# Module_BaseBoard__2_0.net
KiCad netlist of a schematic drawn in EAGLE
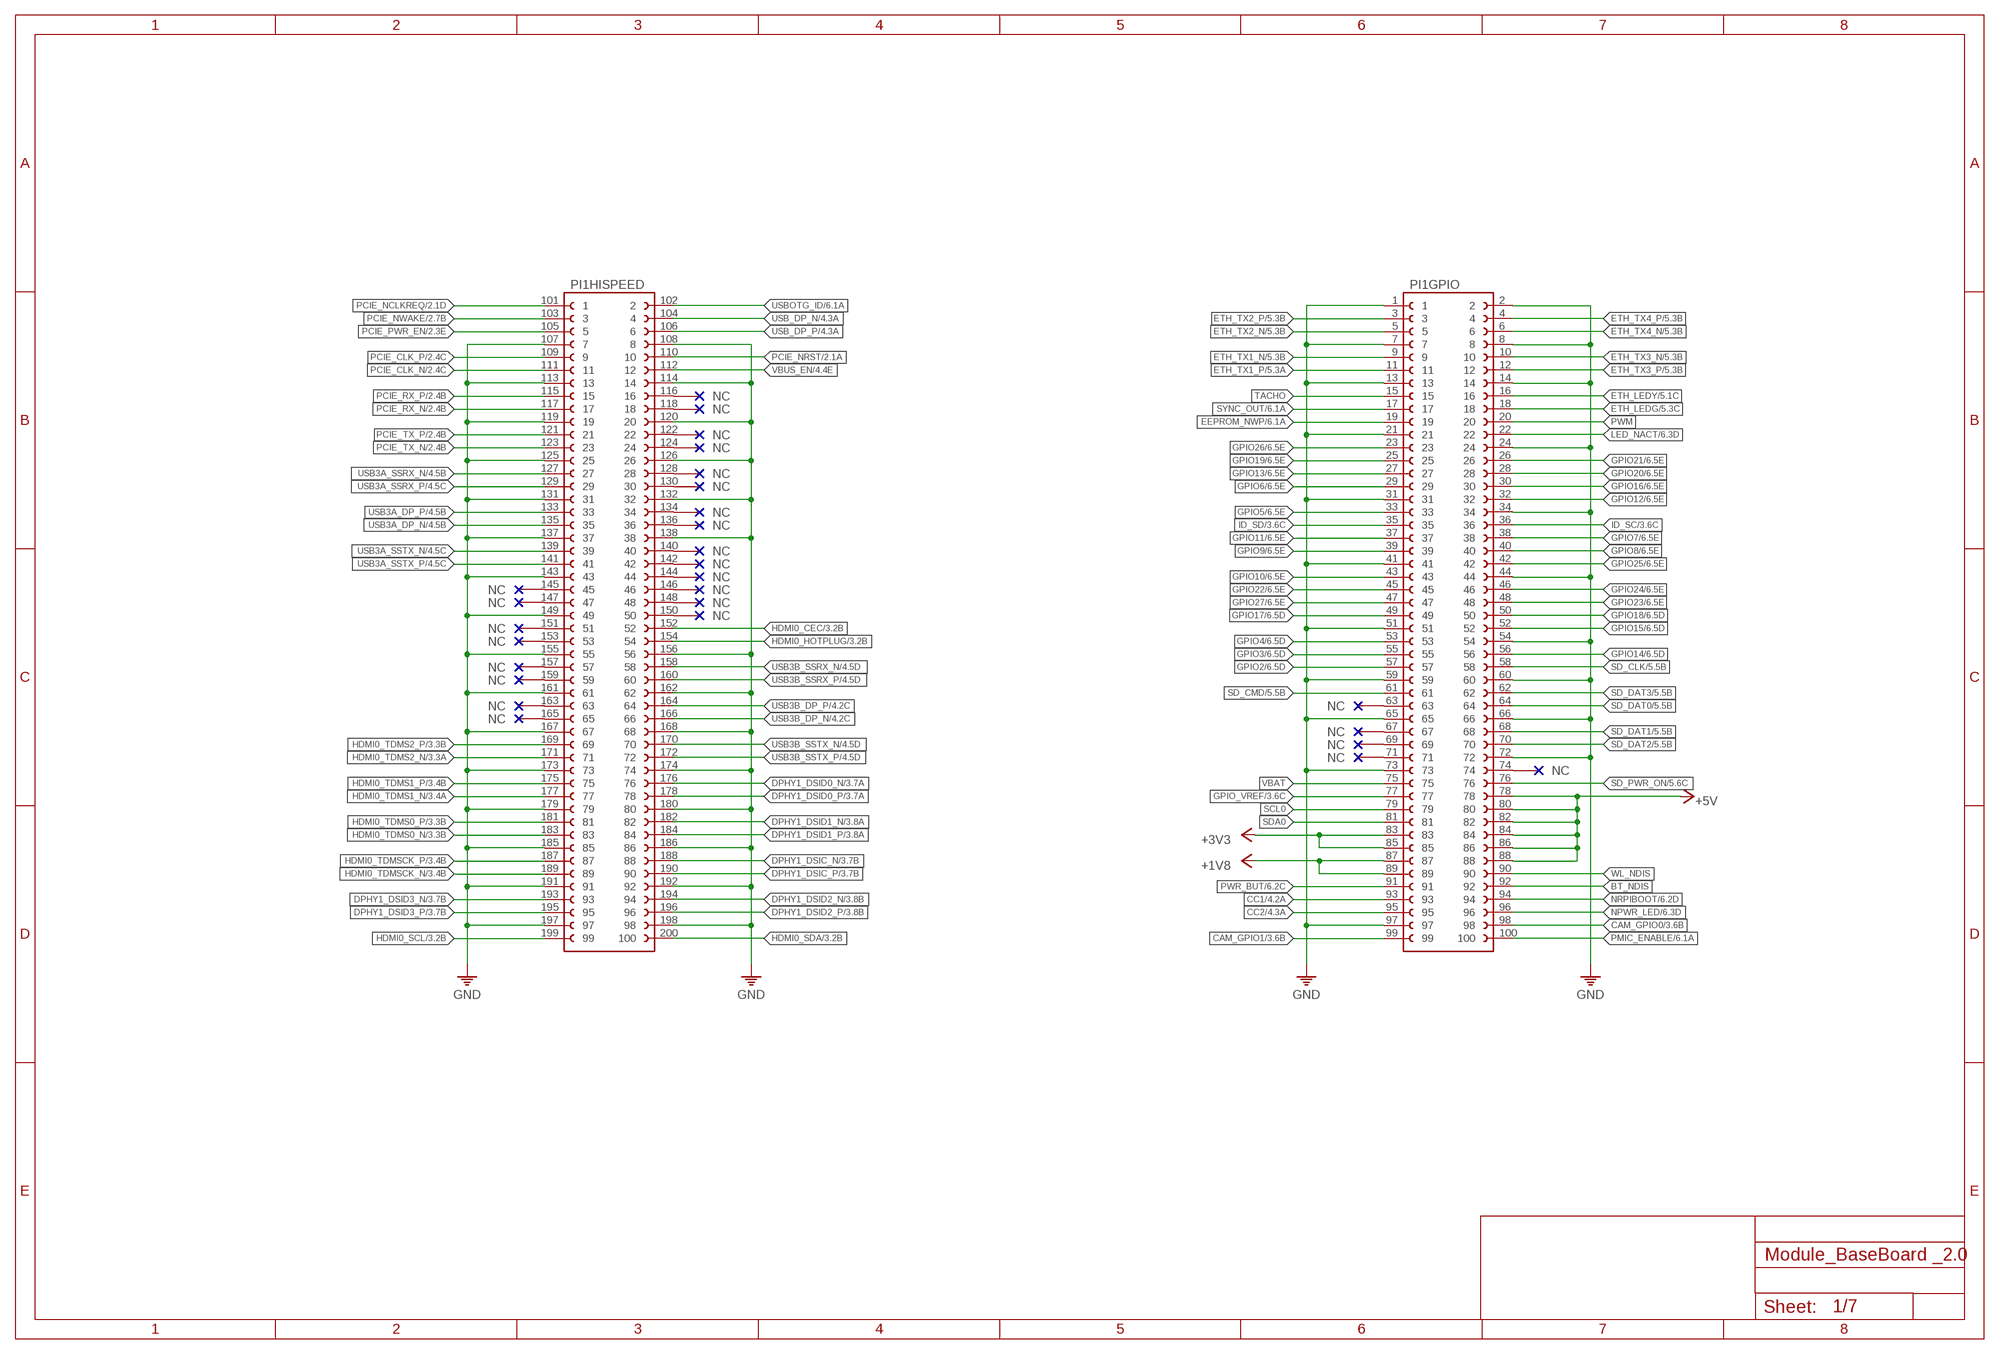
[diagram p0: schematic, sheet 1]
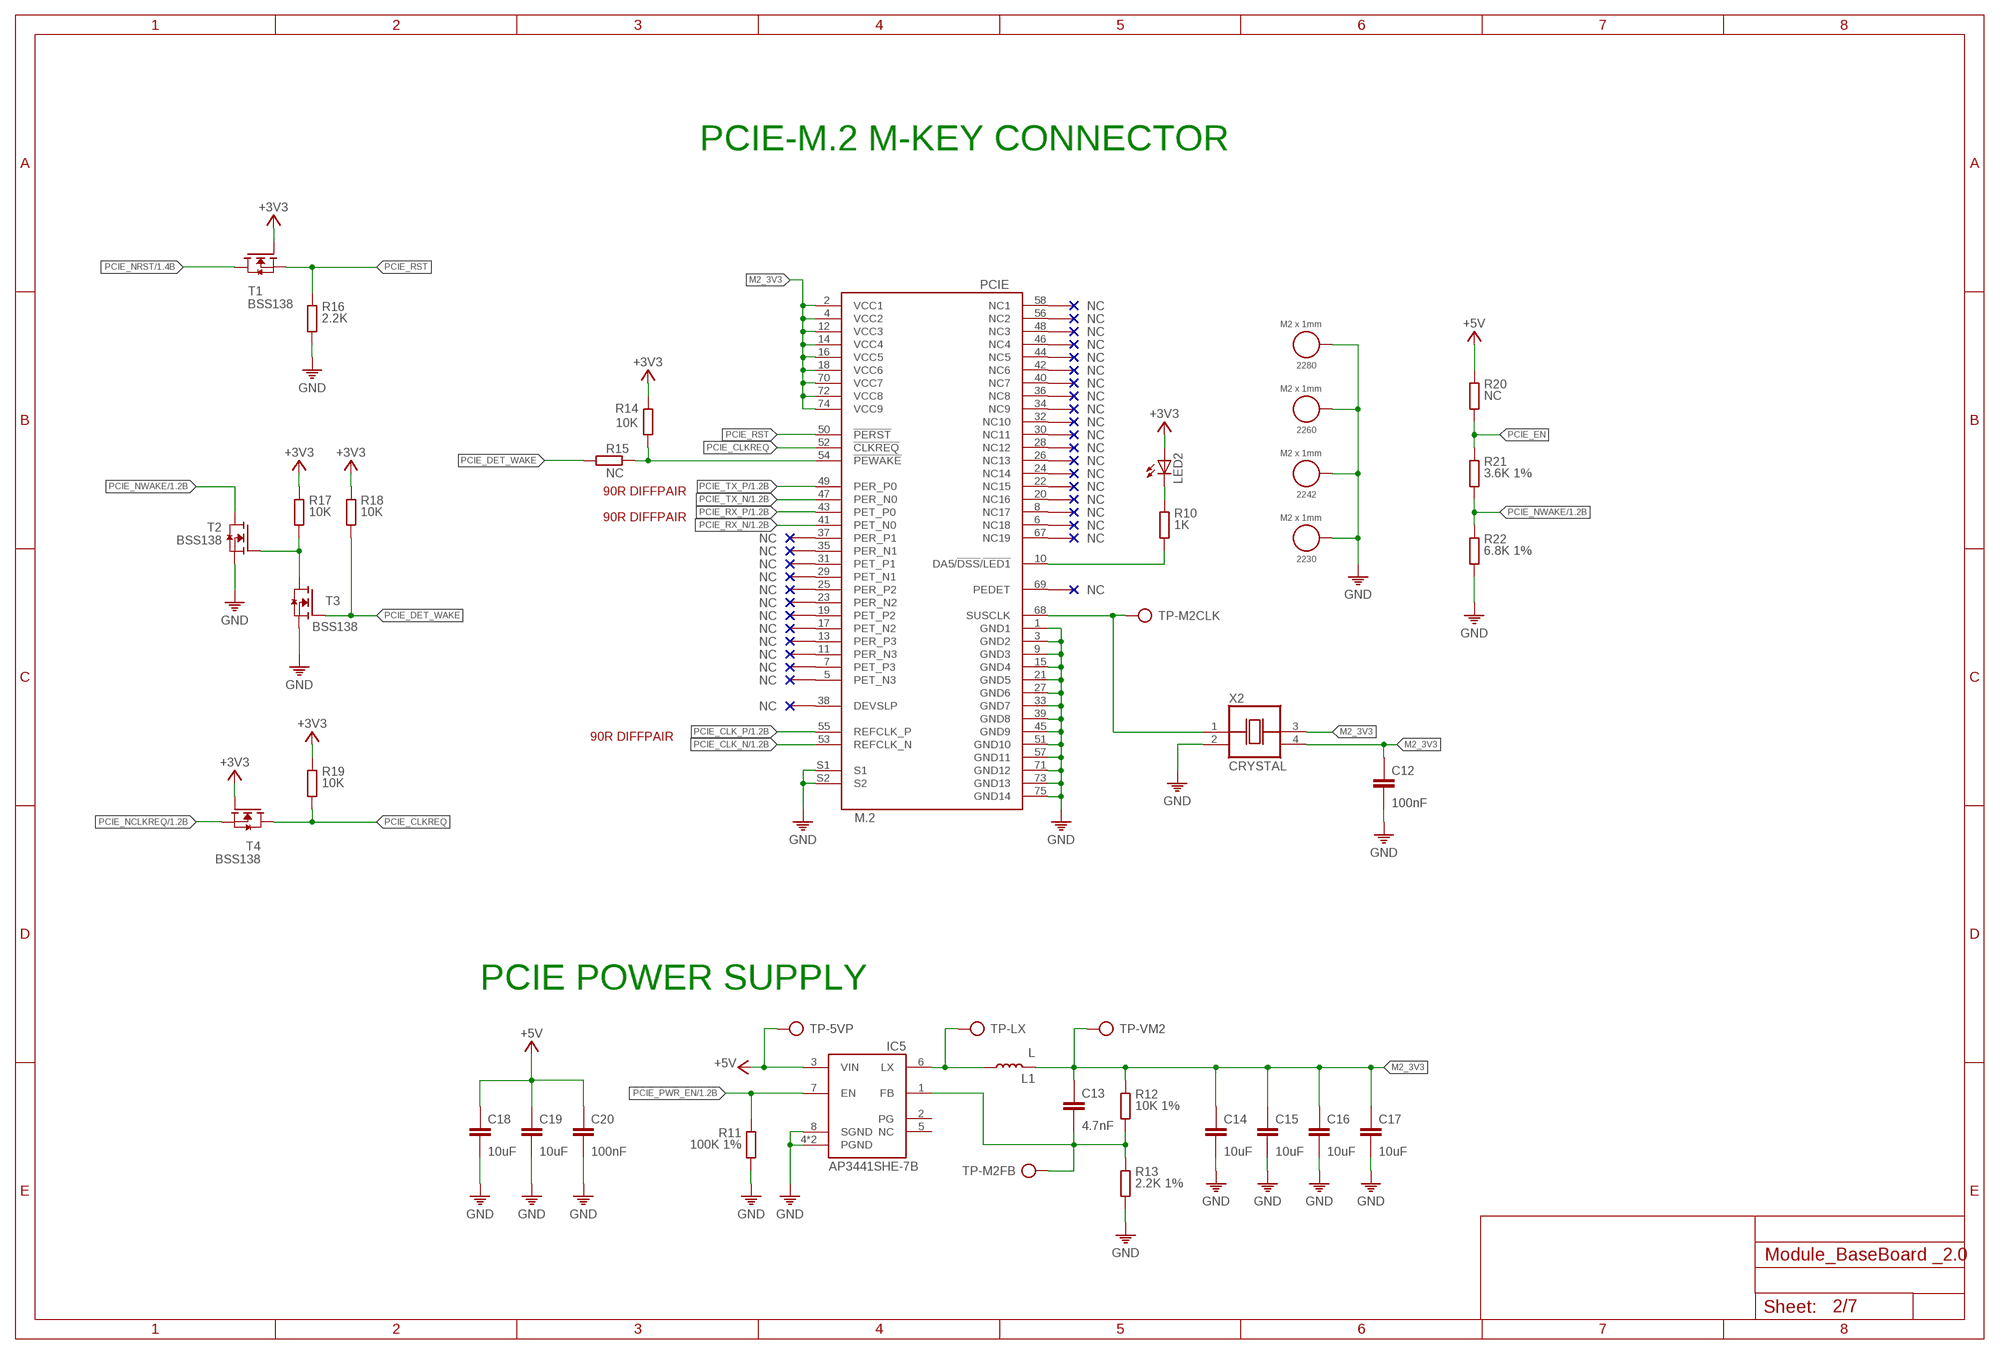
[diagram p1: schematic, sheet 2]
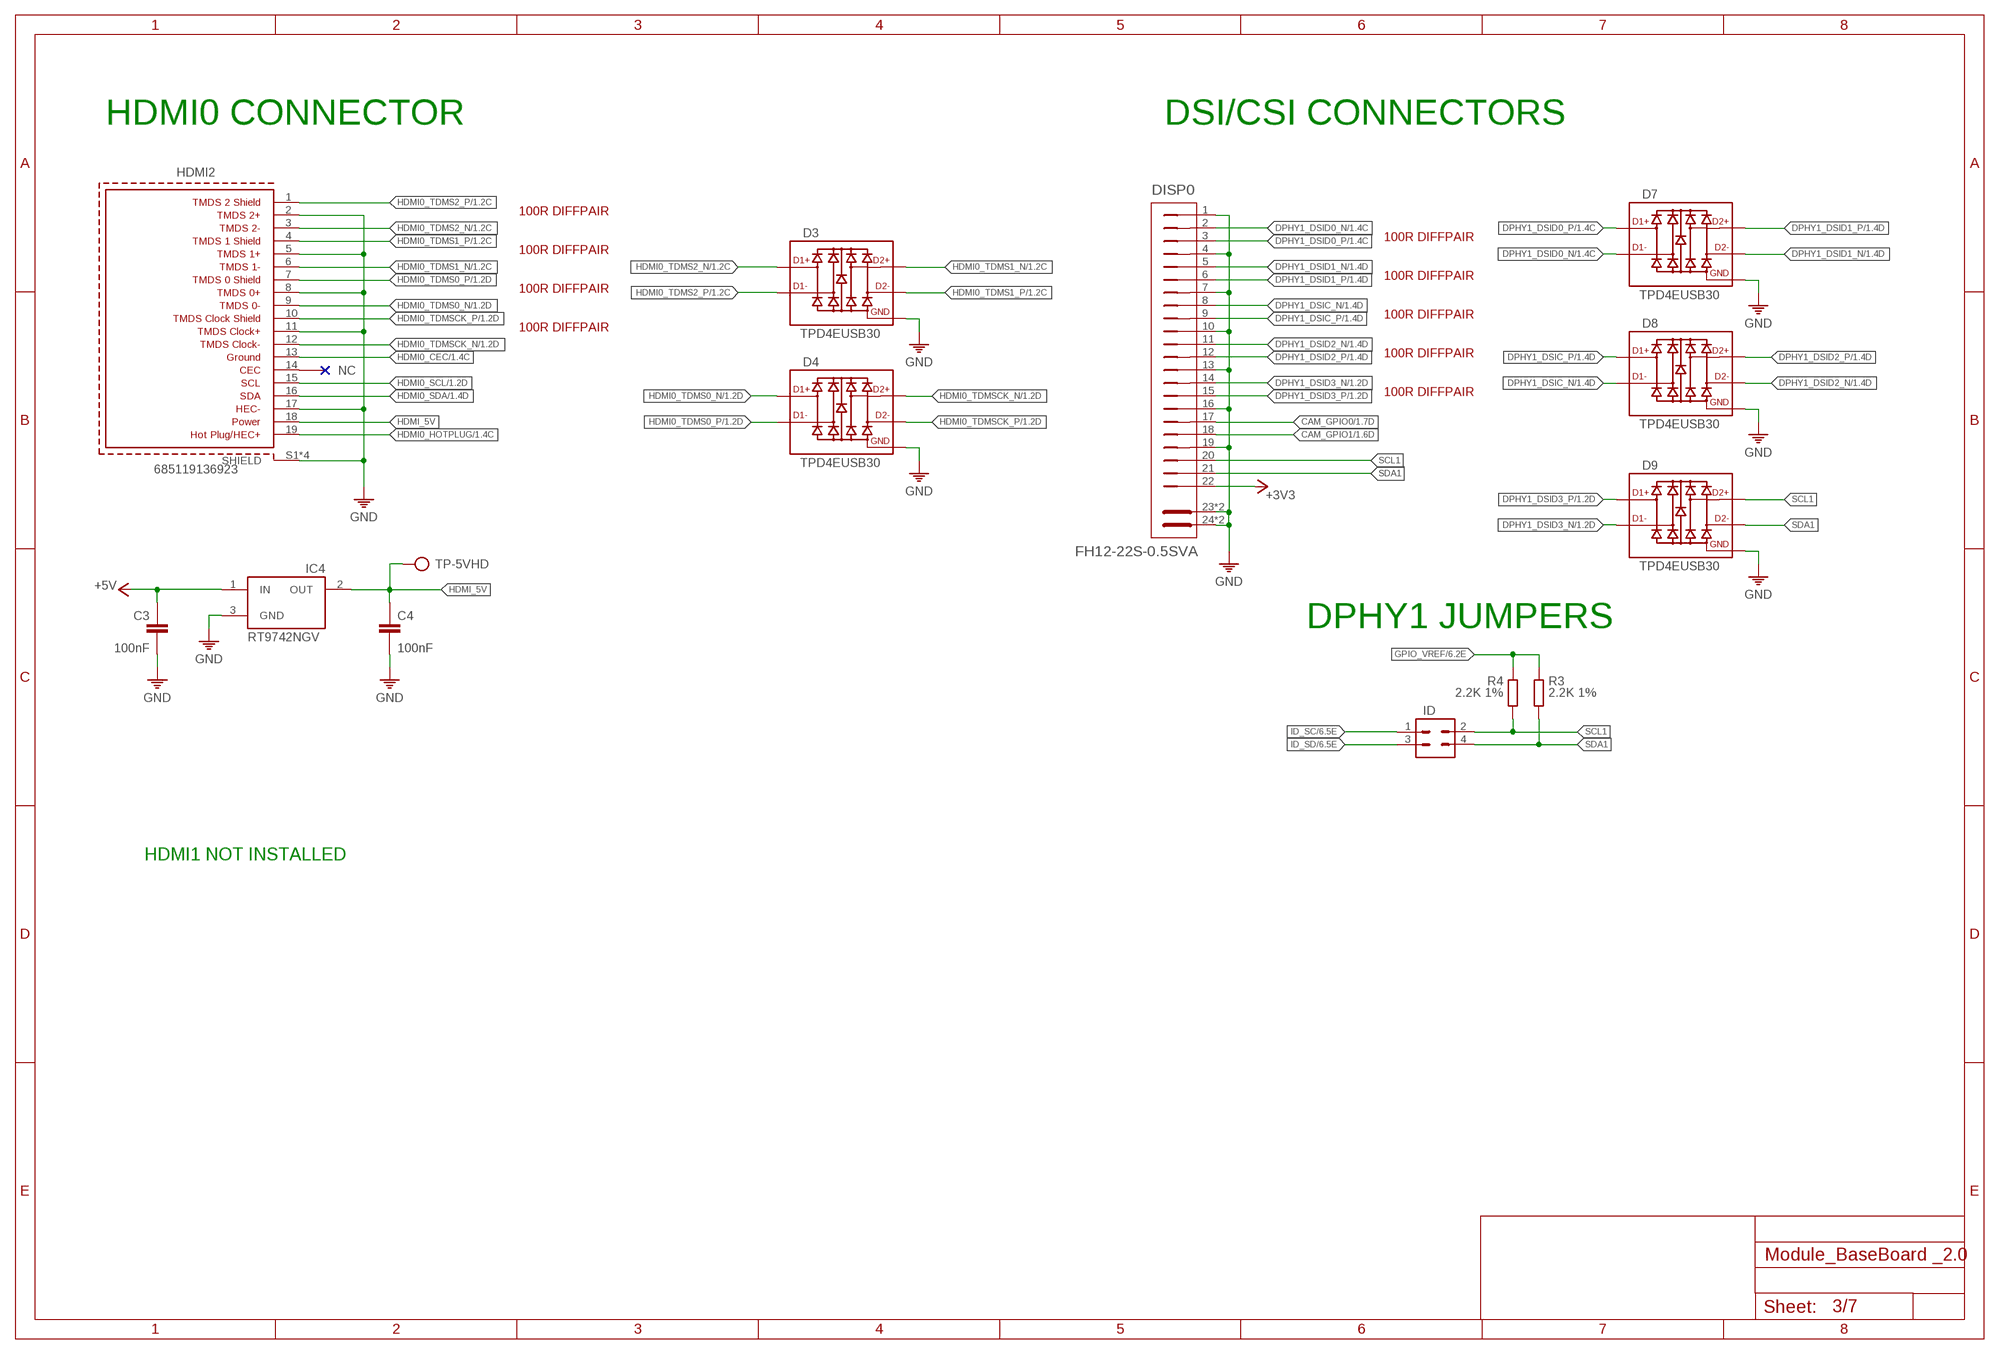
[diagram p2: schematic, sheet 3]
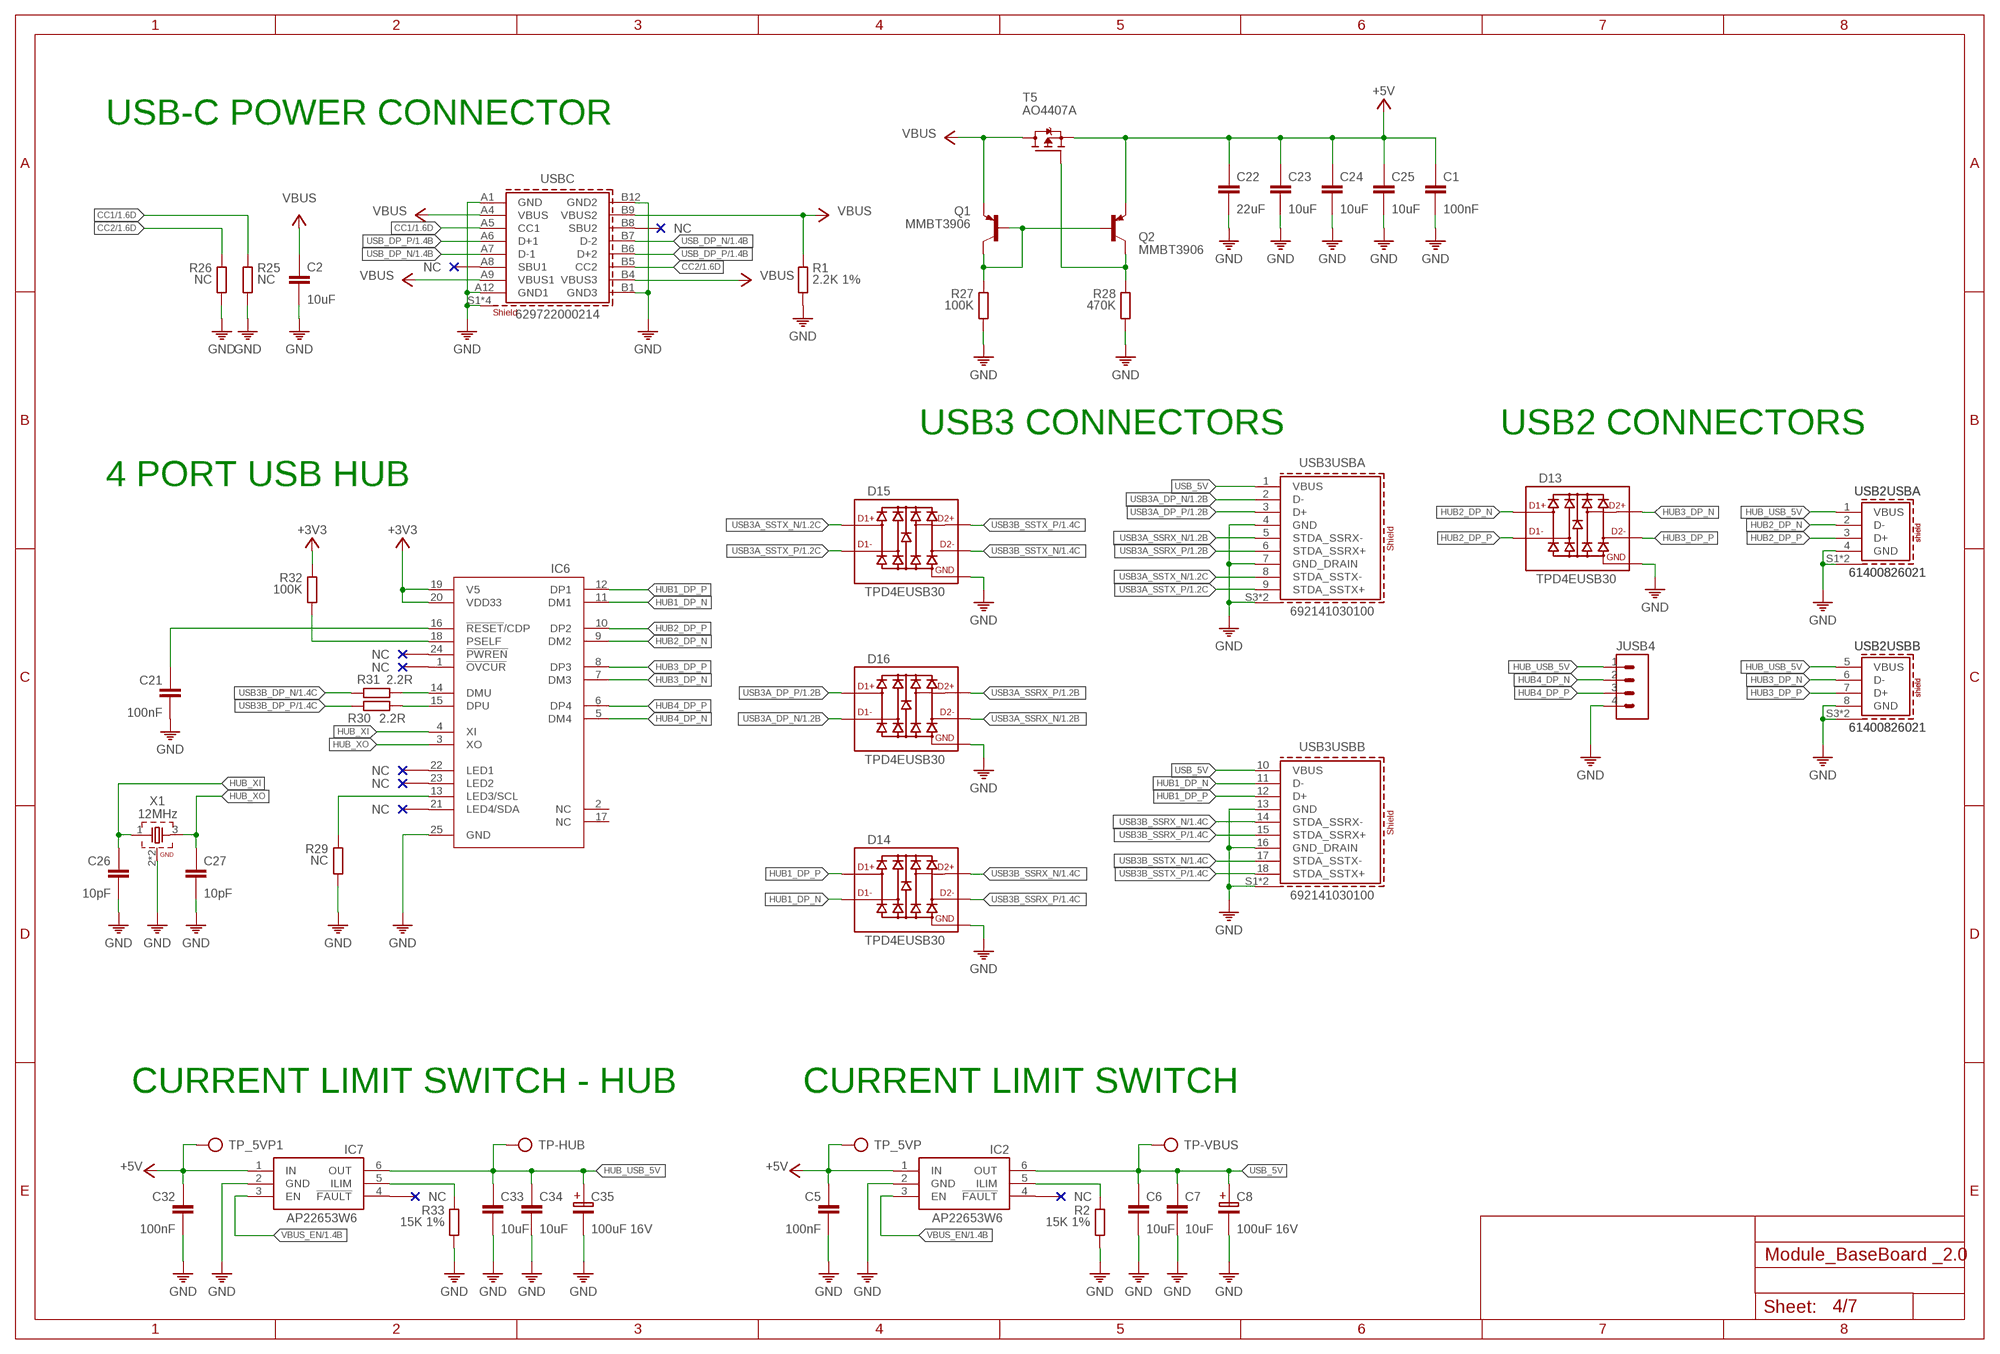
[diagram p3: schematic, sheet 4]
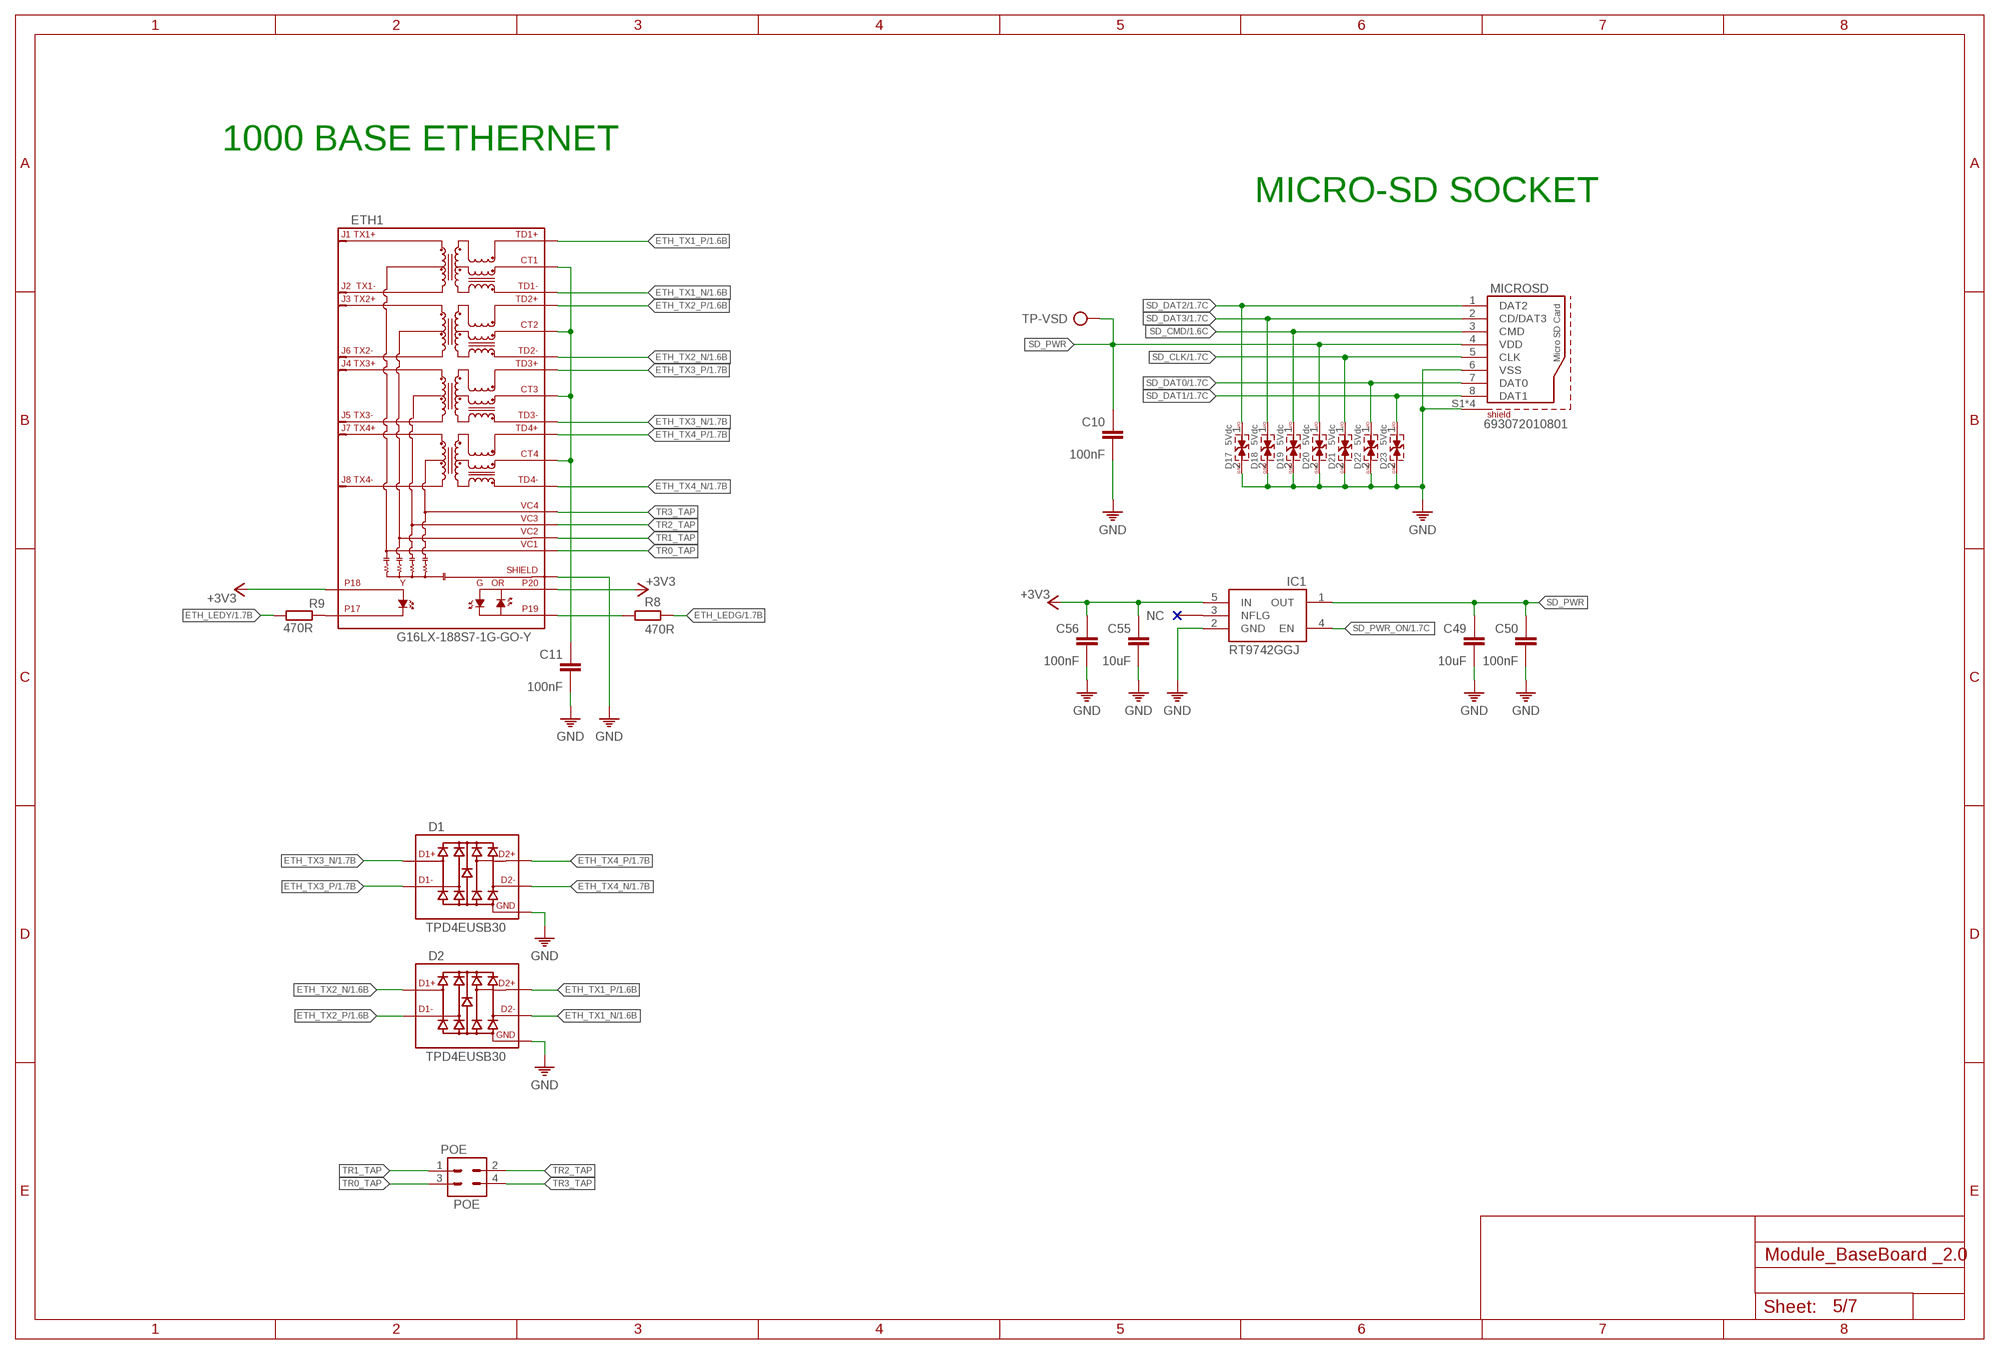
[diagram p4: schematic, sheet 5]
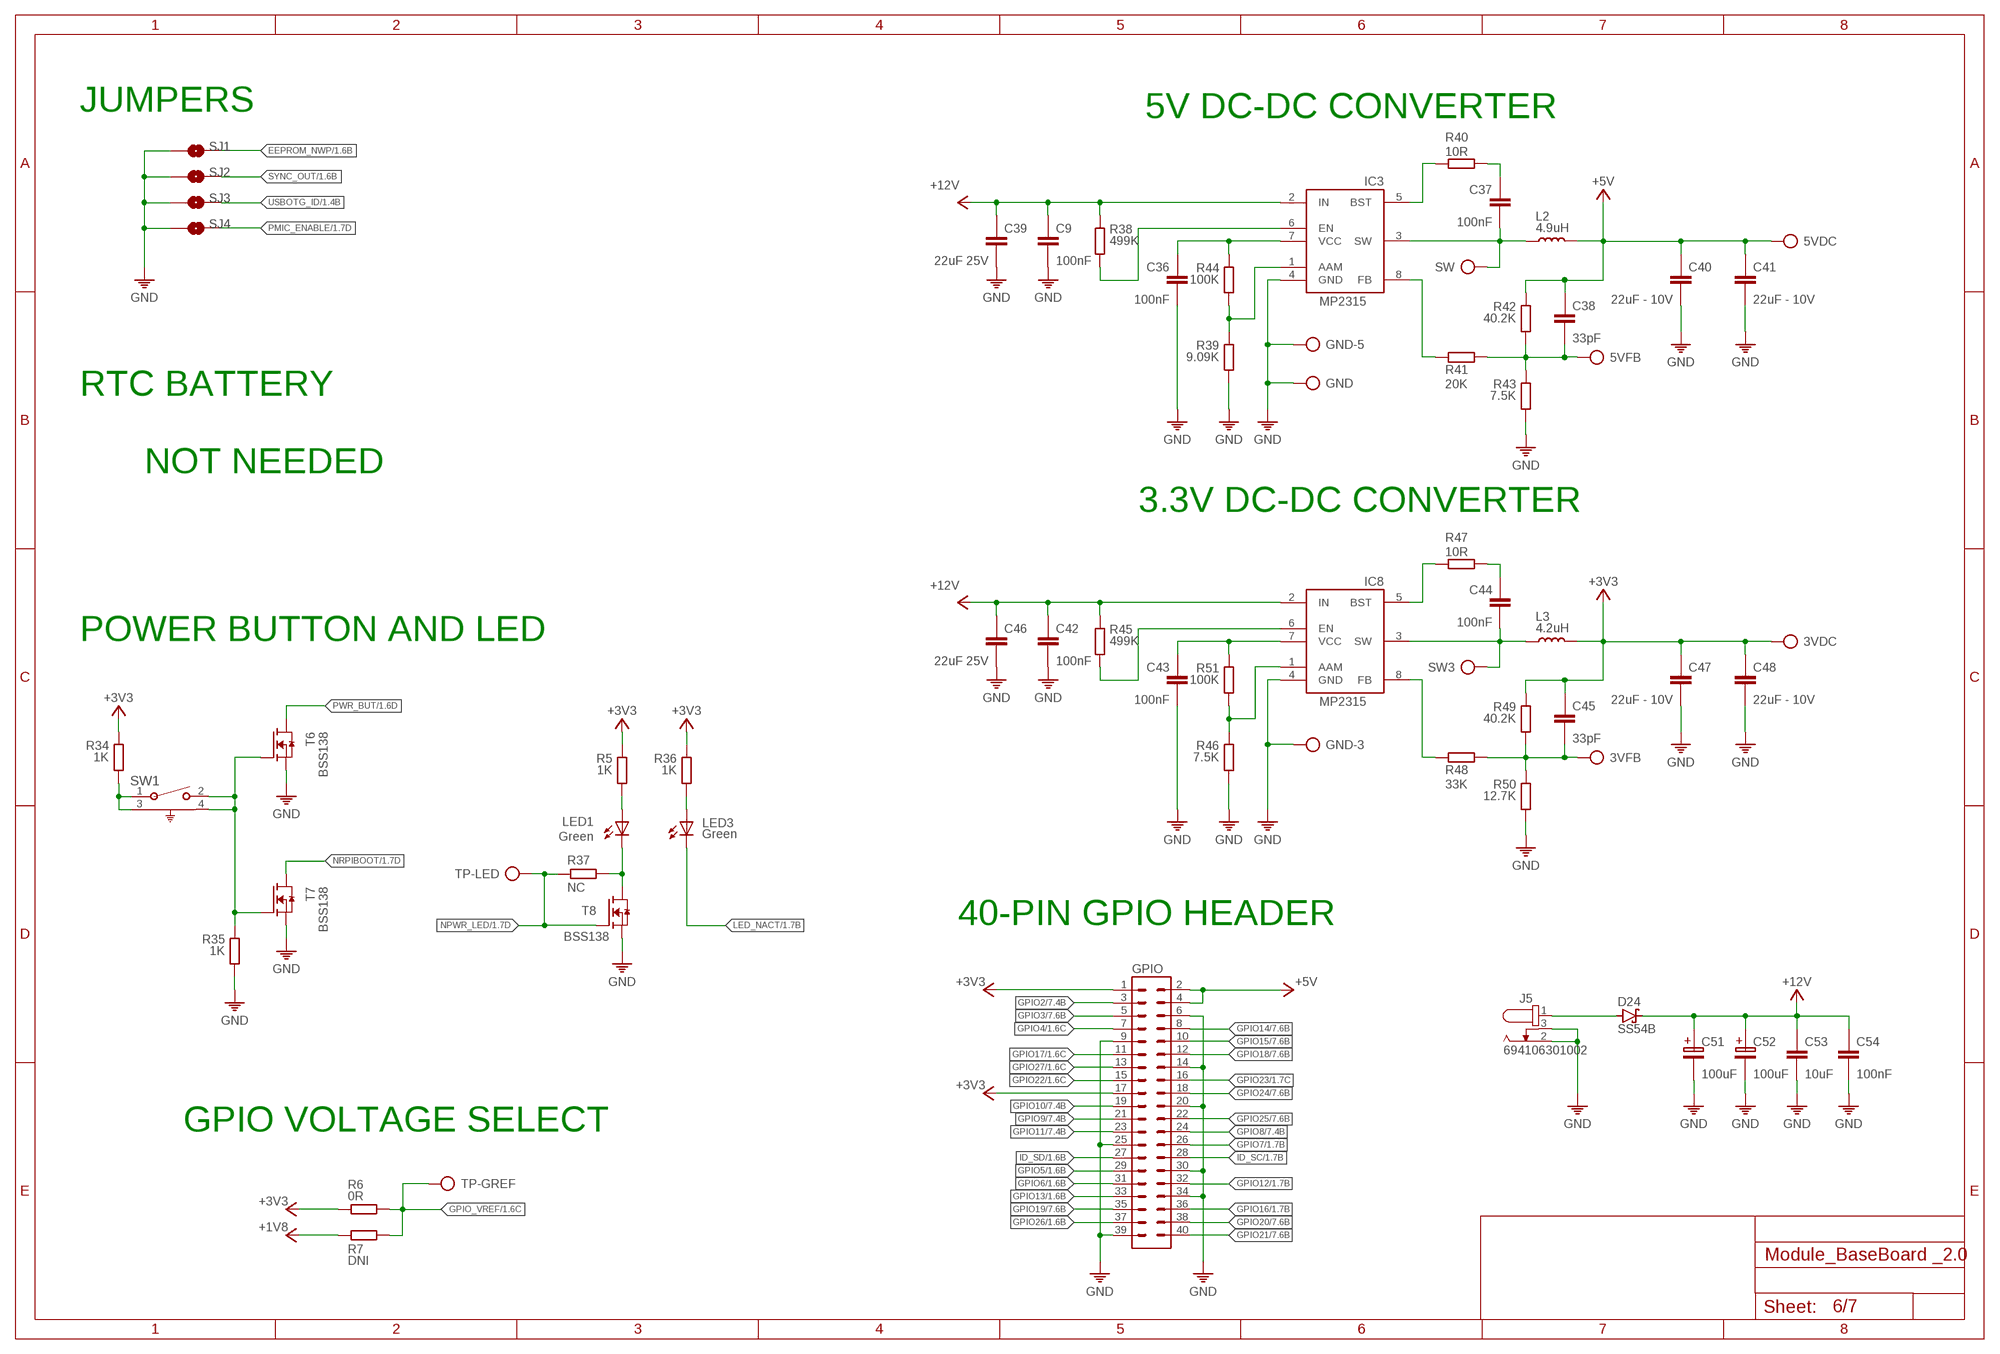
[diagram p5: schematic, sheet 6]
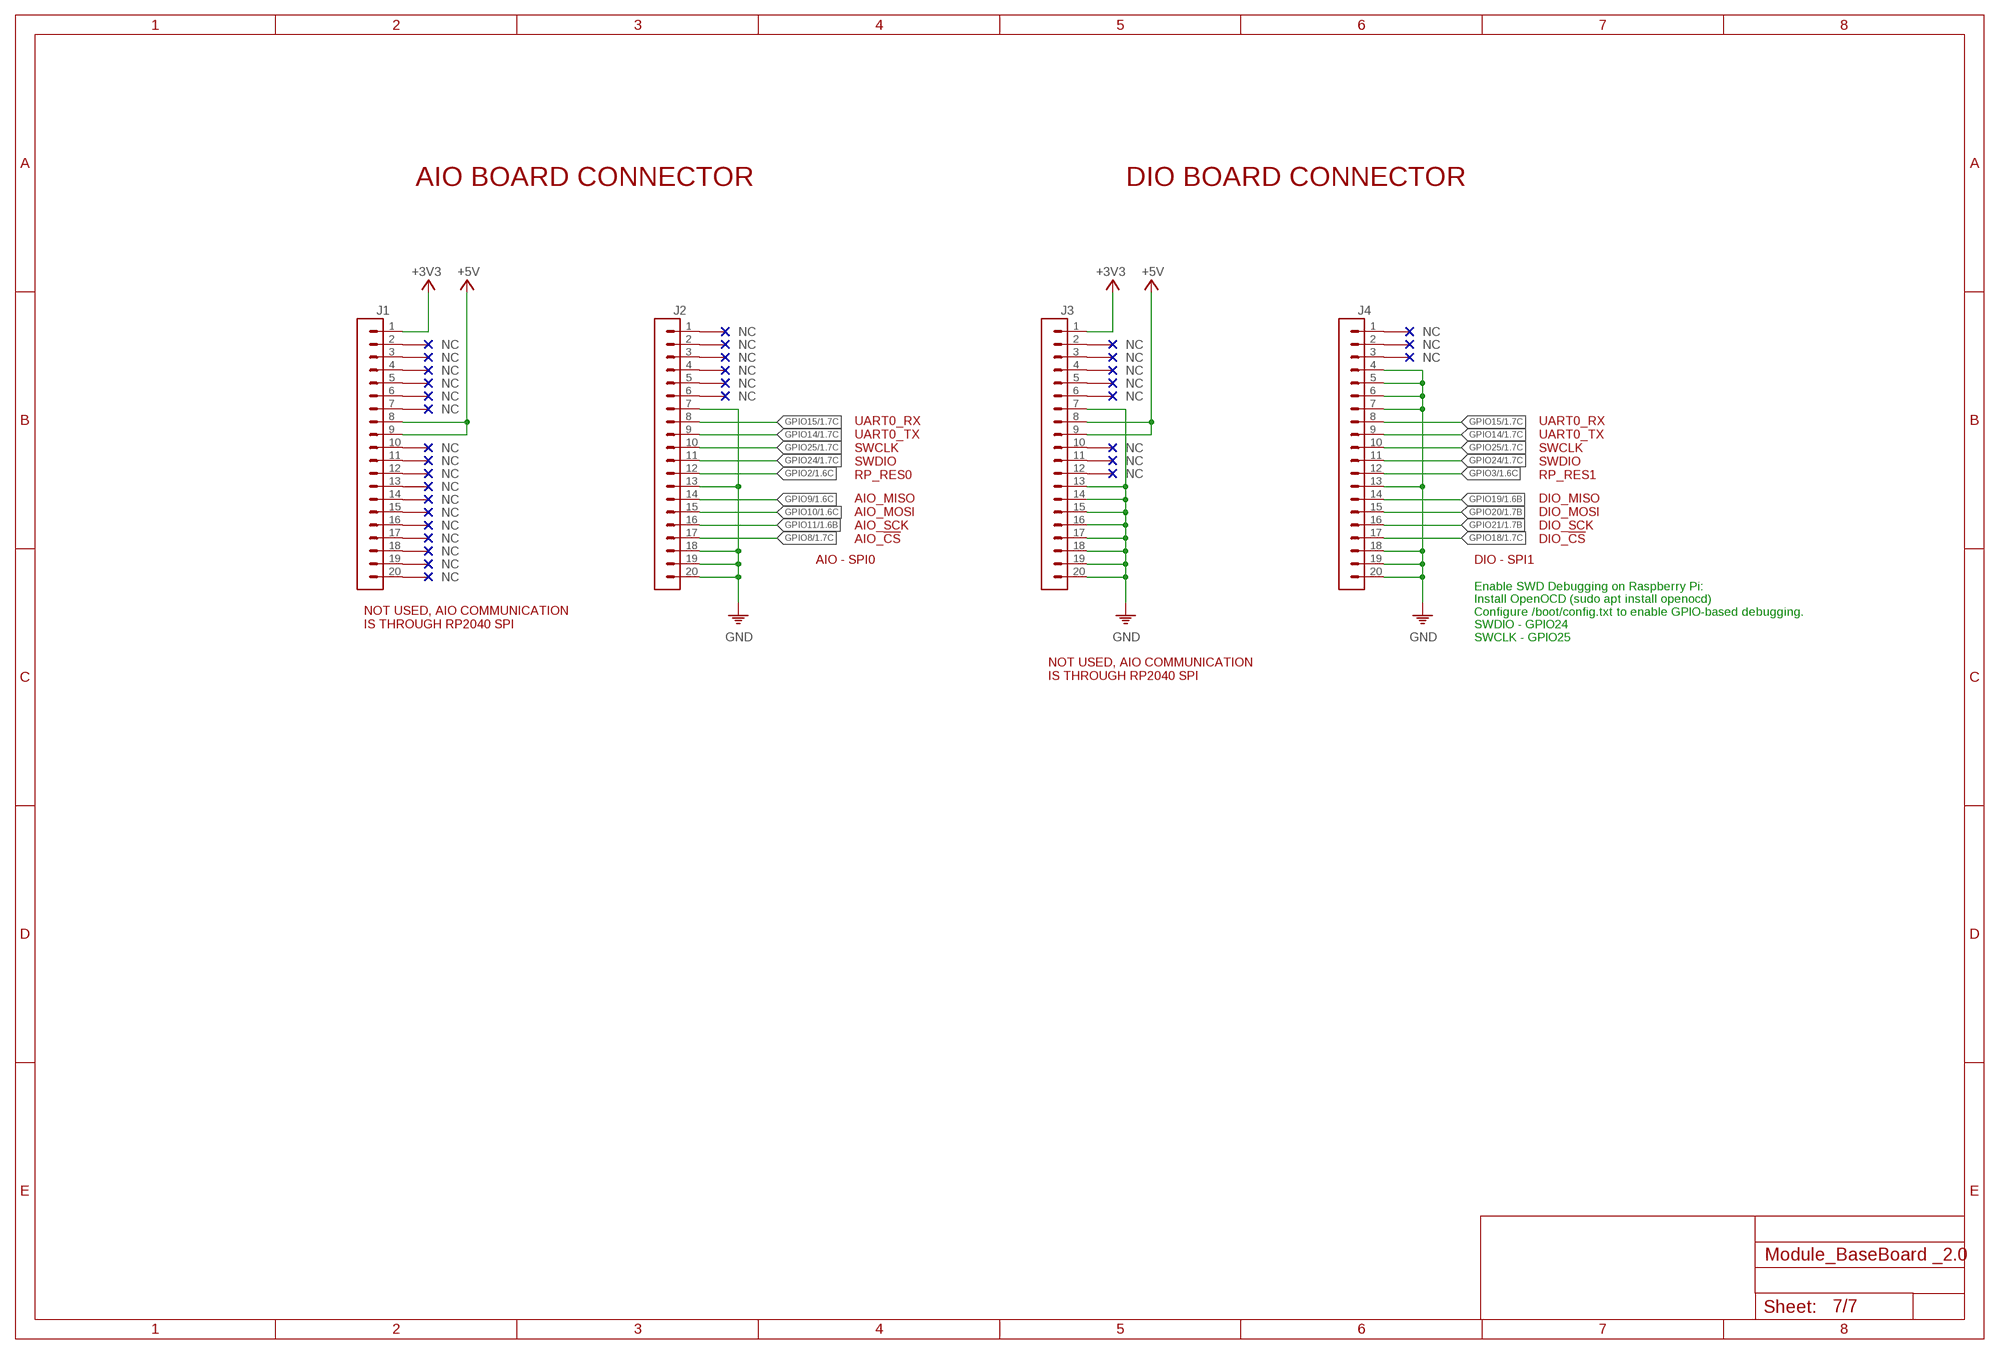
[diagram p6: schematic, sheet 7]

(export (version "E")
  (design (tool "Eeschema 10.0.6"))
  (components
    (comp (ref "C10")
      (value "100nF")
      (footprint "eagle-import:C0402")
      (libsource (lib "eagle-import") (part "C-0402"))
    )
    (comp (ref "C11")
      (value "100nF")
      (footprint "eagle-import:C1206")
      (libsource (lib "eagle-import") (part "C-1206"))
    )
    (comp (ref "C49")
      (value "10uF")
      (footprint "eagle-import:C0805")
      (libsource (lib "eagle-import") (part "C-0805"))
    )
    (comp (ref "C50")
      (value "100nF")
      (footprint "eagle-import:C0402")
      (libsource (lib "eagle-import") (part "C-0402"))
    )
    (comp (ref "C55")
      (value "10uF")
      (footprint "eagle-import:C0805")
      (libsource (lib "eagle-import") (part "C-0805"))
    )
    (comp (ref "C56")
      (value "100nF")
      (footprint "eagle-import:C0402")
      (libsource (lib "eagle-import") (part "C-0402"))
    )
    (comp (ref "D1")
      (value "TPD4EUSB30")
      (footprint "eagle-import:USON")
      (libsource (lib "eagle-import") (part "TPD4EUSB30"))
    )
    (comp (ref "D2")
      (value "TPD4EUSB30")
      (footprint "eagle-import:USON")
      (libsource (lib "eagle-import") (part "TPD4EUSB30"))
    )
    (comp (ref "D17")
      (value "5Vdc")
      (footprint "eagle-import:WE-TVS_DFN1610-2L")
      (libsource (lib "eagle-import") (part "WE-TVS_DFN1610-2L_824032815"))
    )
    (comp (ref "D18")
      (value "5Vdc")
      (footprint "eagle-import:WE-TVS_DFN1610-2L")
      (libsource (lib "eagle-import") (part "WE-TVS_DFN1610-2L_824032815"))
    )
    (comp (ref "D19")
      (value "5Vdc")
      (footprint "eagle-import:WE-TVS_DFN1610-2L")
      (libsource (lib "eagle-import") (part "WE-TVS_DFN1610-2L_824032815"))
    )
    (comp (ref "D20")
      (value "5Vdc")
      (footprint "eagle-import:WE-TVS_DFN1610-2L")
      (libsource (lib "eagle-import") (part "WE-TVS_DFN1610-2L_824032815"))
    )
    (comp (ref "D21")
      (value "5Vdc")
      (footprint "eagle-import:WE-TVS_DFN1610-2L")
      (libsource (lib "eagle-import") (part "WE-TVS_DFN1610-2L_824032815"))
    )
    (comp (ref "D22")
      (value "5Vdc")
      (footprint "eagle-import:WE-TVS_DFN1610-2L")
      (libsource (lib "eagle-import") (part "WE-TVS_DFN1610-2L_824032815"))
    )
    (comp (ref "D23")
      (value "5Vdc")
      (footprint "eagle-import:WE-TVS_DFN1610-2L")
      (libsource (lib "eagle-import") (part "WE-TVS_DFN1610-2L_824032815"))
    )
    (comp (ref "ETH1")
      (value "G16LX-188S7-1G-GO-Y")
      (footprint "eagle-import:RJ45-CAT6-POE")
      (libsource (lib "eagle-import") (part "RJ45-CAT6-POE"))
    )
    (comp (ref "IC1")
      (value "RT9742GGJ")
      (footprint "eagle-import:SOT23-5")
      (libsource (lib "eagle-import") (part "RT9742GGJ5"))
    )
    (comp (ref "MICROSD")
      (value "693072010801")
      (footprint "eagle-import:693072010801")
      (libsource (lib "eagle-import") (part "693072010801"))
    )
    (comp (ref "POE")
      (value "POE")
      (footprint "eagle-import:2X2")
      (libsource (lib "eagle-import") (part "CON-2X2"))
    )
    (comp (ref "R8")
      (value "470R")
      (footprint "eagle-import:0402")
      (libsource (lib "eagle-import") (part "R0402"))
    )
    (comp (ref "R9")
      (value "470R")
      (footprint "eagle-import:0402")
      (libsource (lib "eagle-import") (part "R0402"))
    )
    (comp (ref "TP-VSD")
      (value "TP")
      (footprint "eagle-import:TP")
      (libsource (lib "eagle-import") (part "TP"))
    )
    (comp (ref "C1")
      (value "100nF")
      (footprint "eagle-import:C0805")
      (libsource (lib "eagle-import") (part "C-0805"))
    )
    (comp (ref "C2")
      (value "10uF")
      (footprint "eagle-import:C0805")
      (libsource (lib "eagle-import") (part "C-0805"))
    )
    (comp (ref "C5")
      (value "100nF")
      (footprint "eagle-import:C0402")
      (libsource (lib "eagle-import") (part "C-0402"))
    )
    (comp (ref "C6")
      (value "10uF")
      (footprint "eagle-import:C0805")
      (libsource (lib "eagle-import") (part "C-0805"))
    )
    (comp (ref "C7")
      (value "10uF")
      (footprint "eagle-import:C0805")
      (libsource (lib "eagle-import") (part "C-0805"))
    )
    (comp (ref "C8")
      (value "100uF 16V")
      (footprint "eagle-import:100UF-16V")
      (libsource (lib "eagle-import") (part "CPOL"))
    )
    (comp (ref "C21")
      (value "100nF")
      (footprint "eagle-import:C0402")
      (libsource (lib "eagle-import") (part "C-0402"))
    )
    (comp (ref "C22")
      (value "22uF")
      (footprint "eagle-import:C0805")
      (libsource (lib "eagle-import") (part "C-0805"))
    )
    (comp (ref "C23")
      (value "10uF")
      (footprint "eagle-import:C0805")
      (libsource (lib "eagle-import") (part "C-0805"))
    )
    (comp (ref "C24")
      (value "10uF")
      (footprint "eagle-import:C0805")
      (libsource (lib "eagle-import") (part "C-0805"))
    )
    (comp (ref "C25")
      (value "10uF")
      (footprint "eagle-import:C0805")
      (libsource (lib "eagle-import") (part "C-0805"))
    )
    (comp (ref "C26")
      (value "10pF")
      (footprint "eagle-import:C0402")
      (libsource (lib "eagle-import") (part "C-0402"))
    )
    (comp (ref "C27")
      (value "10pF")
      (footprint "eagle-import:C0402")
      (libsource (lib "eagle-import") (part "C-0402"))
    )
    (comp (ref "C32")
      (value "100nF")
      (footprint "eagle-import:C0402")
      (libsource (lib "eagle-import") (part "C-0402"))
    )
    (comp (ref "C33")
      (value "10uF")
      (footprint "eagle-import:C0805")
      (libsource (lib "eagle-import") (part "C-0805"))
    )
    (comp (ref "C34")
      (value "10uF")
      (footprint "eagle-import:C0805")
      (libsource (lib "eagle-import") (part "C-0805"))
    )
    (comp (ref "C35")
      (value "100uF 16V")
      (footprint "eagle-import:100UF-16V")
      (libsource (lib "eagle-import") (part "CPOL"))
    )
    (comp (ref "D13")
      (value "TPD4EUSB30")
      (footprint "eagle-import:USON")
      (libsource (lib "eagle-import") (part "TPD4EUSB30"))
    )
    (comp (ref "D14")
      (value "TPD4EUSB30")
      (footprint "eagle-import:USON")
      (libsource (lib "eagle-import") (part "TPD4EUSB30"))
    )
    (comp (ref "D15")
      (value "TPD4EUSB30")
      (footprint "eagle-import:USON")
      (libsource (lib "eagle-import") (part "TPD4EUSB30"))
    )
    (comp (ref "D16")
      (value "TPD4EUSB30")
      (footprint "eagle-import:USON")
      (libsource (lib "eagle-import") (part "TPD4EUSB30"))
    )
    (comp (ref "IC2")
      (value "AP22653W6")
      (footprint "eagle-import:SOT23-6")
      (libsource (lib "eagle-import") (part "AP22653W6"))
    )
    (comp (ref "IC6")
      (value "CH334")
      (footprint "eagle-import:QFN24")
      (libsource (lib "eagle-import") (part "CH334"))
    )
    (comp (ref "IC7")
      (value "AP22653W6")
      (footprint "eagle-import:SOT23-6")
      (libsource (lib "eagle-import") (part "AP22653W6"))
    )
    (comp (ref "JUSB4")
      (value "CON-1X4")
      (footprint "eagle-import:1X4")
      (libsource (lib "eagle-import") (part "CON-1X4"))
    )
    (comp (ref "Q1")
      (value "MMBT3906")
      (footprint "eagle-import:SOT23")
      (fields
        (field (name "DIGIKEY_PART_NUMBER") "MMBT3906FSCT-ND")
        (field (name "MANUFACTURER") "ON Semiconductor")
        (field (name "CREATED_BY") "PCBLayout.com")
      )
      (libsource (lib "eagle-import") (part "MMBT3906"))
    )
    (comp (ref "Q2")
      (value "MMBT3906")
      (footprint "eagle-import:SOT23")
      (fields
        (field (name "DIGIKEY_PART_NUMBER") "MMBT3906FSCT-ND")
        (field (name "MANUFACTURER") "ON Semiconductor")
        (field (name "CREATED_BY") "PCBLayout.com")
      )
      (libsource (lib "eagle-import") (part "MMBT3906"))
    )
    (comp (ref "R1")
      (value "2.2K 1%")
      (footprint "eagle-import:0402")
      (libsource (lib "eagle-import") (part "R0402"))
    )
    (comp (ref "R2")
      (value "15K 1%")
      (footprint "eagle-import:0402")
      (libsource (lib "eagle-import") (part "R0402"))
    )
    (comp (ref "R25")
      (value "NC")
      (footprint "eagle-import:0402")
      (libsource (lib "eagle-import") (part "R0402"))
    )
    (comp (ref "R26")
      (value "NC")
      (footprint "eagle-import:0402")
      (libsource (lib "eagle-import") (part "R0402"))
    )
    (comp (ref "R27")
      (value "100K")
      (footprint "eagle-import:0402")
      (libsource (lib "eagle-import") (part "R0402"))
    )
    (comp (ref "R28")
      (value "470K")
      (footprint "eagle-import:0402")
      (libsource (lib "eagle-import") (part "R0402"))
    )
    (comp (ref "R29")
      (value "NC")
      (footprint "eagle-import:0402")
      (libsource (lib "eagle-import") (part "R0402"))
    )
    (comp (ref "R30")
      (value "2.2R")
      (footprint "eagle-import:0402")
      (libsource (lib "eagle-import") (part "R0402"))
    )
    (comp (ref "R31")
      (value "2.2R")
      (footprint "eagle-import:0402")
      (libsource (lib "eagle-import") (part "R0402"))
    )
    (comp (ref "R32")
      (value "100K")
      (footprint "eagle-import:0402")
      (libsource (lib "eagle-import") (part "R0402"))
    )
    (comp (ref "R33")
      (value "15K 1%")
      (footprint "eagle-import:0402")
      (libsource (lib "eagle-import") (part "R0402"))
    )
    (comp (ref "T5")
      (value "AO4407A")
      (footprint "eagle-import:SO8")
      (libsource (lib "eagle-import") (part "AO4407A"))
    )
    (comp (ref "TP-HUB")
      (value "TP")
      (footprint "eagle-import:TP")
      (libsource (lib "eagle-import") (part "TP"))
    )
    (comp (ref "TP-VBUS")
      (value "TP")
      (footprint "eagle-import:TP")
      (libsource (lib "eagle-import") (part "TP"))
    )
    (comp (ref "TP_5VP")
      (value "TP")
      (footprint "eagle-import:TP")
      (libsource (lib "eagle-import") (part "TP"))
    )
    (comp (ref "TP_5VP1")
      (value "TP")
      (footprint "eagle-import:TP")
      (libsource (lib "eagle-import") (part "TP"))
    )
    (comp (ref "USB2")
      (value "61400826021")
      (footprint "eagle-import:61400826021")
      (libsource (lib "eagle-import") (part "61400826021"))
    )
    (comp (ref "USB3")
      (value "692141030100")
      (footprint "eagle-import:692141030100")
      (libsource (lib "eagle-import") (part "692141030100"))
    )
    (comp (ref "USBC")
      (value "629722000214")
      (footprint "eagle-import:629722000214")
      (libsource (lib "eagle-import") (part "629722000214"))
    )
    (comp (ref "X1")
      (value "12MHz")
      (footprint "eagle-import:WE-XTAL_CFPX-180")
      (fields (field (name "TOLERANCE") "±50ppm"))
      (libsource (lib "eagle-import") (part "WE-XTAL_CFPX-180_830035266"))
    )
    (comp (ref "J1")
      (value "CON-1X20")
      (footprint "eagle-import:1X20")
      (libsource (lib "eagle-import") (part "CON-1X20"))
    )
    (comp (ref "J2")
      (value "CON-1X20")
      (footprint "eagle-import:1X20")
      (libsource (lib "eagle-import") (part "CON-1X20"))
    )
    (comp (ref "J3")
      (value "CON-1X20")
      (footprint "eagle-import:1X20")
      (libsource (lib "eagle-import") (part "CON-1X20"))
    )
    (comp (ref "J4")
      (value "CON-1X20")
      (footprint "eagle-import:1X20")
      (libsource (lib "eagle-import") (part "CON-1X20"))
    )
    (comp (ref "3VDC")
      (value "TP")
      (footprint "eagle-import:TP")
      (libsource (lib "eagle-import") (part "TP"))
    )
    (comp (ref "3VFB")
      (value "TP")
      (footprint "eagle-import:TP")
      (libsource (lib "eagle-import") (part "TP"))
    )
    (comp (ref "5VDC")
      (value "TP")
      (footprint "eagle-import:TP")
      (libsource (lib "eagle-import") (part "TP"))
    )
    (comp (ref "5VFB")
      (value "TP")
      (footprint "eagle-import:TP")
      (libsource (lib "eagle-import") (part "TP"))
    )
    (comp (ref "C9")
      (value "100nF")
      (footprint "eagle-import:0402")
      (libsource (lib "eagle-import") (part "C0402"))
    )
    (comp (ref "C36")
      (value "100nF")
      (footprint "eagle-import:0402")
      (libsource (lib "eagle-import") (part "C0402"))
    )
    (comp (ref "C37")
      (value "100nF")
      (footprint "eagle-import:0402")
      (libsource (lib "eagle-import") (part "C0402"))
    )
    (comp (ref "C38")
      (value "33pF")
      (footprint "eagle-import:0402")
      (libsource (lib "eagle-import") (part "C0402"))
    )
    (comp (ref "C39")
      (value "22uF 25V")
      (footprint "eagle-import:C1206")
      (libsource (lib "eagle-import") (part "C-1206"))
    )
    (comp (ref "C40")
      (value "22uF - 10V")
      (footprint "eagle-import:C1206")
      (libsource (lib "eagle-import") (part "C-1206"))
    )
    (comp (ref "C41")
      (value "22uF - 10V")
      (footprint "eagle-import:C1206")
      (libsource (lib "eagle-import") (part "C-1206"))
    )
    (comp (ref "C42")
      (value "100nF")
      (footprint "eagle-import:0402")
      (libsource (lib "eagle-import") (part "C0402"))
    )
    (comp (ref "C43")
      (value "100nF")
      (footprint "eagle-import:0402")
      (libsource (lib "eagle-import") (part "C0402"))
    )
    (comp (ref "C44")
      (value "100nF")
      (footprint "eagle-import:0402")
      (libsource (lib "eagle-import") (part "C0402"))
    )
    (comp (ref "C45")
      (value "33pF")
      (footprint "eagle-import:0402")
      (libsource (lib "eagle-import") (part "C0402"))
    )
    (comp (ref "C46")
      (value "22uF 25V")
      (footprint "eagle-import:C1206")
      (libsource (lib "eagle-import") (part "C-1206"))
    )
    (comp (ref "C47")
      (value "22uF - 10V")
      (footprint "eagle-import:C1206")
      (libsource (lib "eagle-import") (part "C-1206"))
    )
    (comp (ref "C48")
      (value "22uF - 10V")
      (footprint "eagle-import:C1206")
      (libsource (lib "eagle-import") (part "C-1206"))
    )
    (comp (ref "C51")
      (value "100uF")
      (footprint "eagle-import:100UF-16V")
      (libsource (lib "eagle-import") (part "CPOL"))
    )
    (comp (ref "C52")
      (value "100uF")
      (footprint "eagle-import:100UF-16V")
      (libsource (lib "eagle-import") (part "CPOL"))
    )
    (comp (ref "C53")
      (value "10uF")
      (footprint "eagle-import:C1206")
      (libsource (lib "eagle-import") (part "C-1206"))
    )
    (comp (ref "C54")
      (value "100nF")
      (footprint "eagle-import:C1206")
      (libsource (lib "eagle-import") (part "C-1206"))
    )
    (comp (ref "D24")
      (value "SS54B")
      (footprint "eagle-import:SMB")
      (fields (field (name "MANUFACTURER") "JCET") (field (name "CREATED_BY") "PCBLayout.com"))
      (libsource (lib "eagle-import") (part "SS54B"))
    )
    (comp (ref "GND") (value "TP") (footprint "eagle-import:TP") (libsource (lib "eagle-import") (part "TP")))
    (comp (ref "GND-3")
      (value "TP")
      (footprint "eagle-import:TP")
      (libsource (lib "eagle-import") (part "TP"))
    )
    (comp (ref "GND-5")
      (value "TP")
      (footprint "eagle-import:TP")
      (libsource (lib "eagle-import") (part "TP"))
    )
    (comp (ref "GPIO")
      (value "CON-2X20")
      (footprint "eagle-import:2X20")
      (libsource (lib "eagle-import") (part "CON-2X20"))
    )
    (comp (ref "IC3")
      (value "MP2315GJ-Z")
      (footprint "eagle-import:SOT65P280X110-8N")
      (libsource (lib "eagle-import") (part "MP2315TSOT23-8"))
    )
    (comp (ref "IC8")
      (value "MP2315S")
      (footprint "eagle-import:SOT65P280X110-8N")
      (libsource (lib "eagle-import") (part "MP2315TSOT23-8"))
    )
    (comp (ref "J5")
      (value "694106301002")
      (footprint "eagle-import:694106301002")
      (libsource (lib "eagle-import") (part "694106301002"))
    )
    (comp (ref "L2")
      (value "4.9uH")
      (footprint "eagle-import:SRR5228A")
      (libsource (lib "eagle-import") (part "L"))
    )
    (comp (ref "L3")
      (value "4.2uH")
      (footprint "eagle-import:SRR5228A")
      (libsource (lib "eagle-import") (part "L"))
    )
    (comp (ref "LED1")
      (value "Green")
      (footprint "eagle-import:CHIPLED_0805")
      (libsource (lib "eagle-import") (part "LEDCHIPLED_0805"))
    )
    (comp (ref "LED3")
      (value "Green")
      (footprint "eagle-import:CHIPLED_0805")
      (libsource (lib "eagle-import") (part "LEDCHIPLED_0805"))
    )
    (comp (ref "R5")
      (value "1K")
      (footprint "eagle-import:0402")
      (libsource (lib "eagle-import") (part "R0402"))
    )
    (comp (ref "R6")
      (value "0R")
      (footprint "eagle-import:0402")
      (libsource (lib "eagle-import") (part "R0402"))
    )
    (comp (ref "R7")
      (value "DNI")
      (footprint "eagle-import:0402")
      (libsource (lib "eagle-import") (part "R0402"))
    )
    (comp (ref "R34")
      (value "1K")
      (footprint "eagle-import:0402")
      (libsource (lib "eagle-import") (part "R0402"))
    )
    (comp (ref "R35")
      (value "1K")
      (footprint "eagle-import:0402")
      (libsource (lib "eagle-import") (part "R0402"))
    )
    (comp (ref "R36")
      (value "1K")
      (footprint "eagle-import:0402")
      (libsource (lib "eagle-import") (part "R0402"))
    )
    (comp (ref "R37")
      (value "NC")
      (footprint "eagle-import:0402")
      (libsource (lib "eagle-import") (part "R0402"))
    )
    (comp (ref "R38")
      (value "499K")
      (footprint "eagle-import:0402")
      (libsource (lib "eagle-import") (part "R0402"))
    )
    (comp (ref "R39")
      (value "9.09K")
      (footprint "eagle-import:0402")
      (libsource (lib "eagle-import") (part "R0402"))
    )
    (comp (ref "R40")
      (value "10R")
      (footprint "eagle-import:0402")
      (libsource (lib "eagle-import") (part "R0402"))
    )
    (comp (ref "R41")
      (value "20K")
      (footprint "eagle-import:0402")
      (libsource (lib "eagle-import") (part "R0402"))
    )
    (comp (ref "R42")
      (value "40.2K")
      (footprint "eagle-import:0402")
      (libsource (lib "eagle-import") (part "R0402"))
    )
    (comp (ref "R43")
      (value "7.5K")
      (footprint "eagle-import:0402")
      (libsource (lib "eagle-import") (part "R0402"))
    )
    (comp (ref "R44")
      (value "100K")
      (footprint "eagle-import:0402")
      (libsource (lib "eagle-import") (part "R0402"))
    )
    (comp (ref "R45")
      (value "499K")
      (footprint "eagle-import:0402")
      (libsource (lib "eagle-import") (part "R0402"))
    )
    (comp (ref "R46")
      (value "7.5K")
      (footprint "eagle-import:0402")
      (libsource (lib "eagle-import") (part "R0402"))
    )
    (comp (ref "R47")
      (value "10R")
      (footprint "eagle-import:0402")
      (libsource (lib "eagle-import") (part "R0402"))
    )
    (comp (ref "R48")
      (value "33K")
      (footprint "eagle-import:0402")
      (libsource (lib "eagle-import") (part "R0402"))
    )
    (comp (ref "R49")
      (value "40.2K")
      (footprint "eagle-import:0402")
      (libsource (lib "eagle-import") (part "R0402"))
    )
    (comp (ref "R50")
      (value "12.7K")
      (footprint "eagle-import:0402")
      (libsource (lib "eagle-import") (part "R0402"))
    )
    (comp (ref "R51")
      (value "100K")
      (footprint "eagle-import:0402")
      (libsource (lib "eagle-import") (part "R0402"))
    )
    (comp (ref "SJ1")
      (value "SOLDERJUMPERNO")
      (footprint "eagle-import:SJ_2S-NO")
      (libsource (lib "eagle-import") (part "SOLDERJUMPERNO"))
    )
    (comp (ref "SJ2")
      (value "SOLDERJUMPERNO")
      (footprint "eagle-import:SJ_2S-NO")
      (libsource (lib "eagle-import") (part "SOLDERJUMPERNO"))
    )
    (comp (ref "SJ3")
      (value "SOLDERJUMPERNO")
      (footprint "eagle-import:SJ_2S-NO")
      (libsource (lib "eagle-import") (part "SOLDERJUMPERNO"))
    )
    (comp (ref "SJ4")
      (value "SOLDERJUMPERNO")
      (footprint "eagle-import:SJ_2S-NO")
      (libsource (lib "eagle-import") (part "SOLDERJUMPERNO"))
    )
    (comp (ref "SW") (value "TP") (footprint "eagle-import:TP") (libsource (lib "eagle-import") (part "TP")))
    (comp (ref "SW1")
      (value "1825027-8")
      (footprint "eagle-import:SW2_1825027-C_TEC")
      (fields (field (name "COPYRIGHT") "Copyright (C) 2025 Ultra Librarian. All rights reserved."))
      (libsource (lib "eagle-import") (part "1825027-8"))
    )
    (comp (ref "SW3") (value "TP") (footprint "eagle-import:TP") (libsource (lib "eagle-import") (part "TP")))
    (comp (ref "T6")
      (value "BSS138")
      (footprint "eagle-import:SOT23")
      (libsource (lib "eagle-import") (part "BSS138"))
    )
    (comp (ref "T7")
      (value "BSS138")
      (footprint "eagle-import:SOT23")
      (libsource (lib "eagle-import") (part "BSS138"))
    )
    (comp (ref "T8")
      (value "BSS138")
      (footprint "eagle-import:SOT23")
      (libsource (lib "eagle-import") (part "BSS138"))
    )
    (comp (ref "TP-GREF")
      (value "TP")
      (footprint "eagle-import:TP")
      (libsource (lib "eagle-import") (part "TP"))
    )
    (comp (ref "TP-LED")
      (value "TP")
      (footprint "eagle-import:TP")
      (libsource (lib "eagle-import") (part "TP"))
    )
    (comp (ref "PI1")
      (value "RASPBERRY_CM5")
      (footprint "eagle-import:CM5")
      (libsource (lib "eagle-import") (part "RASPBERRY_CM5"))
    )
    (comp (ref "C3")
      (value "100nF")
      (footprint "eagle-import:C0402")
      (libsource (lib "eagle-import") (part "C-0402"))
    )
    (comp (ref "C4")
      (value "100nF")
      (footprint "eagle-import:C0402")
      (libsource (lib "eagle-import") (part "C-0402"))
    )
    (comp (ref "D3")
      (value "TPD4EUSB30")
      (footprint "eagle-import:USON")
      (libsource (lib "eagle-import") (part "TPD4EUSB30"))
    )
    (comp (ref "D4")
      (value "TPD4EUSB30")
      (footprint "eagle-import:USON")
      (libsource (lib "eagle-import") (part "TPD4EUSB30"))
    )
    (comp (ref "D7")
      (value "TPD4EUSB30")
      (footprint "eagle-import:USON")
      (libsource (lib "eagle-import") (part "TPD4EUSB30"))
    )
    (comp (ref "D8")
      (value "TPD4EUSB30")
      (footprint "eagle-import:USON")
      (libsource (lib "eagle-import") (part "TPD4EUSB30"))
    )
    (comp (ref "D9")
      (value "TPD4EUSB30")
      (footprint "eagle-import:USON")
      (libsource (lib "eagle-import") (part "TPD4EUSB30"))
    )
    (comp (ref "DISP0")
      (value "FH12-22S-0.5SVA")
      (footprint "eagle-import:FH12-22S-0.5SH")
      (libsource (lib "eagle-import") (part "FH12-22S-0.5SVA"))
    )
    (comp (ref "HDMI2")
      (value "685119136923")
      (footprint "eagle-import:685119136923")
      (libsource (lib "eagle-import") (part "685119136923"))
    )
    (comp (ref "IC4")
      (value "RT9742NGV")
      (footprint "eagle-import:SOT23")
      (libsource (lib "eagle-import") (part "RT9742NGV"))
    )
    (comp (ref "ID")
      (value "CON-2X2")
      (footprint "eagle-import:2X2")
      (libsource (lib "eagle-import") (part "CON-2X2"))
    )
    (comp (ref "R3")
      (value "2.2K 1%")
      (footprint "eagle-import:0402")
      (libsource (lib "eagle-import") (part "R0402"))
    )
    (comp (ref "R4")
      (value "2.2K 1%")
      (footprint "eagle-import:0402")
      (libsource (lib "eagle-import") (part "R0402"))
    )
    (comp (ref "TP-5VHD")
      (value "TP")
      (footprint "eagle-import:TP")
      (libsource (lib "eagle-import") (part "TP"))
    )
    (comp (ref "2230")
      (value "M2 x 1mm")
      (footprint "eagle-import:WA-SMSI_9774010243")
      (libsource (lib "eagle-import") (part "WA-SMSI_9774XXX243_9774010243"))
    )
    (comp (ref "2242")
      (value "M2 x 1mm")
      (footprint "eagle-import:WA-SMSI_9774010243")
      (libsource (lib "eagle-import") (part "WA-SMSI_9774XXX243_9774010243"))
    )
    (comp (ref "2260")
      (value "M2 x 1mm")
      (footprint "eagle-import:WA-SMSI_9774010243")
      (libsource (lib "eagle-import") (part "WA-SMSI_9774XXX243_9774010243"))
    )
    (comp (ref "2280")
      (value "M2 x 1mm")
      (footprint "eagle-import:WA-SMSI_9774010243")
      (libsource (lib "eagle-import") (part "WA-SMSI_9774XXX243_9774010243"))
    )
    (comp (ref "C12")
      (value "100nF")
      (footprint "eagle-import:C0402")
      (libsource (lib "eagle-import") (part "C-0402"))
    )
    (comp (ref "C13")
      (value "4.7nF")
      (footprint "eagle-import:C0402")
      (libsource (lib "eagle-import") (part "C-0402"))
    )
    (comp (ref "C14")
      (value "10uF")
      (footprint "eagle-import:C0805")
      (libsource (lib "eagle-import") (part "C-0805"))
    )
    (comp (ref "C15")
      (value "10uF")
      (footprint "eagle-import:C0805")
      (libsource (lib "eagle-import") (part "C-0805"))
    )
    (comp (ref "C16")
      (value "10uF")
      (footprint "eagle-import:C0805")
      (libsource (lib "eagle-import") (part "C-0805"))
    )
    (comp (ref "C17")
      (value "10uF")
      (footprint "eagle-import:C0805")
      (libsource (lib "eagle-import") (part "C-0805"))
    )
    (comp (ref "C18")
      (value "10uF")
      (footprint "eagle-import:C0805")
      (libsource (lib "eagle-import") (part "C-0805"))
    )
    (comp (ref "C19")
      (value "10uF")
      (footprint "eagle-import:C0805")
      (libsource (lib "eagle-import") (part "C-0805"))
    )
    (comp (ref "C20")
      (value "100nF")
      (footprint "eagle-import:C0402")
      (libsource (lib "eagle-import") (part "C-0402"))
    )
    (comp (ref "IC5")
      (value "AP3441SHE-7B")
      (footprint "eagle-import:SON50P201X201X56-9T90X170N")
      (libsource (lib "eagle-import") (part "AP3441SHE-7B"))
    )
    (comp (ref "L1")
      (value "L")
      (footprint "eagle-import:SRR5228A")
      (libsource (lib "eagle-import") (part "L"))
    )
    (comp (ref "LED2")
      (value "LEDCHIPLED_0805")
      (footprint "eagle-import:CHIPLED_0805")
      (libsource (lib "eagle-import") (part "LEDCHIPLED_0805"))
    )
    (comp (ref "PCIE")
      (value "M.2")
      (footprint "eagle-import:PCIE_M.2")
      (libsource (lib "eagle-import") (part "M.2"))
    )
    (comp (ref "R10")
      (value "1K")
      (footprint "eagle-import:0402")
      (libsource (lib "eagle-import") (part "R0402"))
    )
    (comp (ref "R11")
      (value "100K 1%")
      (footprint "eagle-import:0402")
      (libsource (lib "eagle-import") (part "R0402"))
    )
    (comp (ref "R12")
      (value "10K 1%")
      (footprint "eagle-import:0402")
      (libsource (lib "eagle-import") (part "R0402"))
    )
    (comp (ref "R13")
      (value "2.2K 1%")
      (footprint "eagle-import:0402")
      (libsource (lib "eagle-import") (part "R0402"))
    )
    (comp (ref "R14")
      (value "10K")
      (footprint "eagle-import:0402")
      (libsource (lib "eagle-import") (part "R0402"))
    )
    (comp (ref "R15")
      (value "NC")
      (footprint "eagle-import:0402")
      (libsource (lib "eagle-import") (part "R0402"))
    )
    (comp (ref "R16")
      (value "2.2K")
      (footprint "eagle-import:0402")
      (libsource (lib "eagle-import") (part "R0402"))
    )
    (comp (ref "R17")
      (value "10K")
      (footprint "eagle-import:0402")
      (libsource (lib "eagle-import") (part "R0402"))
    )
    (comp (ref "R18")
      (value "10K")
      (footprint "eagle-import:0402")
      (libsource (lib "eagle-import") (part "R0402"))
    )
    (comp (ref "R19")
      (value "10K")
      (footprint "eagle-import:0402")
      (libsource (lib "eagle-import") (part "R0402"))
    )
    (comp (ref "R20")
      (value "NC")
      (footprint "eagle-import:0402")
      (libsource (lib "eagle-import") (part "R0402"))
    )
    (comp (ref "R21")
      (value "3.6K 1%")
      (footprint "eagle-import:0402")
      (libsource (lib "eagle-import") (part "R0402"))
    )
    (comp (ref "R22")
      (value "6.8K 1%")
      (footprint "eagle-import:0402")
      (libsource (lib "eagle-import") (part "R0402"))
    )
    (comp (ref "T1")
      (value "BSS138")
      (footprint "eagle-import:SOT23")
      (libsource (lib "eagle-import") (part "BSS138"))
    )
    (comp (ref "T2")
      (value "BSS138")
      (footprint "eagle-import:SOT23")
      (libsource (lib "eagle-import") (part "BSS138"))
    )
    (comp (ref "T3")
      (value "BSS138")
      (footprint "eagle-import:SOT23")
      (libsource (lib "eagle-import") (part "BSS138"))
    )
    (comp (ref "T4")
      (value "BSS138")
      (footprint "eagle-import:SOT23")
      (libsource (lib "eagle-import") (part "BSS138"))
    )
    (comp (ref "TP-5VP")
      (value "TP")
      (footprint "eagle-import:TP")
      (libsource (lib "eagle-import") (part "TP"))
    )
    (comp (ref "TP-LX")
      (value "TP")
      (footprint "eagle-import:TP")
      (libsource (lib "eagle-import") (part "TP"))
    )
    (comp (ref "TP-M2CLK")
      (value "TP")
      (footprint "eagle-import:TP")
      (libsource (lib "eagle-import") (part "TP"))
    )
    (comp (ref "TP-M2FB")
      (value "TP")
      (footprint "eagle-import:TP")
      (libsource (lib "eagle-import") (part "TP"))
    )
    (comp (ref "TP-VM2")
      (value "TP")
      (footprint "eagle-import:TP")
      (libsource (lib "eagle-import") (part "TP"))
    )
    (comp (ref "X2")
      (value "CRYSTAL")
      (footprint "eagle-import:OSCCC500X320X130")
      (libsource (lib "eagle-import") (part "CRYSTAL"))
    )
  )
  (nets
    (net (code "1") (name "+1V8") (class "Default")
      (node (ref "PI1") (pin "87") (pinfunction "87_87") (pintype "passive"))
      (node (ref "PI1") (pin "89") (pinfunction "89_89") (pintype "passive"))
      (node (ref "R7") (pin "1") (pinfunction "1_1") (pintype "passive"))
    )
    (net (code "2") (name "+3V3") (class "Default")
      (node (ref "3VDC") (pin "TP") (pinfunction "P$1_TP") (pintype "bidirectional"))
      (node (ref "C45") (pin "1") (pinfunction "1_1") (pintype "passive"))
      (node (ref "C47") (pin "1") (pinfunction "1_1") (pintype "passive"))
      (node (ref "C48") (pin "1") (pinfunction "1_1") (pintype "passive"))
      (node (ref "C55") (pin "1") (pinfunction "1_1") (pintype "passive"))
      (node (ref "C56") (pin "1") (pinfunction "1_1") (pintype "passive"))
      (node (ref "DISP0") (pin "22") (pinfunction "22_22") (pintype "passive"))
      (node (ref "ETH1") (pin "18") (pinfunction "P18_18") (pintype "bidirectional"))
      (node (ref "ETH1") (pin "20") (pinfunction "P20_20") (pintype "bidirectional"))
      (node (ref "GPIO") (pin "1") (pinfunction "1_1") (pintype "bidirectional"))
      (node (ref "GPIO") (pin "17") (pinfunction "17_17") (pintype "bidirectional"))
      (node (ref "IC1") (pin "5") (pinfunction "IN_5") (pintype "power_in"))
      (node (ref "IC6") (pin "19") (pinfunction "V5_19") (pintype "power_in"))
      (node (ref "IC6") (pin "20") (pinfunction "VDD33_20") (pintype "power_in"))
      (node (ref "J1") (pin "1") (pinfunction "1_1") (pintype "bidirectional"))
      (node (ref "J3") (pin "1") (pinfunction "1_1") (pintype "bidirectional"))
      (node (ref "L3") (pin "2") (pinfunction "2_2") (pintype "passive"))
      (node (ref "LED2") (pin "A") (pinfunction "A_A") (pintype "passive"))
      (node (ref "PI1") (pin "83") (pinfunction "83_83") (pintype "passive"))
      (node (ref "PI1") (pin "85") (pinfunction "85_85") (pintype "passive"))
      (node (ref "R14") (pin "1") (pinfunction "1_1") (pintype "passive"))
      (node (ref "R17") (pin "1") (pinfunction "1_1") (pintype "passive"))
      (node (ref "R18") (pin "1") (pinfunction "1_1") (pintype "passive"))
      (node (ref "R19") (pin "1") (pinfunction "1_1") (pintype "passive"))
      (node (ref "R32") (pin "1") (pinfunction "1_1") (pintype "passive"))
      (node (ref "R34") (pin "1") (pinfunction "1_1") (pintype "passive"))
      (node (ref "R36") (pin "1") (pinfunction "1_1") (pintype "passive"))
      (node (ref "R49") (pin "1") (pinfunction "1_1") (pintype "passive"))
      (node (ref "R5") (pin "1") (pinfunction "1_1") (pintype "passive"))
      (node (ref "R6") (pin "1") (pinfunction "1_1") (pintype "passive"))
      (node (ref "T1") (pin "1") (pinfunction "G_1") (pintype "passive"))
      (node (ref "T4") (pin "1") (pinfunction "G_1") (pintype "passive"))
    )
    (net (code "3") (name "+5V") (class "Default")
      (node (ref "5VDC") (pin "TP") (pinfunction "P$1_TP") (pintype "bidirectional"))
      (node (ref "C1") (pin "1") (pinfunction "1_1") (pintype "passive"))
      (node (ref "C18") (pin "1") (pinfunction "1_1") (pintype "passive"))
      (node (ref "C19") (pin "1") (pinfunction "1_1") (pintype "passive"))
      (node (ref "C20") (pin "1") (pinfunction "1_1") (pintype "passive"))
      (node (ref "C22") (pin "1") (pinfunction "1_1") (pintype "passive"))
      (node (ref "C23") (pin "1") (pinfunction "1_1") (pintype "passive"))
      (node (ref "C24") (pin "1") (pinfunction "1_1") (pintype "passive"))
      (node (ref "C25") (pin "1") (pinfunction "1_1") (pintype "passive"))
      (node (ref "C3") (pin "1") (pinfunction "1_1") (pintype "passive"))
      (node (ref "C32") (pin "1") (pinfunction "1_1") (pintype "passive"))
      (node (ref "C38") (pin "1") (pinfunction "1_1") (pintype "passive"))
      (node (ref "C40") (pin "1") (pinfunction "1_1") (pintype "passive"))
      (node (ref "C41") (pin "1") (pinfunction "1_1") (pintype "passive"))
      (node (ref "C5") (pin "1") (pinfunction "1_1") (pintype "passive"))
      (node (ref "GPIO") (pin "2") (pinfunction "2_2") (pintype "bidirectional"))
      (node (ref "GPIO") (pin "4") (pinfunction "4_4") (pintype "bidirectional"))
      (node (ref "IC2") (pin "1") (pinfunction "IN_1") (pintype "bidirectional"))
      (node (ref "IC4") (pin "1") (pinfunction "IN_1") (pintype "power_in"))
      (node (ref "IC5") (pin "3") (pinfunction "VIN_3") (pintype "power_in"))
      (node (ref "IC7") (pin "1") (pinfunction "IN_1") (pintype "bidirectional"))
      (node (ref "J1") (pin "8") (pinfunction "8_8") (pintype "bidirectional"))
      (node (ref "J1") (pin "9") (pinfunction "9_9") (pintype "bidirectional"))
      (node (ref "J3") (pin "8") (pinfunction "8_8") (pintype "bidirectional"))
      (node (ref "J3") (pin "9") (pinfunction "9_9") (pintype "bidirectional"))
      (node (ref "L2") (pin "2") (pinfunction "2_2") (pintype "passive"))
      (node (ref "PI1") (pin "78") (pinfunction "78_78") (pintype "passive"))
      (node (ref "PI1") (pin "80") (pinfunction "80_80") (pintype "passive"))
      (node (ref "PI1") (pin "82") (pinfunction "82_82") (pintype "passive"))
      (node (ref "PI1") (pin "84") (pinfunction "84_84") (pintype "passive"))
      (node (ref "PI1") (pin "86") (pinfunction "86_86") (pintype "passive"))
      (node (ref "PI1") (pin "88") (pinfunction "88_88") (pintype "passive"))
      (node (ref "Q2") (pin "2") (pinfunction "E_2") (pintype "passive"))
      (node (ref "R20") (pin "1") (pinfunction "1_1") (pintype "passive"))
      (node (ref "R42") (pin "1") (pinfunction "1_1") (pintype "passive"))
      (node (ref "T5") (pin "1") (pinfunction "S_1") (pintype "passive"))
      (node (ref "T5") (pin "2") (pinfunction "S_2") (pintype "passive"))
      (node (ref "T5") (pin "3") (pinfunction "S_3") (pintype "passive"))
      (node (ref "TP-5VP") (pin "TP") (pinfunction "P$1_TP") (pintype "bidirectional"))
      (node (ref "TP_5VP") (pin "TP") (pinfunction "P$1_TP") (pintype "bidirectional"))
      (node (ref "TP_5VP1") (pin "TP") (pinfunction "P$1_TP") (pintype "bidirectional"))
    )
    (net (code "4") (name "+12V") (class "Default")
      (node (ref "C39") (pin "1") (pinfunction "1_1") (pintype "passive"))
      (node (ref "C42") (pin "1") (pinfunction "1_1") (pintype "passive"))
      (node (ref "C46") (pin "1") (pinfunction "1_1") (pintype "passive"))
      (node (ref "C51") (pin "1") (pinfunction "1_1") (pintype "passive"))
      (node (ref "C52") (pin "1") (pinfunction "1_1") (pintype "passive"))
      (node (ref "C53") (pin "1") (pinfunction "1_1") (pintype "passive"))
      (node (ref "C54") (pin "1") (pinfunction "1_1") (pintype "passive"))
      (node (ref "C9") (pin "1") (pinfunction "1_1") (pintype "passive"))
      (node (ref "D24") (pin "C") (pinfunction "C_C") (pintype "passive"))
      (node (ref "IC3") (pin "2") (pinfunction "IN_2") (pintype "bidirectional"))
      (node (ref "IC8") (pin "2") (pinfunction "IN_2") (pintype "bidirectional"))
      (node (ref "R38") (pin "1") (pinfunction "1_1") (pintype "passive"))
      (node (ref "R45") (pin "1") (pinfunction "1_1") (pintype "passive"))
    )
    (net (code "5") (name "BT_NDIS") (class "Default")
      (node (ref "PI1") (pin "92") (pinfunction "92_92") (pintype "passive"))
    )
    (net (code "6") (name "CAM_GPIO0") (class "Default")
      (node (ref "DISP0") (pin "17") (pinfunction "17_17") (pintype "passive"))
      (node (ref "PI1") (pin "98") (pinfunction "98_98") (pintype "passive"))
    )
    (net (code "7") (name "CAM_GPIO1") (class "Default")
      (node (ref "DISP0") (pin "18") (pinfunction "18_18") (pintype "passive"))
      (node (ref "PI1") (pin "99") (pinfunction "99_99") (pintype "passive"))
    )
    (net (code "8") (name "CC1") (class "Default")
      (node (ref "PI1") (pin "93") (pinfunction "93_93") (pintype "passive"))
      (node (ref "R25") (pin "1") (pinfunction "1_1") (pintype "passive"))
      (node (ref "USBC") (pin "A5") (pinfunction "CC1_A5") (pintype "passive"))
    )
    (net (code "9") (name "CC2") (class "Default")
      (node (ref "PI1") (pin "95") (pinfunction "95_95") (pintype "passive"))
      (node (ref "R26") (pin "1") (pinfunction "1_1") (pintype "passive"))
      (node (ref "USBC") (pin "B5") (pinfunction "CC2_B5") (pintype "passive"))
    )
    (net (code "10") (name "DPHY1_DSIC_N") (class "Default")
      (node (ref "D8") (pin "5") (pinfunction "D2-_5") (pintype "bidirectional"))
      (node (ref "D8") (pin "6") (pinfunction "D2-_6") (pintype "bidirectional"))
      (node (ref "DISP0") (pin "8") (pinfunction "8_8") (pintype "passive"))
      (node (ref "PI1") (pin "188") (pinfunction "88_188") (pintype "passive"))
    )
    (net (code "11") (name "DPHY1_DSIC_P") (class "Default")
      (node (ref "D8") (pin "4") (pinfunction "D2+_4") (pintype "bidirectional"))
      (node (ref "D8") (pin "7") (pinfunction "D2+_7") (pintype "bidirectional"))
      (node (ref "DISP0") (pin "9") (pinfunction "9_9") (pintype "passive"))
      (node (ref "PI1") (pin "190") (pinfunction "90_190") (pintype "passive"))
    )
    (net (code "12") (name "DPHY1_DSID0_N") (class "Default")
      (node (ref "D7") (pin "5") (pinfunction "D2-_5") (pintype "bidirectional"))
      (node (ref "D7") (pin "6") (pinfunction "D2-_6") (pintype "bidirectional"))
      (node (ref "DISP0") (pin "2") (pinfunction "2_2") (pintype "passive"))
      (node (ref "PI1") (pin "176") (pinfunction "76_176") (pintype "passive"))
    )
    (net (code "13") (name "DPHY1_DSID0_P") (class "Default")
      (node (ref "D7") (pin "4") (pinfunction "D2+_4") (pintype "bidirectional"))
      (node (ref "D7") (pin "7") (pinfunction "D2+_7") (pintype "bidirectional"))
      (node (ref "DISP0") (pin "3") (pinfunction "3_3") (pintype "passive"))
      (node (ref "PI1") (pin "178") (pinfunction "78_178") (pintype "passive"))
    )
    (net (code "14") (name "DPHY1_DSID1_N") (class "Default")
      (node (ref "D7") (pin "2") (pinfunction "D1-_2") (pintype "bidirectional"))
      (node (ref "D7") (pin "9") (pinfunction "D1-_9") (pintype "bidirectional"))
      (node (ref "DISP0") (pin "5") (pinfunction "5_5") (pintype "passive"))
      (node (ref "PI1") (pin "182") (pinfunction "82_182") (pintype "passive"))
    )
    (net (code "15") (name "DPHY1_DSID1_P") (class "Default")
      (node (ref "D7") (pin "1") (pinfunction "D1+_1") (pintype "bidirectional"))
      (node (ref "D7") (pin "10") (pinfunction "D1+_10") (pintype "bidirectional"))
      (node (ref "DISP0") (pin "6") (pinfunction "6_6") (pintype "passive"))
      (node (ref "PI1") (pin "184") (pinfunction "84_184") (pintype "passive"))
    )
    (net (code "16") (name "DPHY1_DSID2_N") (class "Default")
      (node (ref "D8") (pin "2") (pinfunction "D1-_2") (pintype "bidirectional"))
      (node (ref "D8") (pin "9") (pinfunction "D1-_9") (pintype "bidirectional"))
      (node (ref "DISP0") (pin "11") (pinfunction "11_11") (pintype "passive"))
      (node (ref "PI1") (pin "194") (pinfunction "94_194") (pintype "passive"))
    )
    (net (code "17") (name "DPHY1_DSID2_P") (class "Default")
      (node (ref "D8") (pin "1") (pinfunction "D1+_1") (pintype "bidirectional"))
      (node (ref "D8") (pin "10") (pinfunction "D1+_10") (pintype "bidirectional"))
      (node (ref "DISP0") (pin "12") (pinfunction "12_12") (pintype "passive"))
      (node (ref "PI1") (pin "196") (pinfunction "96_196") (pintype "passive"))
    )
    (net (code "18") (name "DPHY1_DSID3_N") (class "Default")
      (node (ref "D9") (pin "5") (pinfunction "D2-_5") (pintype "bidirectional"))
      (node (ref "D9") (pin "6") (pinfunction "D2-_6") (pintype "bidirectional"))
      (node (ref "DISP0") (pin "14") (pinfunction "14_14") (pintype "passive"))
      (node (ref "PI1") (pin "193") (pinfunction "93_193") (pintype "passive"))
    )
    (net (code "19") (name "DPHY1_DSID3_P") (class "Default")
      (node (ref "D9") (pin "4") (pinfunction "D2+_4") (pintype "bidirectional"))
      (node (ref "D9") (pin "7") (pinfunction "D2+_7") (pintype "bidirectional"))
      (node (ref "DISP0") (pin "15") (pinfunction "15_15") (pintype "passive"))
      (node (ref "PI1") (pin "195") (pinfunction "95_195") (pintype "passive"))
    )
    (net (code "20") (name "EEPROM_NWP") (class "Default")
      (node (ref "PI1") (pin "19") (pinfunction "19_19") (pintype "passive"))
      (node (ref "SJ1") (pin "2") (pinfunction "2_2") (pintype "passive"))
    )
    (net (code "21") (name "ETH_LEDG") (class "Default")
      (node (ref "PI1") (pin "18") (pinfunction "18_18") (pintype "passive"))
      (node (ref "R8") (pin "1") (pinfunction "1_1") (pintype "passive"))
    )
    (net (code "22") (name "ETH_LEDY") (class "Default")
      (node (ref "PI1") (pin "16") (pinfunction "16_16") (pintype "passive"))
      (node (ref "R9") (pin "2") (pinfunction "2_2") (pintype "passive"))
    )
    (net (code "23") (name "ETH_TX1_N") (class "Default")
      (node (ref "D2") (pin "2") (pinfunction "D1-_2") (pintype "bidirectional"))
      (node (ref "D2") (pin "9") (pinfunction "D1-_9") (pintype "bidirectional"))
      (node (ref "ETH1") (pin "TD1-") (pinfunction "TD1-_TD1-") (pintype "bidirectional"))
      (node (ref "PI1") (pin "9") (pinfunction "9_9") (pintype "passive"))
    )
    (net (code "24") (name "ETH_TX1_P") (class "Default")
      (node (ref "D2") (pin "1") (pinfunction "D1+_1") (pintype "bidirectional"))
      (node (ref "D2") (pin "10") (pinfunction "D1+_10") (pintype "bidirectional"))
      (node (ref "ETH1") (pin "TD1+") (pinfunction "TD1+_TD1+") (pintype "bidirectional"))
      (node (ref "PI1") (pin "11") (pinfunction "11_11") (pintype "passive"))
    )
    (net (code "25") (name "ETH_TX2_N") (class "Default")
      (node (ref "D2") (pin "4") (pinfunction "D2+_4") (pintype "bidirectional"))
      (node (ref "D2") (pin "7") (pinfunction "D2+_7") (pintype "bidirectional"))
      (node (ref "ETH1") (pin "TD2-") (pinfunction "TD2-_TD2-") (pintype "bidirectional"))
      (node (ref "PI1") (pin "5") (pinfunction "5_5") (pintype "passive"))
    )
    (net (code "26") (name "ETH_TX2_P") (class "Default")
      (node (ref "D2") (pin "5") (pinfunction "D2-_5") (pintype "bidirectional"))
      (node (ref "D2") (pin "6") (pinfunction "D2-_6") (pintype "bidirectional"))
      (node (ref "ETH1") (pin "TD2+") (pinfunction "TD2+_TD2+") (pintype "bidirectional"))
      (node (ref "PI1") (pin "3") (pinfunction "3_3") (pintype "passive"))
    )
    (net (code "27") (name "ETH_TX3_N") (class "Default")
      (node (ref "D1") (pin "4") (pinfunction "D2+_4") (pintype "bidirectional"))
      (node (ref "D1") (pin "7") (pinfunction "D2+_7") (pintype "bidirectional"))
      (node (ref "ETH1") (pin "TD3-") (pinfunction "TD3-_TD3-") (pintype "bidirectional"))
      (node (ref "PI1") (pin "10") (pinfunction "10_10") (pintype "passive"))
    )
    (net (code "28") (name "ETH_TX3_P") (class "Default")
      (node (ref "D1") (pin "5") (pinfunction "D2-_5") (pintype "bidirectional"))
      (node (ref "D1") (pin "6") (pinfunction "D2-_6") (pintype "bidirectional"))
      (node (ref "ETH1") (pin "TD3+") (pinfunction "TD3+_TD3+") (pintype "bidirectional"))
      (node (ref "PI1") (pin "12") (pinfunction "12_12") (pintype "passive"))
    )
    (net (code "29") (name "ETH_TX4_N") (class "Default")
      (node (ref "D1") (pin "2") (pinfunction "D1-_2") (pintype "bidirectional"))
      (node (ref "D1") (pin "9") (pinfunction "D1-_9") (pintype "bidirectional"))
      (node (ref "ETH1") (pin "TD4-") (pinfunction "TD4-_TD4-") (pintype "bidirectional"))
      (node (ref "PI1") (pin "6") (pinfunction "6_6") (pintype "passive"))
    )
    (net (code "30") (name "ETH_TX4_P") (class "Default")
      (node (ref "D1") (pin "1") (pinfunction "D1+_1") (pintype "bidirectional"))
      (node (ref "D1") (pin "10") (pinfunction "D1+_10") (pintype "bidirectional"))
      (node (ref "ETH1") (pin "TD4+") (pinfunction "TD4+_TD4+") (pintype "bidirectional"))
      (node (ref "PI1") (pin "4") (pinfunction "4_4") (pintype "passive"))
    )
    (net (code "31") (name "GND") (class "Default")
      (node (ref "2230") (pin "1") (pinfunction "1_1") (pintype "passive"))
      (node (ref "2242") (pin "1") (pinfunction "1_1") (pintype "passive"))
      (node (ref "2260") (pin "1") (pinfunction "1_1") (pintype "passive"))
      (node (ref "2280") (pin "1") (pinfunction "1_1") (pintype "passive"))
      (node (ref "C1") (pin "2") (pinfunction "2_2") (pintype "passive"))
      (node (ref "C10") (pin "2") (pinfunction "2_2") (pintype "passive"))
      (node (ref "C11") (pin "2") (pinfunction "2_2") (pintype "passive"))
      (node (ref "C12") (pin "2") (pinfunction "2_2") (pintype "passive"))
      (node (ref "C14") (pin "2") (pinfunction "2_2") (pintype "passive"))
      (node (ref "C15") (pin "2") (pinfunction "2_2") (pintype "passive"))
      (node (ref "C16") (pin "2") (pinfunction "2_2") (pintype "passive"))
      (node (ref "C17") (pin "2") (pinfunction "2_2") (pintype "passive"))
      (node (ref "C18") (pin "2") (pinfunction "2_2") (pintype "passive"))
      (node (ref "C19") (pin "2") (pinfunction "2_2") (pintype "passive"))
      (node (ref "C2") (pin "2") (pinfunction "2_2") (pintype "passive"))
      (node (ref "C20") (pin "2") (pinfunction "2_2") (pintype "passive"))
      (node (ref "C21") (pin "2") (pinfunction "2_2") (pintype "passive"))
      (node (ref "C22") (pin "2") (pinfunction "2_2") (pintype "passive"))
      (node (ref "C23") (pin "2") (pinfunction "2_2") (pintype "passive"))
      (node (ref "C24") (pin "2") (pinfunction "2_2") (pintype "passive"))
      (node (ref "C25") (pin "2") (pinfunction "2_2") (pintype "passive"))
      (node (ref "C26") (pin "2") (pinfunction "2_2") (pintype "passive"))
      (node (ref "C27") (pin "2") (pinfunction "2_2") (pintype "passive"))
      (node (ref "C3") (pin "2") (pinfunction "2_2") (pintype "passive"))
      (node (ref "C32") (pin "2") (pinfunction "2_2") (pintype "passive"))
      (node (ref "C33") (pin "2") (pinfunction "2_2") (pintype "passive"))
      (node (ref "C34") (pin "2") (pinfunction "2_2") (pintype "passive"))
      (node (ref "C35") (pin "2") (pinfunction "2_2") (pintype "passive"))
      (node (ref "C36") (pin "2") (pinfunction "2_2") (pintype "passive"))
      (node (ref "C39") (pin "2") (pinfunction "2_2") (pintype "passive"))
      (node (ref "C4") (pin "2") (pinfunction "2_2") (pintype "passive"))
      (node (ref "C40") (pin "2") (pinfunction "2_2") (pintype "passive"))
      (node (ref "C41") (pin "2") (pinfunction "2_2") (pintype "passive"))
      (node (ref "C42") (pin "2") (pinfunction "2_2") (pintype "passive"))
      (node (ref "C43") (pin "2") (pinfunction "2_2") (pintype "passive"))
      (node (ref "C46") (pin "2") (pinfunction "2_2") (pintype "passive"))
      (node (ref "C47") (pin "2") (pinfunction "2_2") (pintype "passive"))
      (node (ref "C48") (pin "2") (pinfunction "2_2") (pintype "passive"))
      (node (ref "C49") (pin "2") (pinfunction "2_2") (pintype "passive"))
      (node (ref "C5") (pin "2") (pinfunction "2_2") (pintype "passive"))
      (node (ref "C50") (pin "2") (pinfunction "2_2") (pintype "passive"))
      (node (ref "C51") (pin "2") (pinfunction "2_2") (pintype "passive"))
      (node (ref "C52") (pin "2") (pinfunction "2_2") (pintype "passive"))
      (node (ref "C53") (pin "2") (pinfunction "2_2") (pintype "passive"))
      (node (ref "C54") (pin "2") (pinfunction "2_2") (pintype "passive"))
      (node (ref "C55") (pin "2") (pinfunction "2_2") (pintype "passive"))
      (node (ref "C56") (pin "2") (pinfunction "2_2") (pintype "passive"))
      (node (ref "C6") (pin "2") (pinfunction "2_2") (pintype "passive"))
      (node (ref "C7") (pin "2") (pinfunction "2_2") (pintype "passive"))
      (node (ref "C8") (pin "2") (pinfunction "2_2") (pintype "passive"))
      (node (ref "C9") (pin "2") (pinfunction "2_2") (pintype "passive"))
      (node (ref "D1") (pin "3") (pinfunction "GND_3") (pintype "bidirectional"))
      (node (ref "D1") (pin "8") (pinfunction "GND_8") (pintype "bidirectional"))
      (node (ref "D13") (pin "3") (pinfunction "GND_3") (pintype "bidirectional"))
      (node (ref "D13") (pin "8") (pinfunction "GND_8") (pintype "bidirectional"))
      (node (ref "D14") (pin "3") (pinfunction "GND_3") (pintype "bidirectional"))
      (node (ref "D14") (pin "8") (pinfunction "GND_8") (pintype "bidirectional"))
      (node (ref "D15") (pin "3") (pinfunction "GND_3") (pintype "bidirectional"))
      (node (ref "D15") (pin "8") (pinfunction "GND_8") (pintype "bidirectional"))
      (node (ref "D16") (pin "3") (pinfunction "GND_3") (pintype "bidirectional"))
      (node (ref "D16") (pin "8") (pinfunction "GND_8") (pintype "bidirectional"))
      (node (ref "D17") (pin "2") (pinfunction "GND_2") (pintype "passive"))
      (node (ref "D18") (pin "2") (pinfunction "GND_2") (pintype "passive"))
      (node (ref "D19") (pin "2") (pinfunction "GND_2") (pintype "passive"))
      (node (ref "D2") (pin "3") (pinfunction "GND_3") (pintype "bidirectional"))
      (node (ref "D2") (pin "8") (pinfunction "GND_8") (pintype "bidirectional"))
      (node (ref "D20") (pin "2") (pinfunction "GND_2") (pintype "passive"))
      (node (ref "D21") (pin "2") (pinfunction "GND_2") (pintype "passive"))
      (node (ref "D22") (pin "2") (pinfunction "GND_2") (pintype "passive"))
      (node (ref "D23") (pin "2") (pinfunction "GND_2") (pintype "passive"))
      (node (ref "D3") (pin "3") (pinfunction "GND_3") (pintype "bidirectional"))
      (node (ref "D3") (pin "8") (pinfunction "GND_8") (pintype "bidirectional"))
      (node (ref "D4") (pin "3") (pinfunction "GND_3") (pintype "bidirectional"))
      (node (ref "D4") (pin "8") (pinfunction "GND_8") (pintype "bidirectional"))
      (node (ref "D7") (pin "3") (pinfunction "GND_3") (pintype "bidirectional"))
      (node (ref "D7") (pin "8") (pinfunction "GND_8") (pintype "bidirectional"))
      (node (ref "D8") (pin "3") (pinfunction "GND_3") (pintype "bidirectional"))
      (node (ref "D8") (pin "8") (pinfunction "GND_8") (pintype "bidirectional"))
      (node (ref "D9") (pin "3") (pinfunction "GND_3") (pintype "bidirectional"))
      (node (ref "D9") (pin "8") (pinfunction "GND_8") (pintype "bidirectional"))
      (node (ref "DISP0") (pin "1") (pinfunction "1_1") (pintype "passive"))
      (node (ref "DISP0") (pin "10") (pinfunction "10_10") (pintype "passive"))
      (node (ref "DISP0") (pin "13") (pinfunction "13_13") (pintype "passive"))
      (node (ref "DISP0") (pin "16") (pinfunction "16_16") (pintype "passive"))
      (node (ref "DISP0") (pin "19") (pinfunction "19_19") (pintype "passive"))
      (node (ref "DISP0") (pin "23") (pinfunction "MH1_23") (pintype "passive"))
      (node (ref "DISP0") (pin "24") (pinfunction "MH2_24") (pintype "passive"))
      (node (ref "DISP0") (pin "25") (pinfunction "MH1_25") (pintype "passive"))
      (node (ref "DISP0") (pin "26") (pinfunction "MH2_26") (pintype "passive"))
      (node (ref "DISP0") (pin "4") (pinfunction "4_4") (pintype "passive"))
      (node (ref "DISP0") (pin "7") (pinfunction "7_7") (pintype "passive"))
      (node (ref "ETH1") (pin "MH3") (pinfunction "SHIELD_MH3") (pintype "bidirectional"))
      (node (ref "ETH1") (pin "MH4") (pinfunction "SHIELD_MH4") (pintype "bidirectional"))
      (node (ref "GND") (pin "TP") (pinfunction "P$1_TP") (pintype "bidirectional"))
      (node (ref "GND-3") (pin "TP") (pinfunction "P$1_TP") (pintype "bidirectional"))
      (node (ref "GND-5") (pin "TP") (pinfunction "P$1_TP") (pintype "bidirectional"))
      (node (ref "GPIO") (pin "14") (pinfunction "14_14") (pintype "bidirectional"))
      (node (ref "GPIO") (pin "20") (pinfunction "20_20") (pintype "bidirectional"))
      (node (ref "GPIO") (pin "25") (pinfunction "25_25") (pintype "bidirectional"))
      (node (ref "GPIO") (pin "30") (pinfunction "30_30") (pintype "bidirectional"))
      (node (ref "GPIO") (pin "34") (pinfunction "34_34") (pintype "bidirectional"))
      (node (ref "GPIO") (pin "39") (pinfunction "39_39") (pintype "bidirectional"))
      (node (ref "GPIO") (pin "6") (pinfunction "6_6") (pintype "bidirectional"))
      (node (ref "GPIO") (pin "9") (pinfunction "9_9") (pintype "bidirectional"))
      (node (ref "HDMI2") (pin "11") (pinfunction "TMDSCLOCK+_11") (pintype "passive"))
      (node (ref "HDMI2") (pin "17") (pinfunction "UTILITY/HEAC+_17") (pintype "passive"))
      (node (ref "HDMI2") (pin "2") (pinfunction "TMDS2+_2") (pintype "passive"))
      (node (ref "HDMI2") (pin "5") (pinfunction "TMDSDATA1+_5") (pintype "passive"))
      (node (ref "HDMI2") (pin "8") (pinfunction "TMDS0+_8") (pintype "passive"))
      (node (ref "HDMI2") (pin "S1") (pinfunction "SHIELD_S1") (pintype "passive"))
      (node (ref "HDMI2") (pin "S2") (pinfunction "SHIELD_S2") (pintype "passive"))
      (node (ref "HDMI2") (pin "S3") (pinfunction "SHIELD_S3") (pintype "passive"))
      (node (ref "HDMI2") (pin "S4") (pinfunction "SHIELD_S4") (pintype "passive"))
      (node (ref "IC1") (pin "2") (pinfunction "GND_2") (pintype "power_in"))
      (node (ref "IC2") (pin "2") (pinfunction "GND_2") (pintype "bidirectional"))
      (node (ref "IC3") (pin "4") (pinfunction "GND_4") (pintype "bidirectional"))
      (node (ref "IC4") (pin "3") (pinfunction "GND_3") (pintype "power_in"))
      (node (ref "IC5") (pin "4") (pinfunction "PGND_4") (pintype "power_in"))
      (node (ref "IC5") (pin "8") (pinfunction "SGND_8") (pintype "power_in"))
      (node (ref "IC5") (pin "9") (pinfunction "PGND_9") (pintype "power_in"))
      (node (ref "IC6") (pin "25") (pinfunction "GND_25") (pintype "power_in"))
      (node (ref "IC7") (pin "2") (pinfunction "GND_2") (pintype "bidirectional"))
      (node (ref "IC8") (pin "4") (pinfunction "GND_4") (pintype "bidirectional"))
      (node (ref "J2") (pin "13") (pinfunction "13_13") (pintype "bidirectional"))
      (node (ref "J2") (pin "18") (pinfunction "18_18") (pintype "bidirectional"))
      (node (ref "J2") (pin "19") (pinfunction "19_19") (pintype "bidirectional"))
      (node (ref "J2") (pin "20") (pinfunction "20_20") (pintype "bidirectional"))
      (node (ref "J2") (pin "7") (pinfunction "7_7") (pintype "bidirectional"))
      (node (ref "J3") (pin "13") (pinfunction "13_13") (pintype "bidirectional"))
      (node (ref "J3") (pin "14") (pinfunction "14_14") (pintype "bidirectional"))
      (node (ref "J3") (pin "15") (pinfunction "15_15") (pintype "bidirectional"))
      (node (ref "J3") (pin "16") (pinfunction "16_16") (pintype "bidirectional"))
      (node (ref "J3") (pin "17") (pinfunction "17_17") (pintype "bidirectional"))
      (node (ref "J3") (pin "18") (pinfunction "18_18") (pintype "bidirectional"))
      (node (ref "J3") (pin "19") (pinfunction "19_19") (pintype "bidirectional"))
      (node (ref "J3") (pin "20") (pinfunction "20_20") (pintype "bidirectional"))
      (node (ref "J3") (pin "7") (pinfunction "7_7") (pintype "bidirectional"))
      (node (ref "J4") (pin "13") (pinfunction "13_13") (pintype "bidirectional"))
      (node (ref "J4") (pin "18") (pinfunction "18_18") (pintype "bidirectional"))
      (node (ref "J4") (pin "19") (pinfunction "19_19") (pintype "bidirectional"))
      (node (ref "J4") (pin "20") (pinfunction "20_20") (pintype "bidirectional"))
      (node (ref "J4") (pin "4") (pinfunction "4_4") (pintype "bidirectional"))
      (node (ref "J4") (pin "5") (pinfunction "5_5") (pintype "bidirectional"))
      (node (ref "J4") (pin "6") (pinfunction "6_6") (pintype "bidirectional"))
      (node (ref "J4") (pin "7") (pinfunction "7_7") (pintype "bidirectional"))
      (node (ref "J5") (pin "2") (pinfunction "2_2") (pintype "passive"))
      (node (ref "J5") (pin "3") (pinfunction "3_3") (pintype "passive"))
      (node (ref "JUSB4") (pin "4") (pinfunction "P$4_4") (pintype "bidirectional"))
      (node (ref "MICROSD") (pin "6") (pinfunction "VSS_6") (pintype "bidirectional"))
      (node (ref "MICROSD") (pin "S1") (pinfunction "SHIELD_S1") (pintype "bidirectional"))
      (node (ref "MICROSD") (pin "S2") (pinfunction "SHIELD_S2") (pintype "bidirectional"))
      (node (ref "MICROSD") (pin "S3") (pinfunction "SHIELD_S3") (pintype "bidirectional"))
      (node (ref "MICROSD") (pin "S4") (pinfunction "SHIELD_S4") (pintype "bidirectional"))
      (node (ref "PCIE") (pin "1") (pinfunction "GND1_1") (pintype "bidirectional"))
      (node (ref "PCIE") (pin "15") (pinfunction "GND4_15") (pintype "bidirectional"))
      (node (ref "PCIE") (pin "21") (pinfunction "GND5_21") (pintype "bidirectional"))
      (node (ref "PCIE") (pin "27") (pinfunction "GND6_27") (pintype "bidirectional"))
      (node (ref "PCIE") (pin "3") (pinfunction "GND2_3") (pintype "bidirectional"))
      (node (ref "PCIE") (pin "33") (pinfunction "GND7_33") (pintype "bidirectional"))
      (node (ref "PCIE") (pin "39") (pinfunction "GND8_39") (pintype "bidirectional"))
      (node (ref "PCIE") (pin "45") (pinfunction "GND9_45") (pintype "bidirectional"))
      (node (ref "PCIE") (pin "51") (pinfunction "GND10_51") (pintype "bidirectional"))
      (node (ref "PCIE") (pin "57") (pinfunction "GND11_57") (pintype "bidirectional"))
      (node (ref "PCIE") (pin "71") (pinfunction "GND12_71") (pintype "bidirectional"))
      (node (ref "PCIE") (pin "73") (pinfunction "GND13_73") (pintype "bidirectional"))
      (node (ref "PCIE") (pin "75") (pinfunction "GND14_75") (pintype "bidirectional"))
      (node (ref "PCIE") (pin "9") (pinfunction "GND3_9") (pintype "bidirectional"))
      (node (ref "PCIE") (pin "S1") (pinfunction "S1_S1") (pintype "bidirectional"))
      (node (ref "PCIE") (pin "S2") (pinfunction "S2_S2") (pintype "bidirectional"))
      (node (ref "PI1") (pin "1") (pinfunction "1_1") (pintype "passive"))
      (node (ref "PI1") (pin "107") (pinfunction "7_107") (pintype "passive"))
      (node (ref "PI1") (pin "108") (pinfunction "8_108") (pintype "passive"))
      (node (ref "PI1") (pin "113") (pinfunction "13_113") (pintype "passive"))
      (node (ref "PI1") (pin "114") (pinfunction "14_114") (pintype "passive"))
      (node (ref "PI1") (pin "119") (pinfunction "19_119") (pintype "passive"))
      (node (ref "PI1") (pin "120") (pinfunction "20_120") (pintype "passive"))
      (node (ref "PI1") (pin "125") (pinfunction "25_125") (pintype "passive"))
      (node (ref "PI1") (pin "126") (pinfunction "26_126") (pintype "passive"))
      (node (ref "PI1") (pin "13") (pinfunction "13_13") (pintype "passive"))
      (node (ref "PI1") (pin "131") (pinfunction "31_131") (pintype "passive"))
      (node (ref "PI1") (pin "132") (pinfunction "32_132") (pintype "passive"))
      (node (ref "PI1") (pin "137") (pinfunction "37_137") (pintype "passive"))
      (node (ref "PI1") (pin "138") (pinfunction "38_138") (pintype "passive"))
      (node (ref "PI1") (pin "14") (pinfunction "14_14") (pintype "passive"))
      (node (ref "PI1") (pin "143") (pinfunction "43_143") (pintype "passive"))
      (node (ref "PI1") (pin "149") (pinfunction "49_149") (pintype "passive"))
      (node (ref "PI1") (pin "155") (pinfunction "55_155") (pintype "passive"))
      (node (ref "PI1") (pin "156") (pinfunction "56_156") (pintype "passive"))
      (node (ref "PI1") (pin "161") (pinfunction "61_161") (pintype "passive"))
      (node (ref "PI1") (pin "162") (pinfunction "62_162") (pintype "passive"))
      (node (ref "PI1") (pin "167") (pinfunction "67_167") (pintype "passive"))
      (node (ref "PI1") (pin "168") (pinfunction "68_168") (pintype "passive"))
      (node (ref "PI1") (pin "173") (pinfunction "73_173") (pintype "passive"))
      (node (ref "PI1") (pin "174") (pinfunction "74_174") (pintype "passive"))
      (node (ref "PI1") (pin "179") (pinfunction "79_179") (pintype "passive"))
      (node (ref "PI1") (pin "180") (pinfunction "80_180") (pintype "passive"))
      (node (ref "PI1") (pin "185") (pinfunction "85_185") (pintype "passive"))
      (node (ref "PI1") (pin "186") (pinfunction "86_186") (pintype "passive"))
      (node (ref "PI1") (pin "191") (pinfunction "91_191") (pintype "passive"))
      (node (ref "PI1") (pin "192") (pinfunction "92_192") (pintype "passive"))
      (node (ref "PI1") (pin "197") (pinfunction "97_197") (pintype "passive"))
      (node (ref "PI1") (pin "198") (pinfunction "98_198") (pintype "passive"))
      (node (ref "PI1") (pin "2") (pinfunction "2_2") (pintype "passive"))
      (node (ref "PI1") (pin "21") (pinfunction "21_21") (pintype "passive"))
      (node (ref "PI1") (pin "24") (pinfunction "24_24") (pintype "passive"))
      (node (ref "PI1") (pin "31") (pinfunction "31_31") (pintype "passive"))
      (node (ref "PI1") (pin "34") (pinfunction "34_34") (pintype "passive"))
      (node (ref "PI1") (pin "41") (pinfunction "41_41") (pintype "passive"))
      (node (ref "PI1") (pin "44") (pinfunction "44_44") (pintype "passive"))
      (node (ref "PI1") (pin "51") (pinfunction "51_51") (pintype "passive"))
      (node (ref "PI1") (pin "54") (pinfunction "54_54") (pintype "passive"))
      (node (ref "PI1") (pin "59") (pinfunction "59_59") (pintype "passive"))
      (node (ref "PI1") (pin "60") (pinfunction "60_60") (pintype "passive"))
      (node (ref "PI1") (pin "65") (pinfunction "65_65") (pintype "passive"))
      (node (ref "PI1") (pin "66") (pinfunction "66_66") (pintype "passive"))
      (node (ref "PI1") (pin "7") (pinfunction "7_7") (pintype "passive"))
      (node (ref "PI1") (pin "72") (pinfunction "72_72") (pintype "passive"))
      (node (ref "PI1") (pin "73") (pinfunction "73_73") (pintype "passive"))
      (node (ref "PI1") (pin "8") (pinfunction "8_8") (pintype "passive"))
      (node (ref "PI1") (pin "97") (pinfunction "97_97") (pintype "passive"))
      (node (ref "R1") (pin "2") (pinfunction "2_2") (pintype "passive"))
      (node (ref "R11") (pin "2") (pinfunction "2_2") (pintype "passive"))
      (node (ref "R13") (pin "2") (pinfunction "2_2") (pintype "passive"))
      (node (ref "R16") (pin "2") (pinfunction "2_2") (pintype "passive"))
      (node (ref "R2") (pin "2") (pinfunction "2_2") (pintype "passive"))
      (node (ref "R22") (pin "2") (pinfunction "2_2") (pintype "passive"))
      (node (ref "R25") (pin "2") (pinfunction "2_2") (pintype "passive"))
      (node (ref "R26") (pin "2") (pinfunction "2_2") (pintype "passive"))
      (node (ref "R27") (pin "2") (pinfunction "2_2") (pintype "passive"))
      (node (ref "R28") (pin "2") (pinfunction "2_2") (pintype "passive"))
      (node (ref "R29") (pin "2") (pinfunction "2_2") (pintype "passive"))
      (node (ref "R33") (pin "2") (pinfunction "2_2") (pintype "passive"))
      (node (ref "R35") (pin "2") (pinfunction "2_2") (pintype "passive"))
      (node (ref "R39") (pin "2") (pinfunction "2_2") (pintype "passive"))
      (node (ref "R43") (pin "2") (pinfunction "2_2") (pintype "passive"))
      (node (ref "R46") (pin "2") (pinfunction "2_2") (pintype "passive"))
      (node (ref "R50") (pin "2") (pinfunction "2_2") (pintype "passive"))
      (node (ref "SJ1") (pin "1") (pinfunction "1_1") (pintype "passive"))
      (node (ref "SJ2") (pin "1") (pinfunction "1_1") (pintype "passive"))
      (node (ref "SJ3") (pin "1") (pinfunction "1_1") (pintype "passive"))
      (node (ref "SJ4") (pin "1") (pinfunction "1_1") (pintype "passive"))
      (node (ref "T2") (pin "2") (pinfunction "S_2") (pintype "passive"))
      (node (ref "T3") (pin "2") (pinfunction "S_2") (pintype "passive"))
      (node (ref "T6") (pin "2") (pinfunction "S_2") (pintype "passive"))
      (node (ref "T7") (pin "2") (pinfunction "S_2") (pintype "passive"))
      (node (ref "T8") (pin "2") (pinfunction "S_2") (pintype "passive"))
      (node (ref "USB2") (pin "4") (pinfunction "GND_4") (pintype "passive"))
      (node (ref "USB2") (pin "8") (pinfunction "GND_8") (pintype "passive"))
      (node (ref "USB2") (pin "S1") (pinfunction "SHIELD_S1") (pintype "passive"))
      (node (ref "USB2") (pin "S2") (pinfunction "SHIELD_S2") (pintype "passive"))
      (node (ref "USB2") (pin "S3") (pinfunction "SHIELD_S3") (pintype "passive"))
      (node (ref "USB2") (pin "S4") (pinfunction "SHIELD_S4") (pintype "passive"))
      (node (ref "USB3") (pin "13") (pinfunction "GND_13") (pintype "passive"))
      (node (ref "USB3") (pin "16") (pinfunction "GND_DRAIN_16") (pintype "passive"))
      (node (ref "USB3") (pin "4") (pinfunction "GND_4") (pintype "passive"))
      (node (ref "USB3") (pin "7") (pinfunction "GND_DRAIN_7") (pintype "passive"))
      (node (ref "USB3") (pin "S1") (pinfunction "SHIELD_S1") (pintype "passive"))
      (node (ref "USB3") (pin "S2") (pinfunction "SHIELD_S2") (pintype "passive"))
      (node (ref "USB3") (pin "S3") (pinfunction "SHIELD_S3") (pintype "passive"))
      (node (ref "USB3") (pin "S4") (pinfunction "SHIELD_S4") (pintype "passive"))
      (node (ref "USBC") (pin "A1") (pinfunction "GND_A1") (pintype "passive"))
      (node (ref "USBC") (pin "A12") (pinfunction "GND1_A12") (pintype "passive"))
      (node (ref "USBC") (pin "B1") (pinfunction "GND3_B1") (pintype "passive"))
      (node (ref "USBC") (pin "B12") (pinfunction "GND2_B12") (pintype "passive"))
      (node (ref "USBC") (pin "S1") (pinfunction "SHIELD_S1") (pintype "passive"))
      (node (ref "USBC") (pin "S2") (pinfunction "SHIELD_S2") (pintype "passive"))
      (node (ref "USBC") (pin "S3") (pinfunction "SHIELD_S3") (pintype "passive"))
      (node (ref "USBC") (pin "S4") (pinfunction "SHIELD_S4") (pintype "passive"))
      (node (ref "X1") (pin "2") (pinfunction "GND_2") (pintype "passive"))
      (node (ref "X1") (pin "4") (pinfunction "GND_4") (pintype "passive"))
      (node (ref "X2") (pin "2") (pinfunction "VSS_2") (pintype "power_in"))
    )
    (net (code "32") (name "GPIO2") (class "Default")
      (node (ref "GPIO") (pin "3") (pinfunction "3_3") (pintype "bidirectional"))
      (node (ref "J2") (pin "12") (pinfunction "12_12") (pintype "bidirectional"))
      (node (ref "PI1") (pin "57") (pinfunction "57_57") (pintype "passive"))
    )
    (net (code "33") (name "GPIO3") (class "Default")
      (node (ref "GPIO") (pin "5") (pinfunction "5_5") (pintype "bidirectional"))
      (node (ref "J4") (pin "12") (pinfunction "12_12") (pintype "bidirectional"))
      (node (ref "PI1") (pin "55") (pinfunction "55_55") (pintype "passive"))
    )
    (net (code "34") (name "GPIO4") (class "Default")
      (node (ref "GPIO") (pin "7") (pinfunction "7_7") (pintype "bidirectional"))
      (node (ref "PI1") (pin "53") (pinfunction "53_53") (pintype "passive"))
    )
    (net (code "35") (name "GPIO5") (class "Default")
      (node (ref "GPIO") (pin "29") (pinfunction "29_29") (pintype "bidirectional"))
      (node (ref "PI1") (pin "33") (pinfunction "33_33") (pintype "passive"))
    )
    (net (code "36") (name "GPIO6") (class "Default")
      (node (ref "GPIO") (pin "31") (pinfunction "31_31") (pintype "bidirectional"))
      (node (ref "PI1") (pin "29") (pinfunction "29_29") (pintype "passive"))
    )
    (net (code "37") (name "GPIO7") (class "Default")
      (node (ref "GPIO") (pin "26") (pinfunction "26_26") (pintype "bidirectional"))
      (node (ref "PI1") (pin "38") (pinfunction "38_38") (pintype "passive"))
    )
    (net (code "38") (name "GPIO8") (class "Default")
      (node (ref "GPIO") (pin "24") (pinfunction "24_24") (pintype "bidirectional"))
      (node (ref "J2") (pin "17") (pinfunction "17_17") (pintype "bidirectional"))
      (node (ref "PI1") (pin "40") (pinfunction "40_40") (pintype "passive"))
    )
    (net (code "39") (name "GPIO9") (class "Default")
      (node (ref "GPIO") (pin "21") (pinfunction "21_21") (pintype "bidirectional"))
      (node (ref "J2") (pin "14") (pinfunction "14_14") (pintype "bidirectional"))
      (node (ref "PI1") (pin "39") (pinfunction "39_39") (pintype "passive"))
    )
    (net (code "40") (name "GPIO10") (class "Default")
      (node (ref "GPIO") (pin "19") (pinfunction "19_19") (pintype "bidirectional"))
      (node (ref "J2") (pin "15") (pinfunction "15_15") (pintype "bidirectional"))
      (node (ref "PI1") (pin "43") (pinfunction "43_43") (pintype "passive"))
    )
    (net (code "41") (name "GPIO11") (class "Default")
      (node (ref "GPIO") (pin "23") (pinfunction "23_23") (pintype "bidirectional"))
      (node (ref "J2") (pin "16") (pinfunction "16_16") (pintype "bidirectional"))
      (node (ref "PI1") (pin "37") (pinfunction "37_37") (pintype "passive"))
    )
    (net (code "42") (name "GPIO12") (class "Default")
      (node (ref "GPIO") (pin "32") (pinfunction "32_32") (pintype "bidirectional"))
      (node (ref "PI1") (pin "32") (pinfunction "32_32") (pintype "passive"))
    )
    (net (code "43") (name "GPIO13") (class "Default")
      (node (ref "GPIO") (pin "33") (pinfunction "33_33") (pintype "bidirectional"))
      (node (ref "PI1") (pin "27") (pinfunction "27_27") (pintype "passive"))
    )
    (net (code "44") (name "GPIO14") (class "Default")
      (node (ref "GPIO") (pin "8") (pinfunction "8_8") (pintype "bidirectional"))
      (node (ref "J2") (pin "9") (pinfunction "9_9") (pintype "bidirectional"))
      (node (ref "J4") (pin "9") (pinfunction "9_9") (pintype "bidirectional"))
      (node (ref "PI1") (pin "56") (pinfunction "56_56") (pintype "passive"))
    )
    (net (code "45") (name "GPIO15") (class "Default")
      (node (ref "GPIO") (pin "10") (pinfunction "10_10") (pintype "bidirectional"))
      (node (ref "J2") (pin "8") (pinfunction "8_8") (pintype "bidirectional"))
      (node (ref "J4") (pin "8") (pinfunction "8_8") (pintype "bidirectional"))
      (node (ref "PI1") (pin "52") (pinfunction "52_52") (pintype "passive"))
    )
    (net (code "46") (name "GPIO16") (class "Default")
      (node (ref "GPIO") (pin "36") (pinfunction "36_36") (pintype "bidirectional"))
      (node (ref "PI1") (pin "30") (pinfunction "30_30") (pintype "passive"))
    )
    (net (code "47") (name "GPIO17") (class "Default")
      (node (ref "GPIO") (pin "11") (pinfunction "11_11") (pintype "bidirectional"))
      (node (ref "PI1") (pin "49") (pinfunction "49_49") (pintype "passive"))
    )
    (net (code "48") (name "GPIO18") (class "Default")
      (node (ref "GPIO") (pin "12") (pinfunction "12_12") (pintype "bidirectional"))
      (node (ref "J4") (pin "17") (pinfunction "17_17") (pintype "bidirectional"))
      (node (ref "PI1") (pin "50") (pinfunction "50_50") (pintype "passive"))
    )
    (net (code "49") (name "GPIO19") (class "Default")
      (node (ref "GPIO") (pin "35") (pinfunction "35_35") (pintype "bidirectional"))
      (node (ref "J4") (pin "14") (pinfunction "14_14") (pintype "bidirectional"))
      (node (ref "PI1") (pin "25") (pinfunction "25_25") (pintype "passive"))
    )
    (net (code "50") (name "GPIO20") (class "Default")
      (node (ref "GPIO") (pin "38") (pinfunction "38_38") (pintype "bidirectional"))
      (node (ref "J4") (pin "15") (pinfunction "15_15") (pintype "bidirectional"))
      (node (ref "PI1") (pin "28") (pinfunction "28_28") (pintype "passive"))
    )
    (net (code "51") (name "GPIO21") (class "Default")
      (node (ref "GPIO") (pin "40") (pinfunction "40_40") (pintype "bidirectional"))
      (node (ref "J4") (pin "16") (pinfunction "16_16") (pintype "bidirectional"))
      (node (ref "PI1") (pin "26") (pinfunction "26_26") (pintype "passive"))
    )
    (net (code "52") (name "GPIO22") (class "Default")
      (node (ref "GPIO") (pin "15") (pinfunction "15_15") (pintype "bidirectional"))
      (node (ref "PI1") (pin "45") (pinfunction "45_45") (pintype "passive"))
    )
    (net (code "53") (name "GPIO23") (class "Default")
      (node (ref "GPIO") (pin "16") (pinfunction "16_16") (pintype "bidirectional"))
      (node (ref "PI1") (pin "48") (pinfunction "48_48") (pintype "passive"))
    )
    (net (code "54") (name "GPIO24") (class "Default")
      (node (ref "GPIO") (pin "18") (pinfunction "18_18") (pintype "bidirectional"))
      (node (ref "J2") (pin "11") (pinfunction "11_11") (pintype "bidirectional"))
      (node (ref "J4") (pin "11") (pinfunction "11_11") (pintype "bidirectional"))
      (node (ref "PI1") (pin "46") (pinfunction "46_46") (pintype "passive"))
    )
    (net (code "55") (name "GPIO25") (class "Default")
      (node (ref "GPIO") (pin "22") (pinfunction "22_22") (pintype "bidirectional"))
      (node (ref "J2") (pin "10") (pinfunction "10_10") (pintype "bidirectional"))
      (node (ref "J4") (pin "10") (pinfunction "10_10") (pintype "bidirectional"))
      (node (ref "PI1") (pin "42") (pinfunction "42_42") (pintype "passive"))
    )
    (net (code "56") (name "GPIO26") (class "Default")
      (node (ref "GPIO") (pin "37") (pinfunction "37_37") (pintype "bidirectional"))
      (node (ref "PI1") (pin "23") (pinfunction "23_23") (pintype "passive"))
    )
    (net (code "57") (name "GPIO27") (class "Default")
      (node (ref "GPIO") (pin "13") (pinfunction "13_13") (pintype "bidirectional"))
      (node (ref "PI1") (pin "47") (pinfunction "47_47") (pintype "passive"))
    )
    (net (code "58") (name "GPIO_VREF") (class "Default")
      (node (ref "PI1") (pin "77") (pinfunction "77_77") (pintype "passive"))
      (node (ref "R3") (pin "1") (pinfunction "1_1") (pintype "passive"))
      (node (ref "R4") (pin "1") (pinfunction "1_1") (pintype "passive"))
      (node (ref "R6") (pin "2") (pinfunction "2_2") (pintype "passive"))
      (node (ref "R7") (pin "2") (pinfunction "2_2") (pintype "passive"))
      (node (ref "TP-GREF") (pin "TP") (pinfunction "P$1_TP") (pintype "bidirectional"))
    )
    (net (code "59") (name "HDMI0_CEC") (class "Default")
      (node (ref "HDMI2") (pin "13") (pinfunction "GROUND_13") (pintype "passive"))
      (node (ref "PI1") (pin "152") (pinfunction "52_152") (pintype "passive"))
    )
    (net (code "60") (name "HDMI0_HOTPLUG") (class "Default")
      (node (ref "HDMI2") (pin "19") (pinfunction "HOTPLUG/HEC+_19") (pintype "passive"))
      (node (ref "PI1") (pin "154") (pinfunction "54_154") (pintype "passive"))
    )
    (net (code "61") (name "HDMI0_SCL") (class "Default")
      (node (ref "HDMI2") (pin "15") (pinfunction "SCL_15") (pintype "passive"))
      (node (ref "PI1") (pin "199") (pinfunction "99_199") (pintype "passive"))
    )
    (net (code "62") (name "HDMI0_SDA") (class "Default")
      (node (ref "HDMI2") (pin "16") (pinfunction "SDA_16") (pintype "passive"))
      (node (ref "PI1") (pin "200") (pinfunction "100_200") (pintype "passive"))
    )
    (net (code "63") (name "HDMI0_TDMS0_N") (class "Default")
      (node (ref "D4") (pin "4") (pinfunction "D2+_4") (pintype "bidirectional"))
      (node (ref "D4") (pin "7") (pinfunction "D2+_7") (pintype "bidirectional"))
      (node (ref "HDMI2") (pin "9") (pinfunction "TMDS0-_9") (pintype "passive"))
      (node (ref "PI1") (pin "183") (pinfunction "83_183") (pintype "passive"))
    )
    (net (code "64") (name "HDMI0_TDMS0_P") (class "Default")
      (node (ref "D4") (pin "5") (pinfunction "D2-_5") (pintype "bidirectional"))
      (node (ref "D4") (pin "6") (pinfunction "D2-_6") (pintype "bidirectional"))
      (node (ref "HDMI2") (pin "7") (pinfunction "TMDS0SHIELD_7") (pintype "passive"))
      (node (ref "PI1") (pin "181") (pinfunction "81_181") (pintype "passive"))
    )
    (net (code "65") (name "HDMI0_TDMS1_N") (class "Default")
      (node (ref "D3") (pin "1") (pinfunction "D1+_1") (pintype "bidirectional"))
      (node (ref "D3") (pin "10") (pinfunction "D1+_10") (pintype "bidirectional"))
      (node (ref "HDMI2") (pin "6") (pinfunction "TMDS1-_6") (pintype "passive"))
      (node (ref "PI1") (pin "177") (pinfunction "77_177") (pintype "passive"))
    )
    (net (code "66") (name "HDMI0_TDMS1_P") (class "Default")
      (node (ref "D3") (pin "2") (pinfunction "D1-_2") (pintype "bidirectional"))
      (node (ref "D3") (pin "9") (pinfunction "D1-_9") (pintype "bidirectional"))
      (node (ref "HDMI2") (pin "4") (pinfunction "TMDS1SHIELD_4") (pintype "passive"))
      (node (ref "PI1") (pin "175") (pinfunction "75_175") (pintype "passive"))
    )
    (net (code "67") (name "HDMI0_TDMS2_N") (class "Default")
      (node (ref "D3") (pin "4") (pinfunction "D2+_4") (pintype "bidirectional"))
      (node (ref "D3") (pin "7") (pinfunction "D2+_7") (pintype "bidirectional"))
      (node (ref "HDMI2") (pin "3") (pinfunction "TMDS2-_3") (pintype "passive"))
      (node (ref "PI1") (pin "171") (pinfunction "71_171") (pintype "passive"))
    )
    (net (code "68") (name "HDMI0_TDMS2_P") (class "Default")
      (node (ref "D3") (pin "5") (pinfunction "D2-_5") (pintype "bidirectional"))
      (node (ref "D3") (pin "6") (pinfunction "D2-_6") (pintype "bidirectional"))
      (node (ref "HDMI2") (pin "1") (pinfunction "TMDS2SHIELD_1") (pintype "passive"))
      (node (ref "PI1") (pin "169") (pinfunction "69_169") (pintype "passive"))
    )
    (net (code "69") (name "HDMI0_TDMSCK_N") (class "Default")
      (node (ref "D4") (pin "1") (pinfunction "D1+_1") (pintype "bidirectional"))
      (node (ref "D4") (pin "10") (pinfunction "D1+_10") (pintype "bidirectional"))
      (node (ref "HDMI2") (pin "12") (pinfunction "TMDSCLOCK-_12") (pintype "passive"))
      (node (ref "PI1") (pin "189") (pinfunction "89_189") (pintype "passive"))
    )
    (net (code "70") (name "HDMI0_TDMSCK_P") (class "Default")
      (node (ref "D4") (pin "2") (pinfunction "D1-_2") (pintype "bidirectional"))
      (node (ref "D4") (pin "9") (pinfunction "D1-_9") (pintype "bidirectional"))
      (node (ref "HDMI2") (pin "10") (pinfunction "TMDSCLOCKSHIELD_10") (pintype "passive"))
      (node (ref "PI1") (pin "187") (pinfunction "87_187") (pintype "passive"))
    )
    (net (code "71") (name "HDMI_5V") (class "Default")
      (node (ref "C4") (pin "1") (pinfunction "1_1") (pintype "passive"))
      (node (ref "HDMI2") (pin "18") (pinfunction "POWER_18") (pintype "power_in"))
      (node (ref "IC4") (pin "2") (pinfunction "OUT_2") (pintype "power_in"))
      (node (ref "TP-5VHD") (pin "TP") (pinfunction "P$1_TP") (pintype "bidirectional"))
    )
    (net (code "72") (name "HUB1_DP_N") (class "Default")
      (node (ref "D14") (pin "5") (pinfunction "D2-_5") (pintype "bidirectional"))
      (node (ref "D14") (pin "6") (pinfunction "D2-_6") (pintype "bidirectional"))
      (node (ref "IC6") (pin "11") (pinfunction "DM1_11") (pintype "bidirectional"))
      (node (ref "USB3") (pin "11") (pinfunction "D-_11") (pintype "passive"))
    )
    (net (code "73") (name "HUB1_DP_P") (class "Default")
      (node (ref "D14") (pin "4") (pinfunction "D2+_4") (pintype "bidirectional"))
      (node (ref "D14") (pin "7") (pinfunction "D2+_7") (pintype "bidirectional"))
      (node (ref "IC6") (pin "12") (pinfunction "DP1_12") (pintype "bidirectional"))
      (node (ref "USB3") (pin "12") (pinfunction "D+_12") (pintype "passive"))
    )
    (net (code "74") (name "HUB2_DP_N") (class "Default")
      (node (ref "D13") (pin "4") (pinfunction "D2+_4") (pintype "bidirectional"))
      (node (ref "D13") (pin "7") (pinfunction "D2+_7") (pintype "bidirectional"))
      (node (ref "IC6") (pin "9") (pinfunction "DM2_9") (pintype "bidirectional"))
      (node (ref "USB2") (pin "2") (pinfunction "D-_2") (pintype "passive"))
    )
    (net (code "75") (name "HUB2_DP_P") (class "Default")
      (node (ref "D13") (pin "5") (pinfunction "D2-_5") (pintype "bidirectional"))
      (node (ref "D13") (pin "6") (pinfunction "D2-_6") (pintype "bidirectional"))
      (node (ref "IC6") (pin "10") (pinfunction "DP2_10") (pintype "bidirectional"))
      (node (ref "USB2") (pin "3") (pinfunction "D+_3") (pintype "passive"))
    )
    (net (code "76") (name "HUB3_DP_N") (class "Default")
      (node (ref "D13") (pin "1") (pinfunction "D1+_1") (pintype "bidirectional"))
      (node (ref "D13") (pin "10") (pinfunction "D1+_10") (pintype "bidirectional"))
      (node (ref "IC6") (pin "7") (pinfunction "DM3_7") (pintype "bidirectional"))
      (node (ref "USB2") (pin "6") (pinfunction "D-_6") (pintype "passive"))
    )
    (net (code "77") (name "HUB3_DP_P") (class "Default")
      (node (ref "D13") (pin "2") (pinfunction "D1-_2") (pintype "bidirectional"))
      (node (ref "D13") (pin "9") (pinfunction "D1-_9") (pintype "bidirectional"))
      (node (ref "IC6") (pin "8") (pinfunction "DP3_8") (pintype "bidirectional"))
      (node (ref "USB2") (pin "7") (pinfunction "D+_7") (pintype "passive"))
    )
    (net (code "78") (name "HUB4_DP_N") (class "Default")
      (node (ref "IC6") (pin "5") (pinfunction "DM4_5") (pintype "bidirectional"))
      (node (ref "JUSB4") (pin "2") (pinfunction "P$2_2") (pintype "bidirectional"))
    )
    (net (code "79") (name "HUB4_DP_P") (class "Default")
      (node (ref "IC6") (pin "6") (pinfunction "DP4_6") (pintype "bidirectional"))
      (node (ref "JUSB4") (pin "3") (pinfunction "P$3_3") (pintype "bidirectional"))
    )
    (net (code "80") (name "HUB_USB_5V") (class "Default")
      (node (ref "C33") (pin "1") (pinfunction "1_1") (pintype "passive"))
      (node (ref "C34") (pin "1") (pinfunction "1_1") (pintype "passive"))
      (node (ref "C35") (pin "1") (pinfunction "1_1") (pintype "passive"))
      (node (ref "IC7") (pin "6") (pinfunction "OUT_6") (pintype "bidirectional"))
      (node (ref "JUSB4") (pin "1") (pinfunction "P$1_1") (pintype "bidirectional"))
      (node (ref "TP-HUB") (pin "TP") (pinfunction "P$1_TP") (pintype "bidirectional"))
      (node (ref "USB2") (pin "1") (pinfunction "VBUS_1") (pintype "passive"))
      (node (ref "USB2") (pin "5") (pinfunction "VBUS_5") (pintype "passive"))
    )
    (net (code "81") (name "HUB_XI") (class "Default")
      (node (ref "C26") (pin "1") (pinfunction "1_1") (pintype "passive"))
      (node (ref "IC6") (pin "4") (pinfunction "XI_4") (pintype "input"))
      (node (ref "X1") (pin "1") (pinfunction "1_1") (pintype "passive"))
    )
    (net (code "82") (name "HUB_XO") (class "Default")
      (node (ref "C27") (pin "1") (pinfunction "1_1") (pintype "passive"))
      (node (ref "IC6") (pin "3") (pinfunction "XO_3") (pintype "output"))
      (node (ref "X1") (pin "3") (pinfunction "2_3") (pintype "passive"))
    )
    (net (code "83") (name "ID_SC") (class "Default")
      (node (ref "GPIO") (pin "28") (pinfunction "28_28") (pintype "bidirectional"))
      (node (ref "ID") (pin "1") (pinfunction "1_1") (pintype "bidirectional"))
      (node (ref "PI1") (pin "36") (pinfunction "36_36") (pintype "passive"))
    )
    (net (code "84") (name "ID_SD") (class "Default")
      (node (ref "GPIO") (pin "27") (pinfunction "27_27") (pintype "bidirectional"))
      (node (ref "ID") (pin "3") (pinfunction "3_3") (pintype "bidirectional"))
      (node (ref "PI1") (pin "35") (pinfunction "35_35") (pintype "passive"))
    )
    (net (code "85") (name "LED_NACT") (class "Default")
      (node (ref "LED3") (pin "C") (pinfunction "C_C") (pintype "passive"))
      (node (ref "PI1") (pin "22") (pinfunction "22_22") (pintype "passive"))
    )
    (net (code "86") (name "M2_3V3") (class "Default")
      (node (ref "C12") (pin "1") (pinfunction "1_1") (pintype "passive"))
      (node (ref "C13") (pin "1") (pinfunction "1_1") (pintype "passive"))
      (node (ref "C14") (pin "1") (pinfunction "1_1") (pintype "passive"))
      (node (ref "C15") (pin "1") (pinfunction "1_1") (pintype "passive"))
      (node (ref "C16") (pin "1") (pinfunction "1_1") (pintype "passive"))
      (node (ref "C17") (pin "1") (pinfunction "1_1") (pintype "passive"))
      (node (ref "L1") (pin "2") (pinfunction "2_2") (pintype "passive"))
      (node (ref "PCIE") (pin "12") (pinfunction "VCC3_12") (pintype "bidirectional"))
      (node (ref "PCIE") (pin "14") (pinfunction "VCC4_14") (pintype "bidirectional"))
      (node (ref "PCIE") (pin "16") (pinfunction "VCC5_16") (pintype "bidirectional"))
      (node (ref "PCIE") (pin "18") (pinfunction "VCC6_18") (pintype "bidirectional"))
      (node (ref "PCIE") (pin "2") (pinfunction "VCC1_2") (pintype "bidirectional"))
      (node (ref "PCIE") (pin "4") (pinfunction "VCC2_4") (pintype "bidirectional"))
      (node (ref "PCIE") (pin "70") (pinfunction "VCC7_70") (pintype "bidirectional"))
      (node (ref "PCIE") (pin "72") (pinfunction "VCC8_72") (pintype "bidirectional"))
      (node (ref "PCIE") (pin "74") (pinfunction "VCC9_74") (pintype "bidirectional"))
      (node (ref "R12") (pin "1") (pinfunction "1_1") (pintype "passive"))
      (node (ref "TP-VM2") (pin "TP") (pinfunction "P$1_TP") (pintype "bidirectional"))
      (node (ref "X2") (pin "3") (pinfunction "OUT_3") (pintype "output"))
      (node (ref "X2") (pin "4") (pinfunction "VDD_4") (pintype "power_in"))
    )
    (net (code "87") (name "NPWR_LED") (class "Default")
      (node (ref "PI1") (pin "96") (pinfunction "96_96") (pintype "passive"))
      (node (ref "R37") (pin "1") (pinfunction "1_1") (pintype "passive"))
      (node (ref "T8") (pin "1") (pinfunction "G_1") (pintype "passive"))
      (node (ref "TP-LED") (pin "TP") (pinfunction "P$1_TP") (pintype "bidirectional"))
    )
    (net (code "88") (name "NRPIBOOT") (class "Default")
      (node (ref "PI1") (pin "94") (pinfunction "94_94") (pintype "passive"))
      (node (ref "T7") (pin "3") (pinfunction "D_3") (pintype "passive"))
    )
    (net (code "89") (name "Net-(3VFB-P$1)") (class "Default")
      (node (ref "3VFB") (pin "TP") (pinfunction "P$1_TP") (pintype "bidirectional"))
      (node (ref "C45") (pin "2") (pinfunction "2_2") (pintype "passive"))
      (node (ref "R48") (pin "2") (pinfunction "2_2") (pintype "passive"))
      (node (ref "R49") (pin "2") (pinfunction "2_2") (pintype "passive"))
      (node (ref "R50") (pin "1") (pinfunction "1_1") (pintype "passive"))
    )
    (net (code "90") (name "Net-(5VFB-P$1)") (class "Default")
      (node (ref "5VFB") (pin "TP") (pinfunction "P$1_TP") (pintype "bidirectional"))
      (node (ref "C38") (pin "2") (pinfunction "2_2") (pintype "passive"))
      (node (ref "R41") (pin "2") (pinfunction "2_2") (pintype "passive"))
      (node (ref "R42") (pin "2") (pinfunction "2_2") (pintype "passive"))
      (node (ref "R43") (pin "1") (pinfunction "1_1") (pintype "passive"))
    )
    (net (code "91") (name "Net-(C11-Pad1)") (class "Default")
      (node (ref "C11") (pin "1") (pinfunction "1_1") (pintype "passive"))
      (node (ref "ETH1") (pin "CT1") (pinfunction "CT1_CT1") (pintype "bidirectional"))
      (node (ref "ETH1") (pin "CT2") (pinfunction "CT2_CT2") (pintype "bidirectional"))
      (node (ref "ETH1") (pin "CT3") (pinfunction "CT3_CT3") (pintype "bidirectional"))
      (node (ref "ETH1") (pin "CT4") (pinfunction "CT4_CT4") (pintype "bidirectional"))
    )
    (net (code "92") (name "Net-(C37-Pad1)") (class "Default")
      (node (ref "C37") (pin "1") (pinfunction "1_1") (pintype "passive"))
      (node (ref "R40") (pin "1") (pinfunction "1_1") (pintype "passive"))
    )
    (net (code "93") (name "Net-(C44-Pad1)") (class "Default")
      (node (ref "C44") (pin "1") (pinfunction "1_1") (pintype "passive"))
      (node (ref "R47") (pin "1") (pinfunction "1_1") (pintype "passive"))
    )
    (net (code "94") (name "Net-(D24-PadA)") (class "Default")
      (node (ref "D24") (pin "A") (pinfunction "A_A") (pintype "passive"))
      (node (ref "J5") (pin "1") (pinfunction "1_1") (pintype "passive"))
    )
    (net (code "95") (name "Net-(ETH1-P17)") (class "Default")
      (node (ref "ETH1") (pin "17") (pinfunction "P17_17") (pintype "bidirectional"))
      (node (ref "R9") (pin "1") (pinfunction "1_1") (pintype "passive"))
    )
    (net (code "96") (name "Net-(ETH1-P19)") (class "Default")
      (node (ref "ETH1") (pin "19") (pinfunction "P19_19") (pintype "bidirectional"))
      (node (ref "R8") (pin "2") (pinfunction "2_2") (pintype "passive"))
    )
    (net (code "97") (name "Net-(IC2-ILIM)") (class "Default")
      (node (ref "IC2") (pin "5") (pinfunction "ILIM_5") (pintype "bidirectional"))
      (node (ref "R2") (pin "1") (pinfunction "1_1") (pintype "passive"))
    )
    (net (code "98") (name "Net-(IC3-AAM)") (class "Default")
      (node (ref "IC3") (pin "1") (pinfunction "AAM_1") (pintype "bidirectional"))
      (node (ref "R39") (pin "1") (pinfunction "1_1") (pintype "passive"))
      (node (ref "R44") (pin "2") (pinfunction "2_2") (pintype "passive"))
    )
    (net (code "99") (name "Net-(IC3-BST)") (class "Default")
      (node (ref "IC3") (pin "5") (pinfunction "BST_5") (pintype "bidirectional"))
      (node (ref "R40") (pin "2") (pinfunction "2_2") (pintype "passive"))
    )
    (net (code "100") (name "Net-(IC3-EN)") (class "Default")
      (node (ref "IC3") (pin "6") (pinfunction "EN_6") (pintype "bidirectional"))
      (node (ref "R38") (pin "2") (pinfunction "2_2") (pintype "passive"))
    )
    (net (code "101") (name "Net-(IC3-FB)") (class "Default")
      (node (ref "IC3") (pin "8") (pinfunction "FB_8") (pintype "bidirectional"))
      (node (ref "R41") (pin "1") (pinfunction "1_1") (pintype "passive"))
    )
    (net (code "102") (name "Net-(IC3-SW)") (class "Default")
      (node (ref "C37") (pin "2") (pinfunction "2_2") (pintype "passive"))
      (node (ref "IC3") (pin "3") (pinfunction "SW_3") (pintype "bidirectional"))
      (node (ref "L2") (pin "1") (pinfunction "1_1") (pintype "passive"))
      (node (ref "SW") (pin "TP") (pinfunction "P$1_TP") (pintype "bidirectional"))
    )
    (net (code "103") (name "Net-(IC3-VCC)") (class "Default")
      (node (ref "C36") (pin "1") (pinfunction "1_1") (pintype "passive"))
      (node (ref "IC3") (pin "7") (pinfunction "VCC_7") (pintype "bidirectional"))
      (node (ref "R44") (pin "1") (pinfunction "1_1") (pintype "passive"))
    )
    (net (code "104") (name "Net-(IC5-FB)") (class "Default")
      (node (ref "C13") (pin "2") (pinfunction "2_2") (pintype "passive"))
      (node (ref "IC5") (pin "1") (pinfunction "FB_1") (pintype "bidirectional"))
      (node (ref "R12") (pin "2") (pinfunction "2_2") (pintype "passive"))
      (node (ref "R13") (pin "1") (pinfunction "1_1") (pintype "passive"))
      (node (ref "TP-M2FB") (pin "TP") (pinfunction "P$1_TP") (pintype "bidirectional"))
    )
    (net (code "105") (name "Net-(IC5-LX)") (class "Default")
      (node (ref "IC5") (pin "6") (pinfunction "LX_6") (pintype "power_in"))
      (node (ref "L1") (pin "1") (pinfunction "1_1") (pintype "passive"))
      (node (ref "TP-LX") (pin "TP") (pinfunction "P$1_TP") (pintype "bidirectional"))
    )
    (net (code "106") (name "Net-(IC6-DMU)") (class "Default")
      (node (ref "IC6") (pin "14") (pinfunction "DMU_14") (pintype "bidirectional"))
      (node (ref "R31") (pin "2") (pinfunction "2_2") (pintype "passive"))
    )
    (net (code "107") (name "Net-(IC6-DPU)") (class "Default")
      (node (ref "IC6") (pin "15") (pinfunction "DPU_15") (pintype "bidirectional"))
      (node (ref "R30") (pin "2") (pinfunction "2_2") (pintype "passive"))
    )
    (net (code "108") (name "Net-(IC6-LED3{slash}SCL)") (class "Default")
      (node (ref "IC6") (pin "13") (pinfunction "LED3/SCL_13") (pintype "bidirectional"))
      (node (ref "R29") (pin "1") (pinfunction "1_1") (pintype "passive"))
    )
    (net (code "109") (name "Net-(IC6-PSELF)") (class "Default")
      (node (ref "IC6") (pin "18") (pinfunction "PSELF_18") (pintype "output"))
      (node (ref "R32") (pin "2") (pinfunction "2_2") (pintype "passive"))
    )
    (net (code "110") (name "Net-(IC6-~{RESET}{slash}CDP)") (class "Default")
      (node (ref "C21") (pin "1") (pinfunction "1_1") (pintype "passive"))
      (node (ref "IC6") (pin "16") (pinfunction "~{RESET}/CDP_16") (pintype "output"))
    )
    (net (code "111") (name "Net-(IC7-ILIM)") (class "Default")
      (node (ref "IC7") (pin "5") (pinfunction "ILIM_5") (pintype "bidirectional"))
      (node (ref "R33") (pin "1") (pinfunction "1_1") (pintype "passive"))
    )
    (net (code "112") (name "Net-(IC8-AAM)") (class "Default")
      (node (ref "IC8") (pin "1") (pinfunction "AAM_1") (pintype "bidirectional"))
      (node (ref "R46") (pin "1") (pinfunction "1_1") (pintype "passive"))
      (node (ref "R51") (pin "2") (pinfunction "2_2") (pintype "passive"))
    )
    (net (code "113") (name "Net-(IC8-BST)") (class "Default")
      (node (ref "IC8") (pin "5") (pinfunction "BST_5") (pintype "bidirectional"))
      (node (ref "R47") (pin "2") (pinfunction "2_2") (pintype "passive"))
    )
    (net (code "114") (name "Net-(IC8-EN)") (class "Default")
      (node (ref "IC8") (pin "6") (pinfunction "EN_6") (pintype "bidirectional"))
      (node (ref "R45") (pin "2") (pinfunction "2_2") (pintype "passive"))
    )
    (net (code "115") (name "Net-(IC8-FB)") (class "Default")
      (node (ref "IC8") (pin "8") (pinfunction "FB_8") (pintype "bidirectional"))
      (node (ref "R48") (pin "1") (pinfunction "1_1") (pintype "passive"))
    )
    (net (code "116") (name "Net-(IC8-SW)") (class "Default")
      (node (ref "C44") (pin "2") (pinfunction "2_2") (pintype "passive"))
      (node (ref "IC8") (pin "3") (pinfunction "SW_3") (pintype "bidirectional"))
      (node (ref "L3") (pin "1") (pinfunction "1_1") (pintype "passive"))
      (node (ref "SW3") (pin "TP") (pinfunction "P$1_TP") (pintype "bidirectional"))
    )
    (net (code "117") (name "Net-(IC8-VCC)") (class "Default")
      (node (ref "C43") (pin "1") (pinfunction "1_1") (pintype "passive"))
      (node (ref "IC8") (pin "7") (pinfunction "VCC_7") (pintype "bidirectional"))
      (node (ref "R51") (pin "1") (pinfunction "1_1") (pintype "passive"))
    )
    (net (code "118") (name "Net-(LED1-PadA)") (class "Default")
      (node (ref "LED1") (pin "A") (pinfunction "A_A") (pintype "passive"))
      (node (ref "R5") (pin "2") (pinfunction "2_2") (pintype "passive"))
    )
    (net (code "119") (name "Net-(LED2-PadC)") (class "Default")
      (node (ref "LED2") (pin "C") (pinfunction "C_C") (pintype "passive"))
      (node (ref "R10") (pin "1") (pinfunction "1_1") (pintype "passive"))
    )
    (net (code "120") (name "Net-(LED3-PadA)") (class "Default")
      (node (ref "LED3") (pin "A") (pinfunction "A_A") (pintype "passive"))
      (node (ref "R36") (pin "2") (pinfunction "2_2") (pintype "passive"))
    )
    (net (code "121") (name "Net-(PCIE-DA5{slash}~{DSS}{slash}~{LED1})") (class "Default")
      (node (ref "PCIE") (pin "10") (pinfunction "DA5/~{DSS}/~{LED1}_10") (pintype "bidirectional"))
      (node (ref "R10") (pin "2") (pinfunction "2_2") (pintype "passive"))
    )
    (net (code "122") (name "Net-(PCIE-SUSCLK)") (class "Default")
      (node (ref "PCIE") (pin "68") (pinfunction "SUSCLK_68") (pintype "bidirectional"))
      (node (ref "TP-M2CLK") (pin "TP") (pinfunction "P$1_TP") (pintype "bidirectional"))
      (node (ref "X2") (pin "1") (pinfunction "CON_1") (pintype "input"))
    )
    (net (code "123") (name "Net-(PCIE-~{PEWAKE})") (class "Default")
      (node (ref "PCIE") (pin "54") (pinfunction "~{PEWAKE}_54") (pintype "bidirectional"))
      (node (ref "R14") (pin "2") (pinfunction "2_2") (pintype "passive"))
      (node (ref "R15") (pin "1") (pinfunction "1_1") (pintype "passive"))
    )
    (net (code "124") (name "Net-(Q1-B)") (class "Default")
      (node (ref "Q1") (pin "1") (pinfunction "B_1") (pintype "passive"))
      (node (ref "Q1") (pin "3") (pinfunction "C_3") (pintype "passive"))
      (node (ref "Q2") (pin "1") (pinfunction "B_1") (pintype "passive"))
      (node (ref "R27") (pin "1") (pinfunction "1_1") (pintype "passive"))
    )
    (net (code "125") (name "Net-(Q2-C)") (class "Default")
      (node (ref "Q2") (pin "3") (pinfunction "C_3") (pintype "passive"))
      (node (ref "R28") (pin "1") (pinfunction "1_1") (pintype "passive"))
      (node (ref "T5") (pin "4") (pinfunction "G_4") (pintype "passive"))
    )
    (net (code "126") (name "Net-(R34-Pad2)") (class "Default")
      (node (ref "R34") (pin "2") (pinfunction "2_2") (pintype "passive"))
      (node (ref "SW1") (pin "1") (pinfunction "1_1") (pintype "passive"))
      (node (ref "SW1") (pin "3") (pinfunction "3_3") (pintype "passive"))
    )
    (net (code "127") (name "Net-(T2-G)") (class "Default")
      (node (ref "R17") (pin "2") (pinfunction "2_2") (pintype "passive"))
      (node (ref "T2") (pin "1") (pinfunction "G_1") (pintype "passive"))
      (node (ref "T3") (pin "3") (pinfunction "D_3") (pintype "passive"))
    )
    (net (code "128") (name "Net-(T6-G)") (class "Default")
      (node (ref "R35") (pin "1") (pinfunction "1_1") (pintype "passive"))
      (node (ref "SW1") (pin "2") (pinfunction "2_2") (pintype "passive"))
      (node (ref "SW1") (pin "4") (pinfunction "4_4") (pintype "passive"))
      (node (ref "T6") (pin "1") (pinfunction "G_1") (pintype "passive"))
      (node (ref "T7") (pin "1") (pinfunction "G_1") (pintype "passive"))
    )
    (net (code "129") (name "Net-(T8-D)") (class "Default")
      (node (ref "LED1") (pin "C") (pinfunction "C_C") (pintype "passive"))
      (node (ref "R37") (pin "2") (pinfunction "2_2") (pintype "passive"))
      (node (ref "T8") (pin "3") (pinfunction "D_3") (pintype "passive"))
    )
    (net (code "130") (name "PCIE_CLKREQ") (class "Default")
      (node (ref "PCIE") (pin "52") (pinfunction "~{CLKREQ}_52") (pintype "bidirectional"))
      (node (ref "R19") (pin "2") (pinfunction "2_2") (pintype "passive"))
      (node (ref "T4") (pin "3") (pinfunction "D_3") (pintype "passive"))
    )
    (net (code "131") (name "PCIE_CLK_N") (class "Default")
      (node (ref "PCIE") (pin "53") (pinfunction "REFCLK_N_53") (pintype "bidirectional"))
      (node (ref "PI1") (pin "111") (pinfunction "11_111") (pintype "passive"))
    )
    (net (code "132") (name "PCIE_CLK_P") (class "Default")
      (node (ref "PCIE") (pin "55") (pinfunction "REFCLK_P_55") (pintype "bidirectional"))
      (node (ref "PI1") (pin "109") (pinfunction "9_109") (pintype "passive"))
    )
    (net (code "133") (name "PCIE_DET_WAKE") (class "Default")
      (node (ref "R15") (pin "2") (pinfunction "2_2") (pintype "passive"))
      (node (ref "R18") (pin "2") (pinfunction "2_2") (pintype "passive"))
      (node (ref "T3") (pin "1") (pinfunction "G_1") (pintype "passive"))
    )
    (net (code "134") (name "PCIE_EN") (class "Default")
      (node (ref "R20") (pin "2") (pinfunction "2_2") (pintype "passive"))
      (node (ref "R21") (pin "1") (pinfunction "1_1") (pintype "passive"))
    )
    (net (code "135") (name "PCIE_NCLKREQ") (class "Default")
      (node (ref "PI1") (pin "101") (pinfunction "1_101") (pintype "passive"))
      (node (ref "T4") (pin "2") (pinfunction "S_2") (pintype "passive"))
    )
    (net (code "136") (name "PCIE_NRST") (class "Default")
      (node (ref "PI1") (pin "110") (pinfunction "10_110") (pintype "passive"))
      (node (ref "T1") (pin "3") (pinfunction "D_3") (pintype "passive"))
    )
    (net (code "137") (name "PCIE_NWAKE") (class "Default")
      (node (ref "PI1") (pin "103") (pinfunction "3_103") (pintype "passive"))
      (node (ref "R21") (pin "2") (pinfunction "2_2") (pintype "passive"))
      (node (ref "R22") (pin "1") (pinfunction "1_1") (pintype "passive"))
      (node (ref "T2") (pin "3") (pinfunction "D_3") (pintype "passive"))
    )
    (net (code "138") (name "PCIE_PWR_EN") (class "Default")
      (node (ref "IC5") (pin "7") (pinfunction "EN_7") (pintype "bidirectional"))
      (node (ref "PI1") (pin "105") (pinfunction "5_105") (pintype "passive"))
      (node (ref "R11") (pin "1") (pinfunction "1_1") (pintype "passive"))
    )
    (net (code "139") (name "PCIE_RST") (class "Default")
      (node (ref "PCIE") (pin "50") (pinfunction "~{PERST}_50") (pintype "bidirectional"))
      (node (ref "R16") (pin "1") (pinfunction "1_1") (pintype "passive"))
      (node (ref "T1") (pin "2") (pinfunction "S_2") (pintype "passive"))
    )
    (net (code "140") (name "PCIE_RX_N") (class "Default")
      (node (ref "PCIE") (pin "41") (pinfunction "PET_N0_41") (pintype "bidirectional"))
      (node (ref "PI1") (pin "117") (pinfunction "17_117") (pintype "passive"))
    )
    (net (code "141") (name "PCIE_RX_P") (class "Default")
      (node (ref "PCIE") (pin "43") (pinfunction "PET_P0_43") (pintype "bidirectional"))
      (node (ref "PI1") (pin "115") (pinfunction "15_115") (pintype "passive"))
    )
    (net (code "142") (name "PCIE_TX_N") (class "Default")
      (node (ref "PCIE") (pin "47") (pinfunction "PER_N0_47") (pintype "bidirectional"))
      (node (ref "PI1") (pin "123") (pinfunction "23_123") (pintype "passive"))
    )
    (net (code "143") (name "PCIE_TX_P") (class "Default")
      (node (ref "PCIE") (pin "49") (pinfunction "PER_P0_49") (pintype "bidirectional"))
      (node (ref "PI1") (pin "121") (pinfunction "21_121") (pintype "passive"))
    )
    (net (code "144") (name "PMIC_ENABLE") (class "Default")
      (node (ref "PI1") (pin "100") (pinfunction "100_100") (pintype "passive"))
      (node (ref "SJ4") (pin "2") (pinfunction "2_2") (pintype "passive"))
    )
    (net (code "145") (name "PWM") (class "Default")
      (node (ref "PI1") (pin "20") (pinfunction "20_20") (pintype "passive"))
    )
    (net (code "146") (name "PWR_BUT") (class "Default")
      (node (ref "PI1") (pin "91") (pinfunction "91_91") (pintype "passive"))
      (node (ref "T6") (pin "3") (pinfunction "D_3") (pintype "passive"))
    )
    (net (code "147") (name "SCL0") (class "Default")
      (node (ref "PI1") (pin "79") (pinfunction "79_79") (pintype "passive"))
    )
    (net (code "148") (name "SCL1") (class "Default")
      (node (ref "D9") (pin "1") (pinfunction "D1+_1") (pintype "bidirectional"))
      (node (ref "D9") (pin "10") (pinfunction "D1+_10") (pintype "bidirectional"))
      (node (ref "DISP0") (pin "20") (pinfunction "20_20") (pintype "passive"))
      (node (ref "ID") (pin "2") (pinfunction "2_2") (pintype "bidirectional"))
      (node (ref "R4") (pin "2") (pinfunction "2_2") (pintype "passive"))
    )
    (net (code "149") (name "SDA0") (class "Default")
      (node (ref "PI1") (pin "81") (pinfunction "81_81") (pintype "passive"))
    )
    (net (code "150") (name "SDA1") (class "Default")
      (node (ref "D9") (pin "2") (pinfunction "D1-_2") (pintype "bidirectional"))
      (node (ref "D9") (pin "9") (pinfunction "D1-_9") (pintype "bidirectional"))
      (node (ref "DISP0") (pin "21") (pinfunction "21_21") (pintype "passive"))
      (node (ref "ID") (pin "4") (pinfunction "4_4") (pintype "bidirectional"))
      (node (ref "R3") (pin "2") (pinfunction "2_2") (pintype "passive"))
    )
    (net (code "151") (name "SD_CLK") (class "Default")
      (node (ref "D21") (pin "1") (pinfunction "I/O_1") (pintype "passive"))
      (node (ref "MICROSD") (pin "5") (pinfunction "CLK_5") (pintype "bidirectional"))
      (node (ref "PI1") (pin "58") (pinfunction "58_58") (pintype "passive"))
    )
    (net (code "152") (name "SD_CMD") (class "Default")
      (node (ref "D19") (pin "1") (pinfunction "I/O_1") (pintype "passive"))
      (node (ref "MICROSD") (pin "3") (pinfunction "CMD_3") (pintype "bidirectional"))
      (node (ref "PI1") (pin "61") (pinfunction "61_61") (pintype "passive"))
    )
    (net (code "153") (name "SD_DAT0") (class "Default")
      (node (ref "D22") (pin "1") (pinfunction "I/O_1") (pintype "passive"))
      (node (ref "MICROSD") (pin "7") (pinfunction "DAT0_7") (pintype "bidirectional"))
      (node (ref "PI1") (pin "64") (pinfunction "64_64") (pintype "passive"))
    )
    (net (code "154") (name "SD_DAT1") (class "Default")
      (node (ref "D23") (pin "1") (pinfunction "I/O_1") (pintype "passive"))
      (node (ref "MICROSD") (pin "8") (pinfunction "DAT1_8") (pintype "bidirectional"))
      (node (ref "PI1") (pin "68") (pinfunction "68_68") (pintype "passive"))
    )
    (net (code "155") (name "SD_DAT2") (class "Default")
      (node (ref "D17") (pin "1") (pinfunction "I/O_1") (pintype "passive"))
      (node (ref "MICROSD") (pin "1") (pinfunction "DAT2_1") (pintype "bidirectional"))
      (node (ref "PI1") (pin "70") (pinfunction "70_70") (pintype "passive"))
    )
    (net (code "156") (name "SD_DAT3") (class "Default")
      (node (ref "D18") (pin "1") (pinfunction "I/O_1") (pintype "passive"))
      (node (ref "MICROSD") (pin "2") (pinfunction "CD/DAT3_2") (pintype "bidirectional"))
      (node (ref "PI1") (pin "62") (pinfunction "62_62") (pintype "passive"))
    )
    (net (code "157") (name "SD_PWR") (class "Default")
      (node (ref "C10") (pin "1") (pinfunction "1_1") (pintype "passive"))
      (node (ref "C49") (pin "1") (pinfunction "1_1") (pintype "passive"))
      (node (ref "C50") (pin "1") (pinfunction "1_1") (pintype "passive"))
      (node (ref "D20") (pin "1") (pinfunction "I/O_1") (pintype "passive"))
      (node (ref "IC1") (pin "1") (pinfunction "OUT_1") (pintype "power_in"))
      (node (ref "MICROSD") (pin "4") (pinfunction "VDD_4") (pintype "bidirectional"))
      (node (ref "TP-VSD") (pin "TP") (pinfunction "P$1_TP") (pintype "bidirectional"))
    )
    (net (code "158") (name "SD_PWR_ON") (class "Default")
      (node (ref "IC1") (pin "4") (pinfunction "EN_4") (pintype "bidirectional"))
      (node (ref "PI1") (pin "76") (pinfunction "76_76") (pintype "passive"))
    )
    (net (code "159") (name "SYNC_OUT") (class "Default")
      (node (ref "PI1") (pin "17") (pinfunction "17_17") (pintype "passive"))
      (node (ref "SJ2") (pin "2") (pinfunction "2_2") (pintype "passive"))
    )
    (net (code "160") (name "TACHO") (class "Default")
      (node (ref "PI1") (pin "15") (pinfunction "15_15") (pintype "passive"))
    )
    (net (code "161") (name "TR0_TAP") (class "Default")
      (node (ref "ETH1") (pin "VC1") (pinfunction "VC1_VC1") (pintype "bidirectional"))
      (node (ref "POE") (pin "3") (pinfunction "3_3") (pintype "bidirectional"))
    )
    (net (code "162") (name "TR1_TAP") (class "Default")
      (node (ref "ETH1") (pin "VC2") (pinfunction "VC2_VC2") (pintype "bidirectional"))
      (node (ref "POE") (pin "1") (pinfunction "1_1") (pintype "bidirectional"))
    )
    (net (code "163") (name "TR2_TAP") (class "Default")
      (node (ref "ETH1") (pin "VC3") (pinfunction "VC3_VC3") (pintype "bidirectional"))
      (node (ref "POE") (pin "2") (pinfunction "2_2") (pintype "bidirectional"))
    )
    (net (code "164") (name "TR3_TAP") (class "Default")
      (node (ref "ETH1") (pin "VC4") (pinfunction "VC4_VC4") (pintype "bidirectional"))
      (node (ref "POE") (pin "4") (pinfunction "4_4") (pintype "bidirectional"))
    )
    (net (code "165") (name "USB3A_DP_N") (class "Default")
      (node (ref "D16") (pin "5") (pinfunction "D2-_5") (pintype "bidirectional"))
      (node (ref "D16") (pin "6") (pinfunction "D2-_6") (pintype "bidirectional"))
      (node (ref "PI1") (pin "135") (pinfunction "35_135") (pintype "passive"))
      (node (ref "USB3") (pin "2") (pinfunction "D-_2") (pintype "passive"))
    )
    (net (code "166") (name "USB3A_DP_P") (class "Default")
      (node (ref "D16") (pin "4") (pinfunction "D2+_4") (pintype "bidirectional"))
      (node (ref "D16") (pin "7") (pinfunction "D2+_7") (pintype "bidirectional"))
      (node (ref "PI1") (pin "133") (pinfunction "33_133") (pintype "passive"))
      (node (ref "USB3") (pin "3") (pinfunction "D+_3") (pintype "passive"))
    )
    (net (code "167") (name "USB3A_SSRX_N") (class "Default")
      (node (ref "D16") (pin "2") (pinfunction "D1-_2") (pintype "bidirectional"))
      (node (ref "D16") (pin "9") (pinfunction "D1-_9") (pintype "bidirectional"))
      (node (ref "PI1") (pin "127") (pinfunction "27_127") (pintype "passive"))
      (node (ref "USB3") (pin "5") (pinfunction "STDA_SSRX-_5") (pintype "passive"))
    )
    (net (code "168") (name "USB3A_SSRX_P") (class "Default")
      (node (ref "D16") (pin "1") (pinfunction "D1+_1") (pintype "bidirectional"))
      (node (ref "D16") (pin "10") (pinfunction "D1+_10") (pintype "bidirectional"))
      (node (ref "PI1") (pin "129") (pinfunction "29_129") (pintype "passive"))
      (node (ref "USB3") (pin "6") (pinfunction "STDA_SSRX+_6") (pintype "passive"))
    )
    (net (code "169") (name "USB3A_SSTX_N") (class "Default")
      (node (ref "D15") (pin "4") (pinfunction "D2+_4") (pintype "bidirectional"))
      (node (ref "D15") (pin "7") (pinfunction "D2+_7") (pintype "bidirectional"))
      (node (ref "PI1") (pin "139") (pinfunction "39_139") (pintype "passive"))
      (node (ref "USB3") (pin "8") (pinfunction "STDA_SSTX-_8") (pintype "passive"))
    )
    (net (code "170") (name "USB3A_SSTX_P") (class "Default")
      (node (ref "D15") (pin "5") (pinfunction "D2-_5") (pintype "bidirectional"))
      (node (ref "D15") (pin "6") (pinfunction "D2-_6") (pintype "bidirectional"))
      (node (ref "PI1") (pin "141") (pinfunction "41_141") (pintype "passive"))
      (node (ref "USB3") (pin "9") (pinfunction "STDA_SSTX+_9") (pintype "passive"))
    )
    (net (code "171") (name "USB3B_DP_N") (class "Default")
      (node (ref "PI1") (pin "166") (pinfunction "66_166") (pintype "passive"))
      (node (ref "R31") (pin "1") (pinfunction "1_1") (pintype "passive"))
    )
    (net (code "172") (name "USB3B_DP_P") (class "Default")
      (node (ref "PI1") (pin "164") (pinfunction "64_164") (pintype "passive"))
      (node (ref "R30") (pin "1") (pinfunction "1_1") (pintype "passive"))
    )
    (net (code "173") (name "USB3B_SSRX_N") (class "Default")
      (node (ref "D14") (pin "1") (pinfunction "D1+_1") (pintype "bidirectional"))
      (node (ref "D14") (pin "10") (pinfunction "D1+_10") (pintype "bidirectional"))
      (node (ref "PI1") (pin "158") (pinfunction "58_158") (pintype "passive"))
      (node (ref "USB3") (pin "14") (pinfunction "STDA_SSRX-_14") (pintype "passive"))
    )
    (net (code "174") (name "USB3B_SSRX_P") (class "Default")
      (node (ref "D14") (pin "2") (pinfunction "D1-_2") (pintype "bidirectional"))
      (node (ref "D14") (pin "9") (pinfunction "D1-_9") (pintype "bidirectional"))
      (node (ref "PI1") (pin "160") (pinfunction "60_160") (pintype "passive"))
      (node (ref "USB3") (pin "15") (pinfunction "STDA_SSRX+_15") (pintype "passive"))
    )
    (net (code "175") (name "USB3B_SSTX_N") (class "Default")
      (node (ref "D15") (pin "2") (pinfunction "D1-_2") (pintype "bidirectional"))
      (node (ref "D15") (pin "9") (pinfunction "D1-_9") (pintype "bidirectional"))
      (node (ref "PI1") (pin "170") (pinfunction "70_170") (pintype "passive"))
      (node (ref "USB3") (pin "17") (pinfunction "STDA_SSTX-_17") (pintype "passive"))
    )
    (net (code "176") (name "USB3B_SSTX_P") (class "Default")
      (node (ref "D15") (pin "1") (pinfunction "D1+_1") (pintype "bidirectional"))
      (node (ref "D15") (pin "10") (pinfunction "D1+_10") (pintype "bidirectional"))
      (node (ref "PI1") (pin "172") (pinfunction "72_172") (pintype "passive"))
      (node (ref "USB3") (pin "18") (pinfunction "STDA_SSTX+_18") (pintype "passive"))
    )
    (net (code "177") (name "USBOTG_ID") (class "Default")
      (node (ref "PI1") (pin "102") (pinfunction "2_102") (pintype "passive"))
      (node (ref "SJ3") (pin "2") (pinfunction "2_2") (pintype "passive"))
    )
    (net (code "178") (name "USB_5V") (class "Default")
      (node (ref "C6") (pin "1") (pinfunction "1_1") (pintype "passive"))
      (node (ref "C7") (pin "1") (pinfunction "1_1") (pintype "passive"))
      (node (ref "C8") (pin "1") (pinfunction "1_1") (pintype "passive"))
      (node (ref "IC2") (pin "6") (pinfunction "OUT_6") (pintype "bidirectional"))
      (node (ref "TP-VBUS") (pin "TP") (pinfunction "P$1_TP") (pintype "bidirectional"))
      (node (ref "USB3") (pin "1") (pinfunction "VBUS_1") (pintype "passive"))
      (node (ref "USB3") (pin "10") (pinfunction "VBUS_10") (pintype "passive"))
    )
    (net (code "179") (name "USB_DP_N") (class "Default")
      (node (ref "PI1") (pin "104") (pinfunction "4_104") (pintype "passive"))
      (node (ref "USBC") (pin "A7") (pinfunction "D-1_A7") (pintype "passive"))
      (node (ref "USBC") (pin "B7") (pinfunction "D-2_B7") (pintype "passive"))
    )
    (net (code "180") (name "USB_DP_P") (class "Default")
      (node (ref "PI1") (pin "106") (pinfunction "6_106") (pintype "passive"))
      (node (ref "USBC") (pin "A6") (pinfunction "D+1_A6") (pintype "passive"))
      (node (ref "USBC") (pin "B6") (pinfunction "D+2_B6") (pintype "passive"))
    )
    (net (code "181") (name "VBAT") (class "Default")
      (node (ref "PI1") (pin "75") (pinfunction "75_75") (pintype "passive"))
    )
    (net (code "182") (name "VBUS") (class "Default")
      (node (ref "C2") (pin "1") (pinfunction "1_1") (pintype "passive"))
      (node (ref "Q1") (pin "2") (pinfunction "E_2") (pintype "passive"))
      (node (ref "R1") (pin "1") (pinfunction "1_1") (pintype "passive"))
      (node (ref "T5") (pin "5") (pinfunction "D_5") (pintype "passive"))
      (node (ref "T5") (pin "6") (pinfunction "D_6") (pintype "passive"))
      (node (ref "T5") (pin "7") (pinfunction "D_7") (pintype "passive"))
      (node (ref "T5") (pin "8") (pinfunction "D_8") (pintype "passive"))
      (node (ref "USBC") (pin "A4") (pinfunction "VBUS_A4") (pintype "passive"))
      (node (ref "USBC") (pin "A9") (pinfunction "VBUS1_A9") (pintype "passive"))
      (node (ref "USBC") (pin "B4") (pinfunction "VBUS3_B4") (pintype "passive"))
      (node (ref "USBC") (pin "B9") (pinfunction "VBUS2_B9") (pintype "passive"))
    )
    (net (code "183") (name "VBUS_EN") (class "Default")
      (node (ref "IC2") (pin "3") (pinfunction "EN_3") (pintype "bidirectional"))
      (node (ref "IC7") (pin "3") (pinfunction "EN_3") (pintype "bidirectional"))
      (node (ref "PI1") (pin "112") (pinfunction "12_112") (pintype "passive"))
    )
    (net (code "184") (name "WL_NDIS") (class "Default")
      (node (ref "PI1") (pin "90") (pinfunction "90_90") (pintype "passive"))
    )
    (net (code "185") (name "unconnected-(HDMI2-CEC-Pad14)") (class "Default")
      (node (ref "HDMI2") (pin "14") (pinfunction "CEC_14") (pintype "passive"))
    )
    (net (code "186") (name "unconnected-(IC1-NFLG-Pad3)") (class "Default")
      (node (ref "IC1") (pin "3") (pinfunction "NFLG_3") (pintype "bidirectional"))
    )
    (net (code "187") (name "unconnected-(IC2-~{FAULT}-Pad4)") (class "Default")
      (node (ref "IC2") (pin "4") (pinfunction "~{FAULT}_4") (pintype "bidirectional"))
    )
    (net (code "188") (name "unconnected-(IC5-NC-Pad5)") (class "Default")
      (node (ref "IC5") (pin "5") (pinfunction "NC_5") (pintype "no_connect"))
    )
    (net (code "189") (name "unconnected-(IC5-PG-Pad2)") (class "Default")
      (node (ref "IC5") (pin "2") (pinfunction "PG_2") (pintype "bidirectional"))
    )
    (net (code "190") (name "unconnected-(IC6-LED1-Pad22)") (class "Default")
      (node (ref "IC6") (pin "22") (pinfunction "LED1_22") (pintype "bidirectional"))
    )
    (net (code "191") (name "unconnected-(IC6-LED2-Pad23)") (class "Default")
      (node (ref "IC6") (pin "23") (pinfunction "LED2_23") (pintype "bidirectional"))
    )
    (net (code "192") (name "unconnected-(IC6-LED4{slash}SDA-Pad21)") (class "Default")
      (node (ref "IC6") (pin "21") (pinfunction "LED4/SDA_21") (pintype "bidirectional"))
    )
    (net (code "193") (name "unconnected-(IC6-NC-Pad2)") (class "Default")
      (node (ref "IC6") (pin "2") (pinfunction "NC_2") (pintype "no_connect"))
    )
    (net (code "194") (name "unconnected-(IC6-NC-Pad17)") (class "Default")
      (node (ref "IC6") (pin "17") (pinfunction "NC_17") (pintype "no_connect"))
    )
    (net (code "195") (name "unconnected-(IC6-~{OVCUR}-Pad1)") (class "Default")
      (node (ref "IC6") (pin "1") (pinfunction "~{OVCUR}_1") (pintype "output"))
    )
    (net (code "196") (name "unconnected-(IC6-~{PWREN}-Pad24)") (class "Default")
      (node (ref "IC6") (pin "24") (pinfunction "~{PWREN}_24") (pintype "input"))
    )
    (net (code "197") (name "unconnected-(IC7-~{FAULT}-Pad4)") (class "Default")
      (node (ref "IC7") (pin "4") (pinfunction "~{FAULT}_4") (pintype "bidirectional"))
    )
    (net (code "198") (name "unconnected-(J1-Pad2)") (class "Default")
      (node (ref "J1") (pin "2") (pinfunction "2_2") (pintype "bidirectional"))
    )
    (net (code "199") (name "unconnected-(J1-Pad3)") (class "Default")
      (node (ref "J1") (pin "3") (pinfunction "3_3") (pintype "bidirectional"))
    )
    (net (code "200") (name "unconnected-(J1-Pad4)") (class "Default")
      (node (ref "J1") (pin "4") (pinfunction "4_4") (pintype "bidirectional"))
    )
    (net (code "201") (name "unconnected-(J1-Pad5)") (class "Default")
      (node (ref "J1") (pin "5") (pinfunction "5_5") (pintype "bidirectional"))
    )
    (net (code "202") (name "unconnected-(J1-Pad6)") (class "Default")
      (node (ref "J1") (pin "6") (pinfunction "6_6") (pintype "bidirectional"))
    )
    (net (code "203") (name "unconnected-(J1-Pad7)") (class "Default")
      (node (ref "J1") (pin "7") (pinfunction "7_7") (pintype "bidirectional"))
    )
    (net (code "204") (name "unconnected-(J1-Pad10)") (class "Default")
      (node (ref "J1") (pin "10") (pinfunction "10_10") (pintype "bidirectional"))
    )
    (net (code "205") (name "unconnected-(J1-Pad11)") (class "Default")
      (node (ref "J1") (pin "11") (pinfunction "11_11") (pintype "bidirectional"))
    )
    (net (code "206") (name "unconnected-(J1-Pad12)") (class "Default")
      (node (ref "J1") (pin "12") (pinfunction "12_12") (pintype "bidirectional"))
    )
    (net (code "207") (name "unconnected-(J1-Pad13)") (class "Default")
      (node (ref "J1") (pin "13") (pinfunction "13_13") (pintype "bidirectional"))
    )
    (net (code "208") (name "unconnected-(J1-Pad14)") (class "Default")
      (node (ref "J1") (pin "14") (pinfunction "14_14") (pintype "bidirectional"))
    )
    (net (code "209") (name "unconnected-(J1-Pad15)") (class "Default")
      (node (ref "J1") (pin "15") (pinfunction "15_15") (pintype "bidirectional"))
    )
    (net (code "210") (name "unconnected-(J1-Pad16)") (class "Default")
      (node (ref "J1") (pin "16") (pinfunction "16_16") (pintype "bidirectional"))
    )
    (net (code "211") (name "unconnected-(J1-Pad17)") (class "Default")
      (node (ref "J1") (pin "17") (pinfunction "17_17") (pintype "bidirectional"))
    )
    (net (code "212") (name "unconnected-(J1-Pad18)") (class "Default")
      (node (ref "J1") (pin "18") (pinfunction "18_18") (pintype "bidirectional"))
    )
    (net (code "213") (name "unconnected-(J1-Pad19)") (class "Default")
      (node (ref "J1") (pin "19") (pinfunction "19_19") (pintype "bidirectional"))
    )
    (net (code "214") (name "unconnected-(J1-Pad20)") (class "Default")
      (node (ref "J1") (pin "20") (pinfunction "20_20") (pintype "bidirectional"))
    )
    (net (code "215") (name "unconnected-(J2-Pad1)") (class "Default")
      (node (ref "J2") (pin "1") (pinfunction "1_1") (pintype "bidirectional"))
    )
    (net (code "216") (name "unconnected-(J2-Pad2)") (class "Default")
      (node (ref "J2") (pin "2") (pinfunction "2_2") (pintype "bidirectional"))
    )
    (net (code "217") (name "unconnected-(J2-Pad3)") (class "Default")
      (node (ref "J2") (pin "3") (pinfunction "3_3") (pintype "bidirectional"))
    )
    (net (code "218") (name "unconnected-(J2-Pad4)") (class "Default")
      (node (ref "J2") (pin "4") (pinfunction "4_4") (pintype "bidirectional"))
    )
    (net (code "219") (name "unconnected-(J2-Pad5)") (class "Default")
      (node (ref "J2") (pin "5") (pinfunction "5_5") (pintype "bidirectional"))
    )
    (net (code "220") (name "unconnected-(J2-Pad6)") (class "Default")
      (node (ref "J2") (pin "6") (pinfunction "6_6") (pintype "bidirectional"))
    )
    (net (code "221") (name "unconnected-(J3-Pad2)") (class "Default")
      (node (ref "J3") (pin "2") (pinfunction "2_2") (pintype "bidirectional"))
    )
    (net (code "222") (name "unconnected-(J3-Pad3)") (class "Default")
      (node (ref "J3") (pin "3") (pinfunction "3_3") (pintype "bidirectional"))
    )
    (net (code "223") (name "unconnected-(J3-Pad4)") (class "Default")
      (node (ref "J3") (pin "4") (pinfunction "4_4") (pintype "bidirectional"))
    )
    (net (code "224") (name "unconnected-(J3-Pad5)") (class "Default")
      (node (ref "J3") (pin "5") (pinfunction "5_5") (pintype "bidirectional"))
    )
    (net (code "225") (name "unconnected-(J3-Pad6)") (class "Default")
      (node (ref "J3") (pin "6") (pinfunction "6_6") (pintype "bidirectional"))
    )
    (net (code "226") (name "unconnected-(J3-Pad10)") (class "Default")
      (node (ref "J3") (pin "10") (pinfunction "10_10") (pintype "bidirectional"))
    )
    (net (code "227") (name "unconnected-(J3-Pad11)") (class "Default")
      (node (ref "J3") (pin "11") (pinfunction "11_11") (pintype "bidirectional"))
    )
    (net (code "228") (name "unconnected-(J3-Pad12)") (class "Default")
      (node (ref "J3") (pin "12") (pinfunction "12_12") (pintype "bidirectional"))
    )
    (net (code "229") (name "unconnected-(J4-Pad1)") (class "Default")
      (node (ref "J4") (pin "1") (pinfunction "1_1") (pintype "bidirectional"))
    )
    (net (code "230") (name "unconnected-(J4-Pad2)") (class "Default")
      (node (ref "J4") (pin "2") (pinfunction "2_2") (pintype "bidirectional"))
    )
    (net (code "231") (name "unconnected-(J4-Pad3)") (class "Default")
      (node (ref "J4") (pin "3") (pinfunction "3_3") (pintype "bidirectional"))
    )
    (net (code "232") (name "unconnected-(PCIE-DEVSLP-Pad38)") (class "Default")
      (node (ref "PCIE") (pin "38") (pinfunction "DEVSLP_38") (pintype "bidirectional"))
    )
    (net (code "233") (name "unconnected-(PCIE-NC1-Pad58)") (class "Default")
      (node (ref "PCIE") (pin "58") (pinfunction "NC1_58") (pintype "bidirectional"))
    )
    (net (code "234") (name "unconnected-(PCIE-NC2-Pad56)") (class "Default")
      (node (ref "PCIE") (pin "56") (pinfunction "NC2_56") (pintype "bidirectional"))
    )
    (net (code "235") (name "unconnected-(PCIE-NC3-Pad48)") (class "Default")
      (node (ref "PCIE") (pin "48") (pinfunction "NC3_48") (pintype "bidirectional"))
    )
    (net (code "236") (name "unconnected-(PCIE-NC4-Pad46)") (class "Default")
      (node (ref "PCIE") (pin "46") (pinfunction "NC4_46") (pintype "bidirectional"))
    )
    (net (code "237") (name "unconnected-(PCIE-NC5-Pad44)") (class "Default")
      (node (ref "PCIE") (pin "44") (pinfunction "NC5_44") (pintype "bidirectional"))
    )
    (net (code "238") (name "unconnected-(PCIE-NC6-Pad42)") (class "Default")
      (node (ref "PCIE") (pin "42") (pinfunction "NC6_42") (pintype "bidirectional"))
    )
    (net (code "239") (name "unconnected-(PCIE-NC7-Pad40)") (class "Default")
      (node (ref "PCIE") (pin "40") (pinfunction "NC7_40") (pintype "bidirectional"))
    )
    (net (code "240") (name "unconnected-(PCIE-NC8-Pad36)") (class "Default")
      (node (ref "PCIE") (pin "36") (pinfunction "NC8_36") (pintype "bidirectional"))
    )
    (net (code "241") (name "unconnected-(PCIE-NC9-Pad34)") (class "Default")
      (node (ref "PCIE") (pin "34") (pinfunction "NC9_34") (pintype "bidirectional"))
    )
    (net (code "242") (name "unconnected-(PCIE-NC10-Pad32)") (class "Default")
      (node (ref "PCIE") (pin "32") (pinfunction "NC10_32") (pintype "bidirectional"))
    )
    (net (code "243") (name "unconnected-(PCIE-NC11-Pad30)") (class "Default")
      (node (ref "PCIE") (pin "30") (pinfunction "NC11_30") (pintype "bidirectional"))
    )
    (net (code "244") (name "unconnected-(PCIE-NC12-Pad28)") (class "Default")
      (node (ref "PCIE") (pin "28") (pinfunction "NC12_28") (pintype "bidirectional"))
    )
    (net (code "245") (name "unconnected-(PCIE-NC13-Pad26)") (class "Default")
      (node (ref "PCIE") (pin "26") (pinfunction "NC13_26") (pintype "bidirectional"))
    )
    (net (code "246") (name "unconnected-(PCIE-NC14-Pad24)") (class "Default")
      (node (ref "PCIE") (pin "24") (pinfunction "NC14_24") (pintype "bidirectional"))
    )
    (net (code "247") (name "unconnected-(PCIE-NC15-Pad22)") (class "Default")
      (node (ref "PCIE") (pin "22") (pinfunction "NC15_22") (pintype "bidirectional"))
    )
    (net (code "248") (name "unconnected-(PCIE-NC16-Pad20)") (class "Default")
      (node (ref "PCIE") (pin "20") (pinfunction "NC16_20") (pintype "bidirectional"))
    )
    (net (code "249") (name "unconnected-(PCIE-NC17-Pad8)") (class "Default")
      (node (ref "PCIE") (pin "8") (pinfunction "NC17_8") (pintype "bidirectional"))
    )
    (net (code "250") (name "unconnected-(PCIE-NC18-Pad6)") (class "Default")
      (node (ref "PCIE") (pin "6") (pinfunction "NC18_6") (pintype "bidirectional"))
    )
    (net (code "251") (name "unconnected-(PCIE-NC19-Pad67)") (class "Default")
      (node (ref "PCIE") (pin "67") (pinfunction "NC19_67") (pintype "bidirectional"))
    )
    (net (code "252") (name "unconnected-(PCIE-PEDET-Pad69)") (class "Default")
      (node (ref "PCIE") (pin "69") (pinfunction "PEDET_69") (pintype "bidirectional"))
    )
    (net (code "253") (name "unconnected-(PCIE-PER_N1-Pad35)") (class "Default")
      (node (ref "PCIE") (pin "35") (pinfunction "PER_N1_35") (pintype "bidirectional"))
    )
    (net (code "254") (name "unconnected-(PCIE-PER_N2-Pad23)") (class "Default")
      (node (ref "PCIE") (pin "23") (pinfunction "PER_N2_23") (pintype "bidirectional"))
    )
    (net (code "255") (name "unconnected-(PCIE-PER_N3-Pad11)") (class "Default")
      (node (ref "PCIE") (pin "11") (pinfunction "PER_N3_11") (pintype "bidirectional"))
    )
    (net (code "256") (name "unconnected-(PCIE-PER_P1-Pad37)") (class "Default")
      (node (ref "PCIE") (pin "37") (pinfunction "PER_P1_37") (pintype "bidirectional"))
    )
    (net (code "257") (name "unconnected-(PCIE-PER_P2-Pad25)") (class "Default")
      (node (ref "PCIE") (pin "25") (pinfunction "PER_P2_25") (pintype "bidirectional"))
    )
    (net (code "258") (name "unconnected-(PCIE-PER_P3-Pad13)") (class "Default")
      (node (ref "PCIE") (pin "13") (pinfunction "PER_P3_13") (pintype "bidirectional"))
    )
    (net (code "259") (name "unconnected-(PCIE-PET_N1-Pad29)") (class "Default")
      (node (ref "PCIE") (pin "29") (pinfunction "PET_N1_29") (pintype "bidirectional"))
    )
    (net (code "260") (name "unconnected-(PCIE-PET_N2-Pad17)") (class "Default")
      (node (ref "PCIE") (pin "17") (pinfunction "PET_N2_17") (pintype "bidirectional"))
    )
    (net (code "261") (name "unconnected-(PCIE-PET_N3-Pad5)") (class "Default")
      (node (ref "PCIE") (pin "5") (pinfunction "PET_N3_5") (pintype "bidirectional"))
    )
    (net (code "262") (name "unconnected-(PCIE-PET_P1-Pad31)") (class "Default")
      (node (ref "PCIE") (pin "31") (pinfunction "PET_P1_31") (pintype "bidirectional"))
    )
    (net (code "263") (name "unconnected-(PCIE-PET_P2-Pad19)") (class "Default")
      (node (ref "PCIE") (pin "19") (pinfunction "PET_P2_19") (pintype "bidirectional"))
    )
    (net (code "264") (name "unconnected-(PCIE-PET_P3-Pad7)") (class "Default")
      (node (ref "PCIE") (pin "7") (pinfunction "PET_P3_7") (pintype "bidirectional"))
    )
    (net (code "265") (name "unconnected-(PI1-Pad63)") (class "Default")
      (node (ref "PI1") (pin "63") (pinfunction "63_63") (pintype "passive"))
    )
    (net (code "266") (name "unconnected-(PI1-Pad67)") (class "Default")
      (node (ref "PI1") (pin "67") (pinfunction "67_67") (pintype "passive"))
    )
    (net (code "267") (name "unconnected-(PI1-Pad69)") (class "Default")
      (node (ref "PI1") (pin "69") (pinfunction "69_69") (pintype "passive"))
    )
    (net (code "268") (name "unconnected-(PI1-Pad71)") (class "Default")
      (node (ref "PI1") (pin "71") (pinfunction "71_71") (pintype "passive"))
    )
    (net (code "269") (name "unconnected-(PI1-Pad74)") (class "Default")
      (node (ref "PI1") (pin "74") (pinfunction "74_74") (pintype "passive"))
    )
    (net (code "270") (name "unconnected-(PI1B-16-Pad116)") (class "Default")
      (node (ref "PI1") (pin "116") (pinfunction "16_116") (pintype "passive"))
    )
    (net (code "271") (name "unconnected-(PI1B-18-Pad118)") (class "Default")
      (node (ref "PI1") (pin "118") (pinfunction "18_118") (pintype "passive"))
    )
    (net (code "272") (name "unconnected-(PI1B-22-Pad122)") (class "Default")
      (node (ref "PI1") (pin "122") (pinfunction "22_122") (pintype "passive"))
    )
    (net (code "273") (name "unconnected-(PI1B-24-Pad124)") (class "Default")
      (node (ref "PI1") (pin "124") (pinfunction "24_124") (pintype "passive"))
    )
    (net (code "274") (name "unconnected-(PI1B-28-Pad128)") (class "Default")
      (node (ref "PI1") (pin "128") (pinfunction "28_128") (pintype "passive"))
    )
    (net (code "275") (name "unconnected-(PI1B-30-Pad130)") (class "Default")
      (node (ref "PI1") (pin "130") (pinfunction "30_130") (pintype "passive"))
    )
    (net (code "276") (name "unconnected-(PI1B-34-Pad134)") (class "Default")
      (node (ref "PI1") (pin "134") (pinfunction "34_134") (pintype "passive"))
    )
    (net (code "277") (name "unconnected-(PI1B-36-Pad136)") (class "Default")
      (node (ref "PI1") (pin "136") (pinfunction "36_136") (pintype "passive"))
    )
    (net (code "278") (name "unconnected-(PI1B-40-Pad140)") (class "Default")
      (node (ref "PI1") (pin "140") (pinfunction "40_140") (pintype "passive"))
    )
    (net (code "279") (name "unconnected-(PI1B-42-Pad142)") (class "Default")
      (node (ref "PI1") (pin "142") (pinfunction "42_142") (pintype "passive"))
    )
    (net (code "280") (name "unconnected-(PI1B-44-Pad144)") (class "Default")
      (node (ref "PI1") (pin "144") (pinfunction "44_144") (pintype "passive"))
    )
    (net (code "281") (name "unconnected-(PI1B-45-Pad145)") (class "Default")
      (node (ref "PI1") (pin "145") (pinfunction "45_145") (pintype "passive"))
    )
    (net (code "282") (name "unconnected-(PI1B-46-Pad146)") (class "Default")
      (node (ref "PI1") (pin "146") (pinfunction "46_146") (pintype "passive"))
    )
    (net (code "283") (name "unconnected-(PI1B-47-Pad147)") (class "Default")
      (node (ref "PI1") (pin "147") (pinfunction "47_147") (pintype "passive"))
    )
    (net (code "284") (name "unconnected-(PI1B-48-Pad148)") (class "Default")
      (node (ref "PI1") (pin "148") (pinfunction "48_148") (pintype "passive"))
    )
    (net (code "285") (name "unconnected-(PI1B-50-Pad150)") (class "Default")
      (node (ref "PI1") (pin "150") (pinfunction "50_150") (pintype "passive"))
    )
    (net (code "286") (name "unconnected-(PI1B-51-Pad151)") (class "Default")
      (node (ref "PI1") (pin "151") (pinfunction "51_151") (pintype "passive"))
    )
    (net (code "287") (name "unconnected-(PI1B-53-Pad153)") (class "Default")
      (node (ref "PI1") (pin "153") (pinfunction "53_153") (pintype "passive"))
    )
    (net (code "288") (name "unconnected-(PI1B-57-Pad157)") (class "Default")
      (node (ref "PI1") (pin "157") (pinfunction "57_157") (pintype "passive"))
    )
    (net (code "289") (name "unconnected-(PI1B-59-Pad159)") (class "Default")
      (node (ref "PI1") (pin "159") (pinfunction "59_159") (pintype "passive"))
    )
    (net (code "290") (name "unconnected-(PI1B-63-Pad163)") (class "Default")
      (node (ref "PI1") (pin "163") (pinfunction "63_163") (pintype "passive"))
    )
    (net (code "291") (name "unconnected-(PI1B-65-Pad165)") (class "Default")
      (node (ref "PI1") (pin "165") (pinfunction "65_165") (pintype "passive"))
    )
    (net (code "292") (name "unconnected-(USBC-SBU1-PadA8)") (class "Default")
      (node (ref "USBC") (pin "A8") (pinfunction "SBU1_A8") (pintype "passive"))
    )
    (net (code "293") (name "unconnected-(USBC-SBU2-PadB8)") (class "Default")
      (node (ref "USBC") (pin "B8") (pinfunction "SBU2_B8") (pintype "passive"))
    )
  )
)
